# Titan_Teknic_v1p00.net
KiCad netlist of a schematic drawn in EAGLE
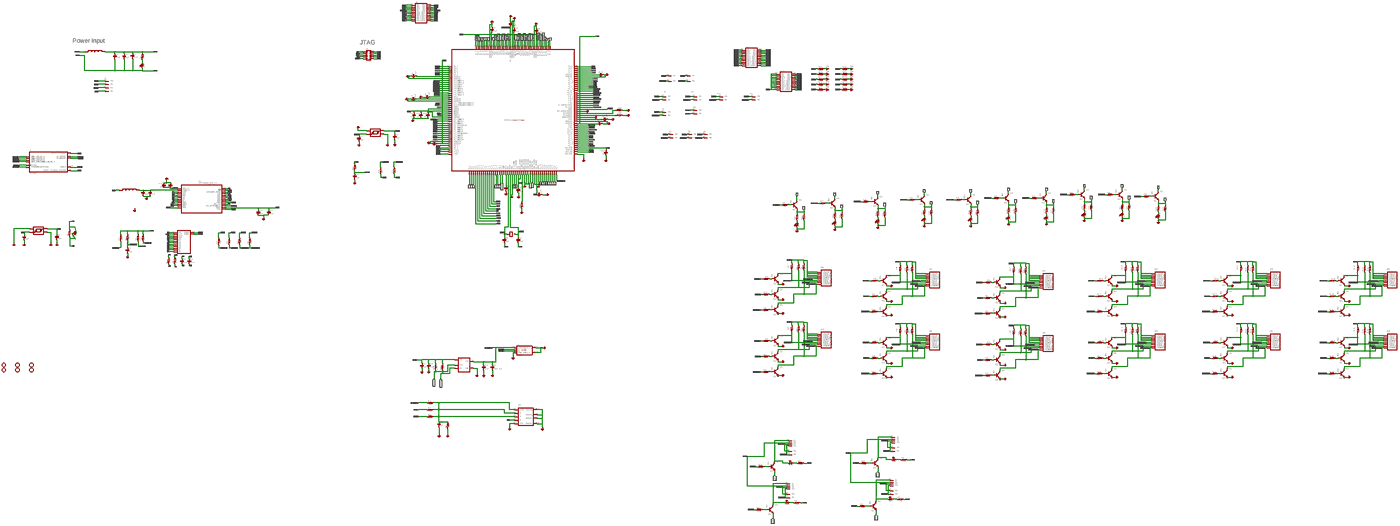
[diagram p0: schematic, sheet 1, overview]
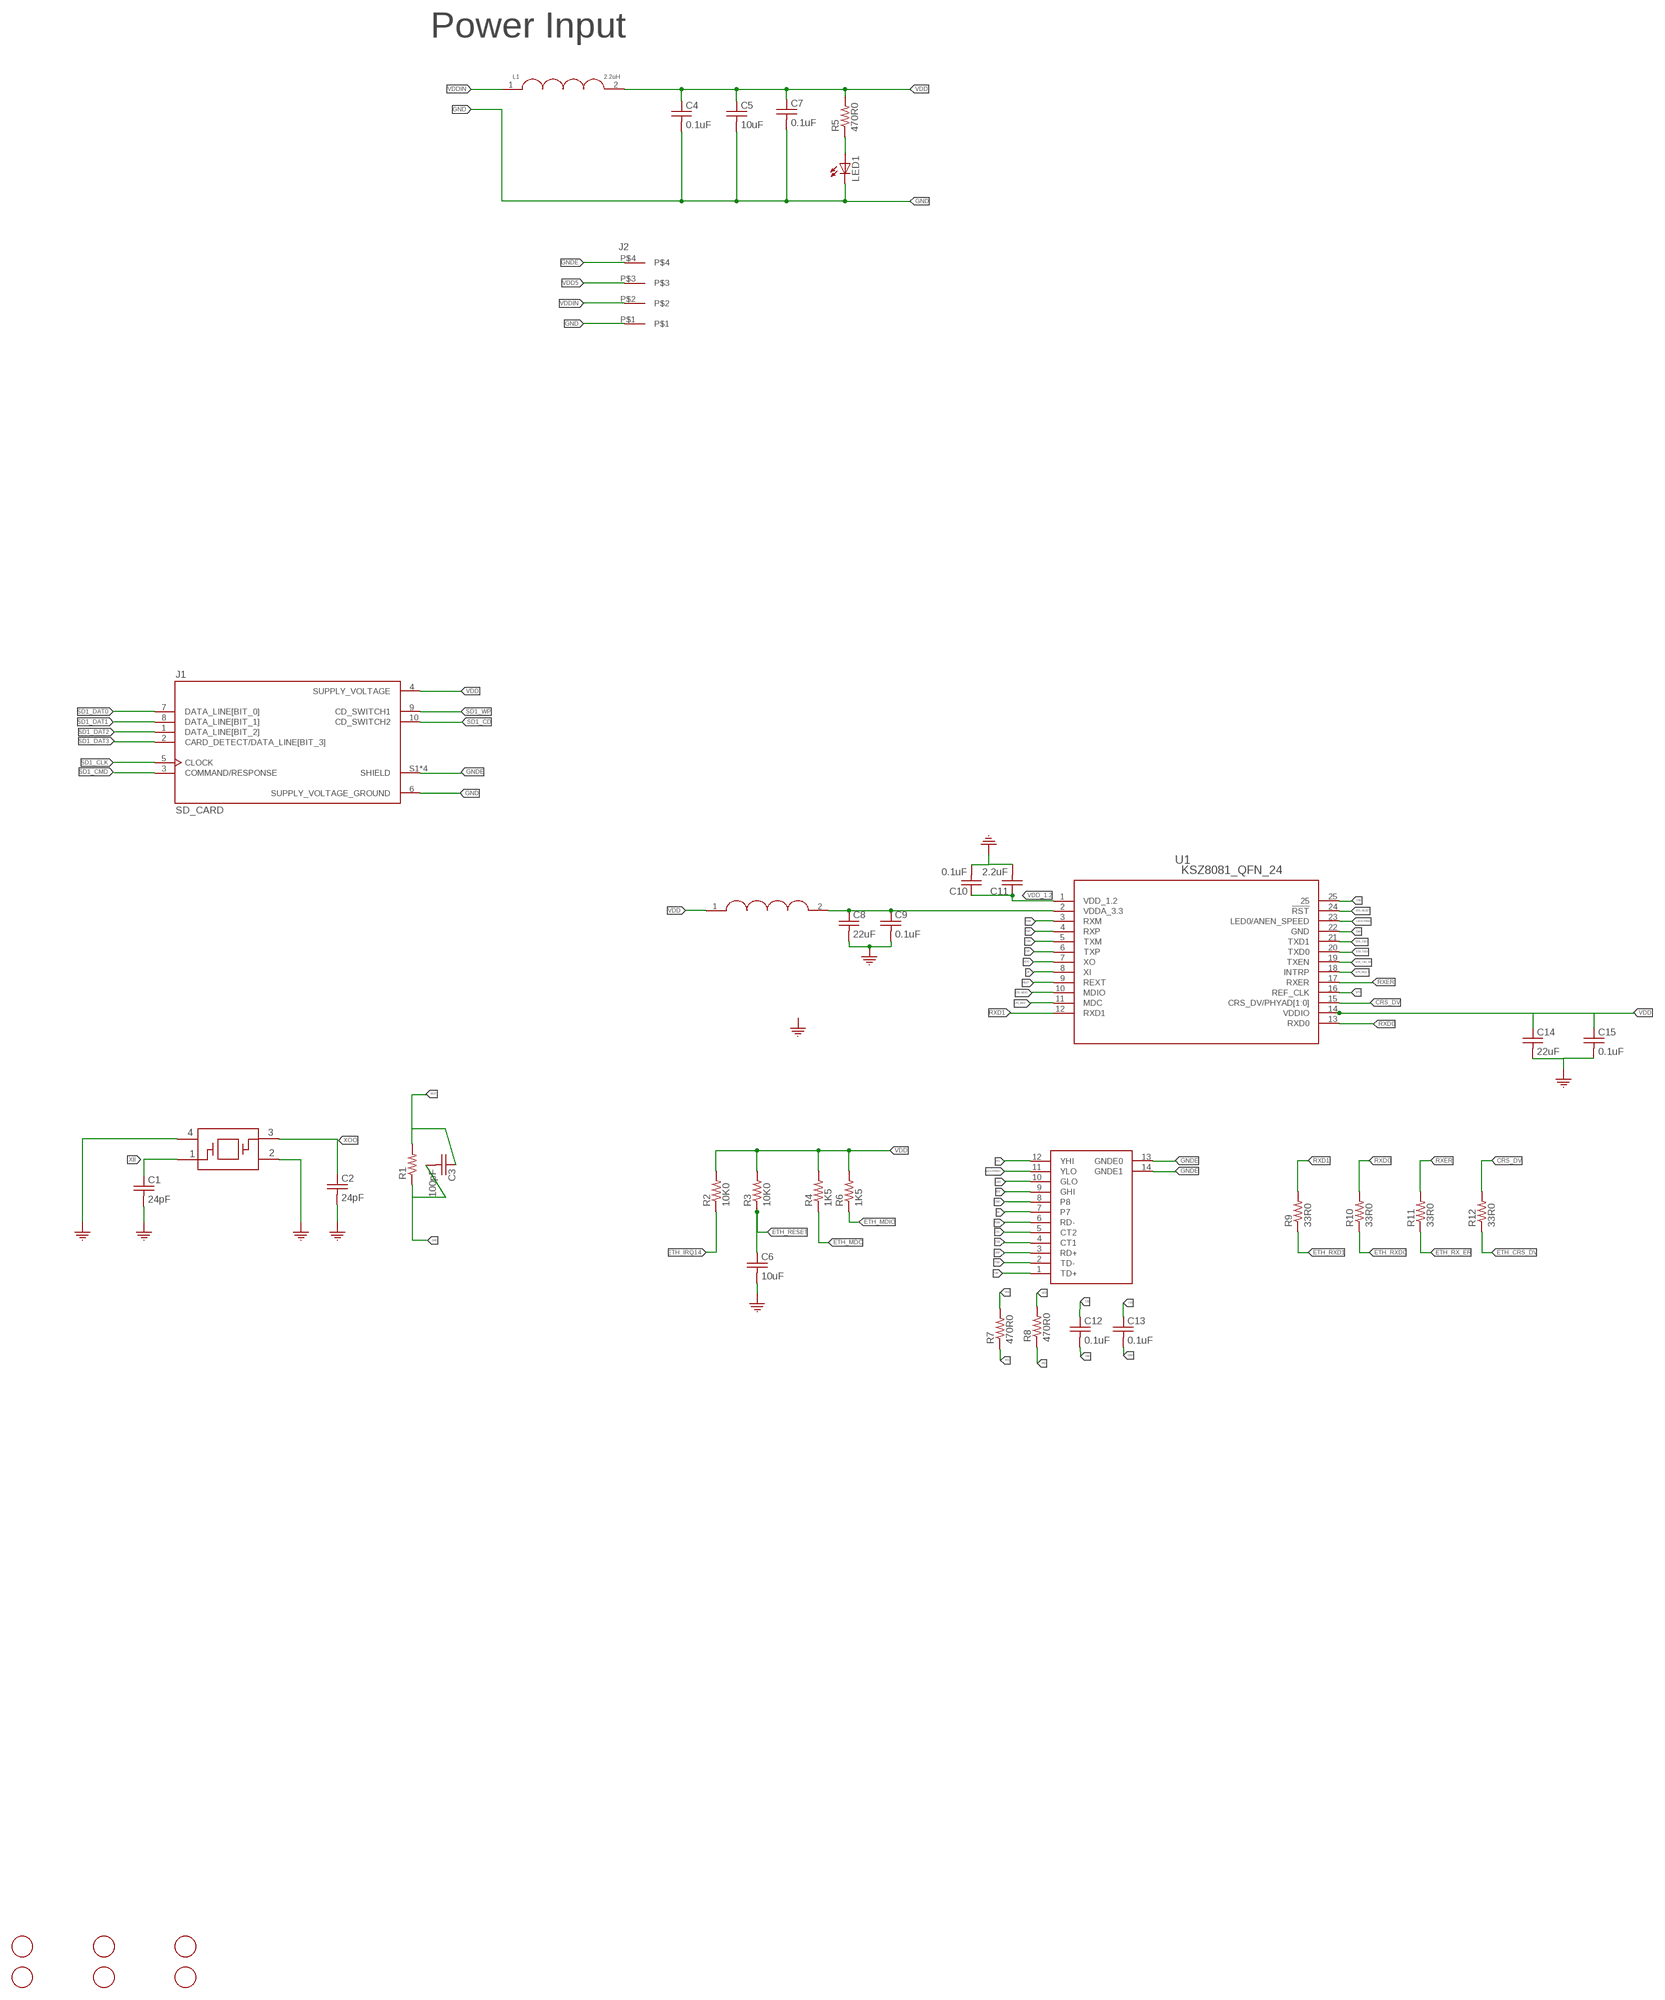
[diagram p1: schematic, sheet 1, part 1 of 6]
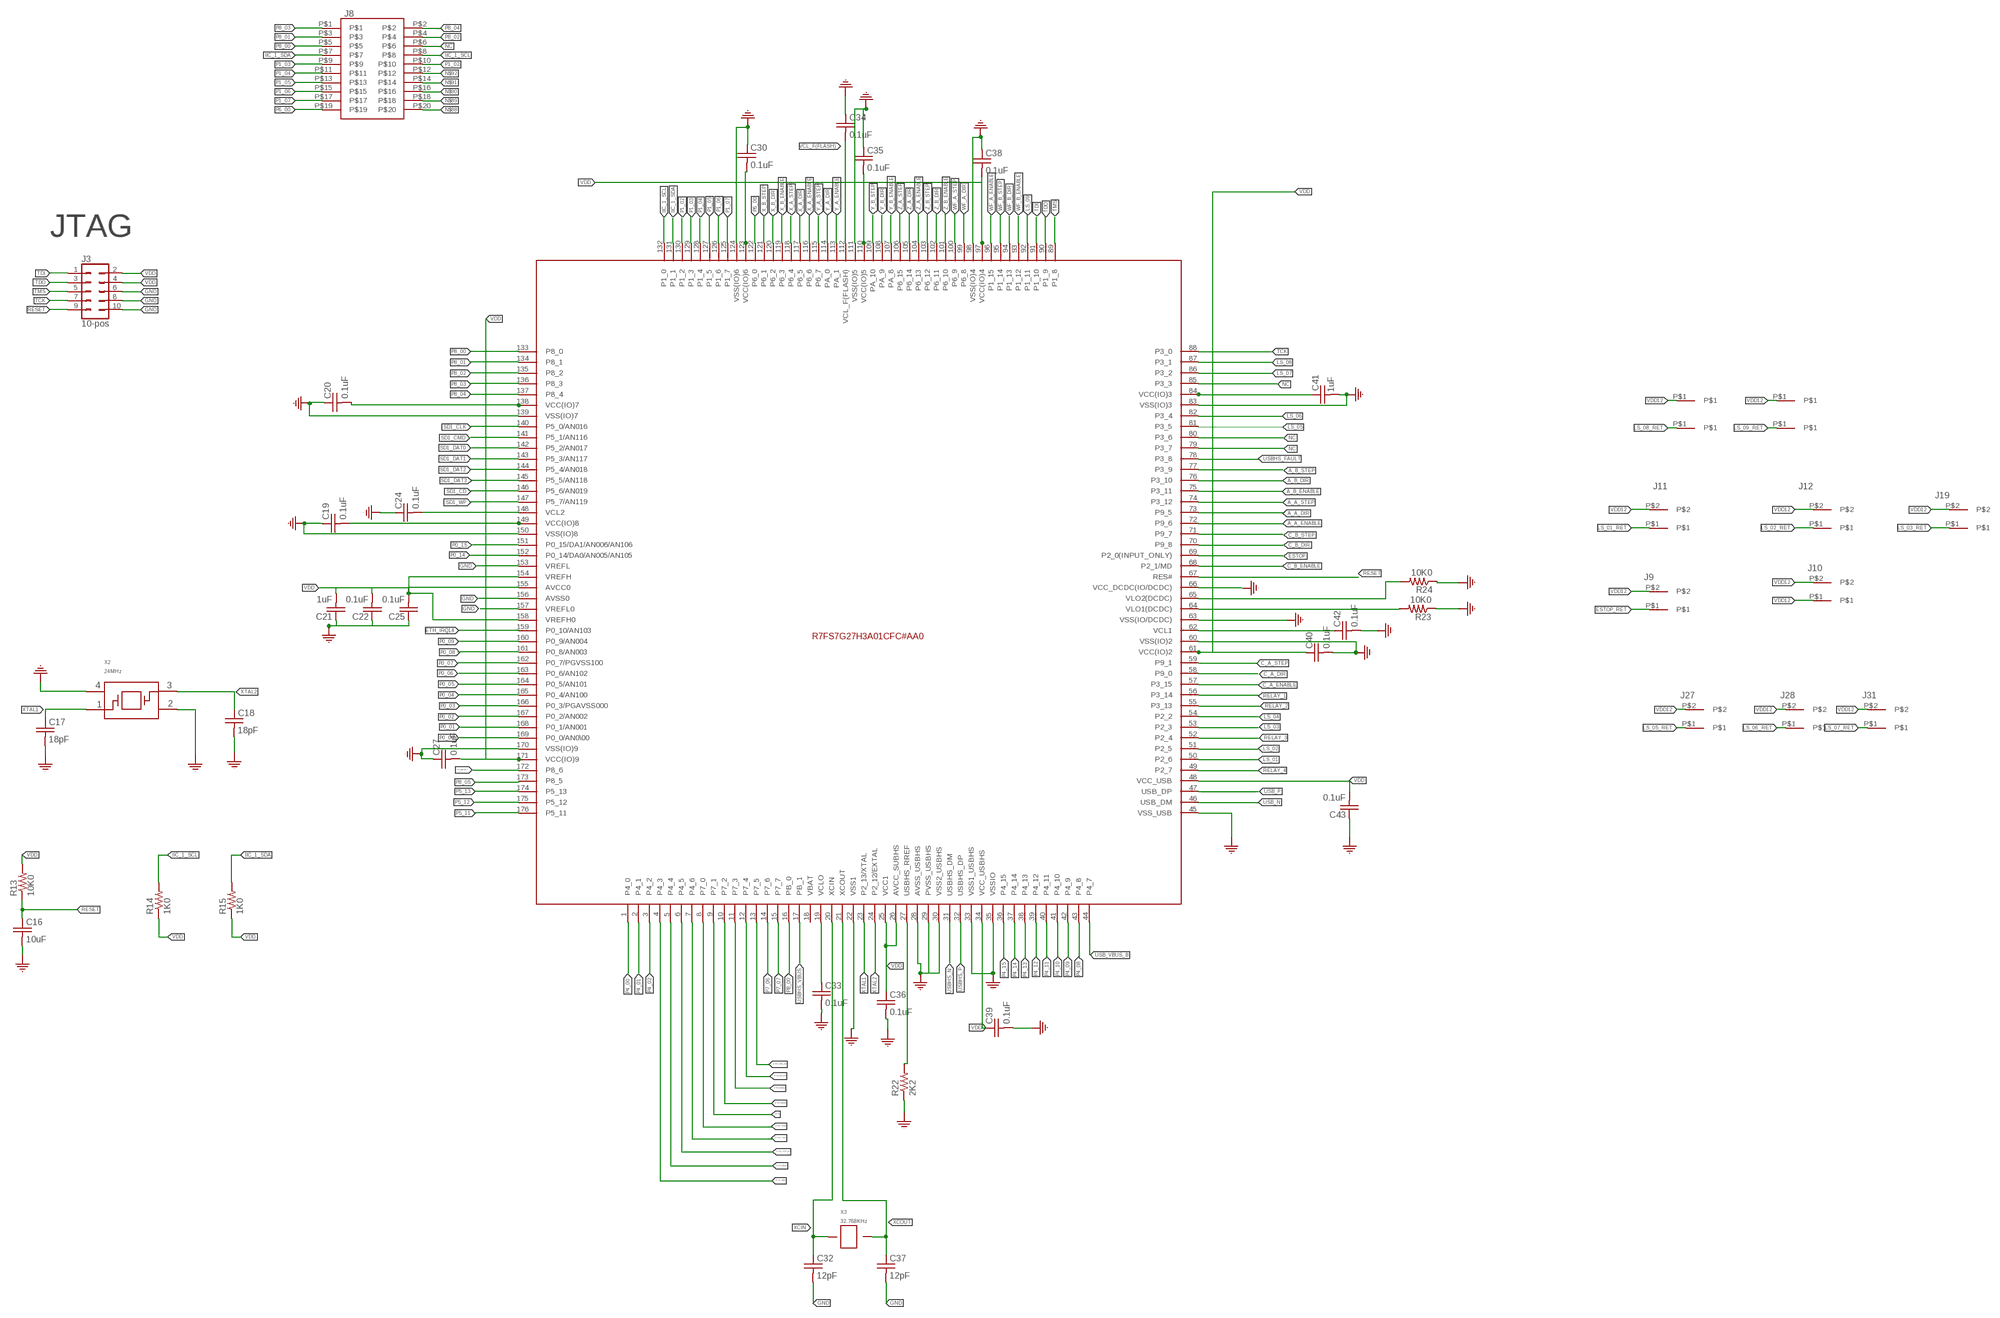
[diagram p2: schematic, sheet 1, part 2 of 6]
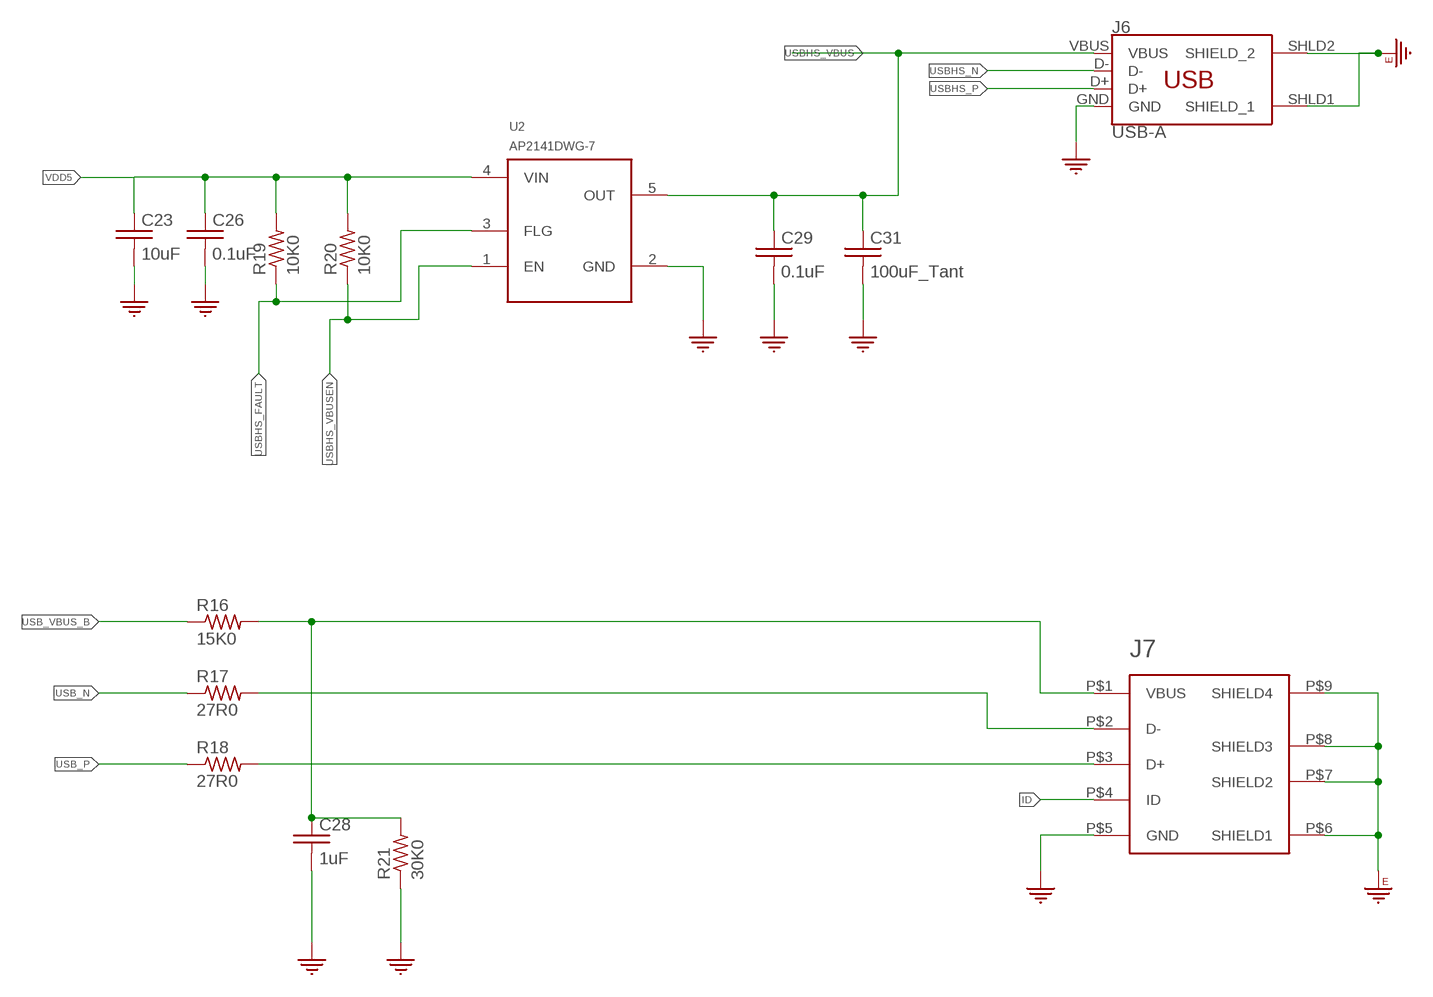
[diagram p3: schematic, sheet 1, part 3 of 6]
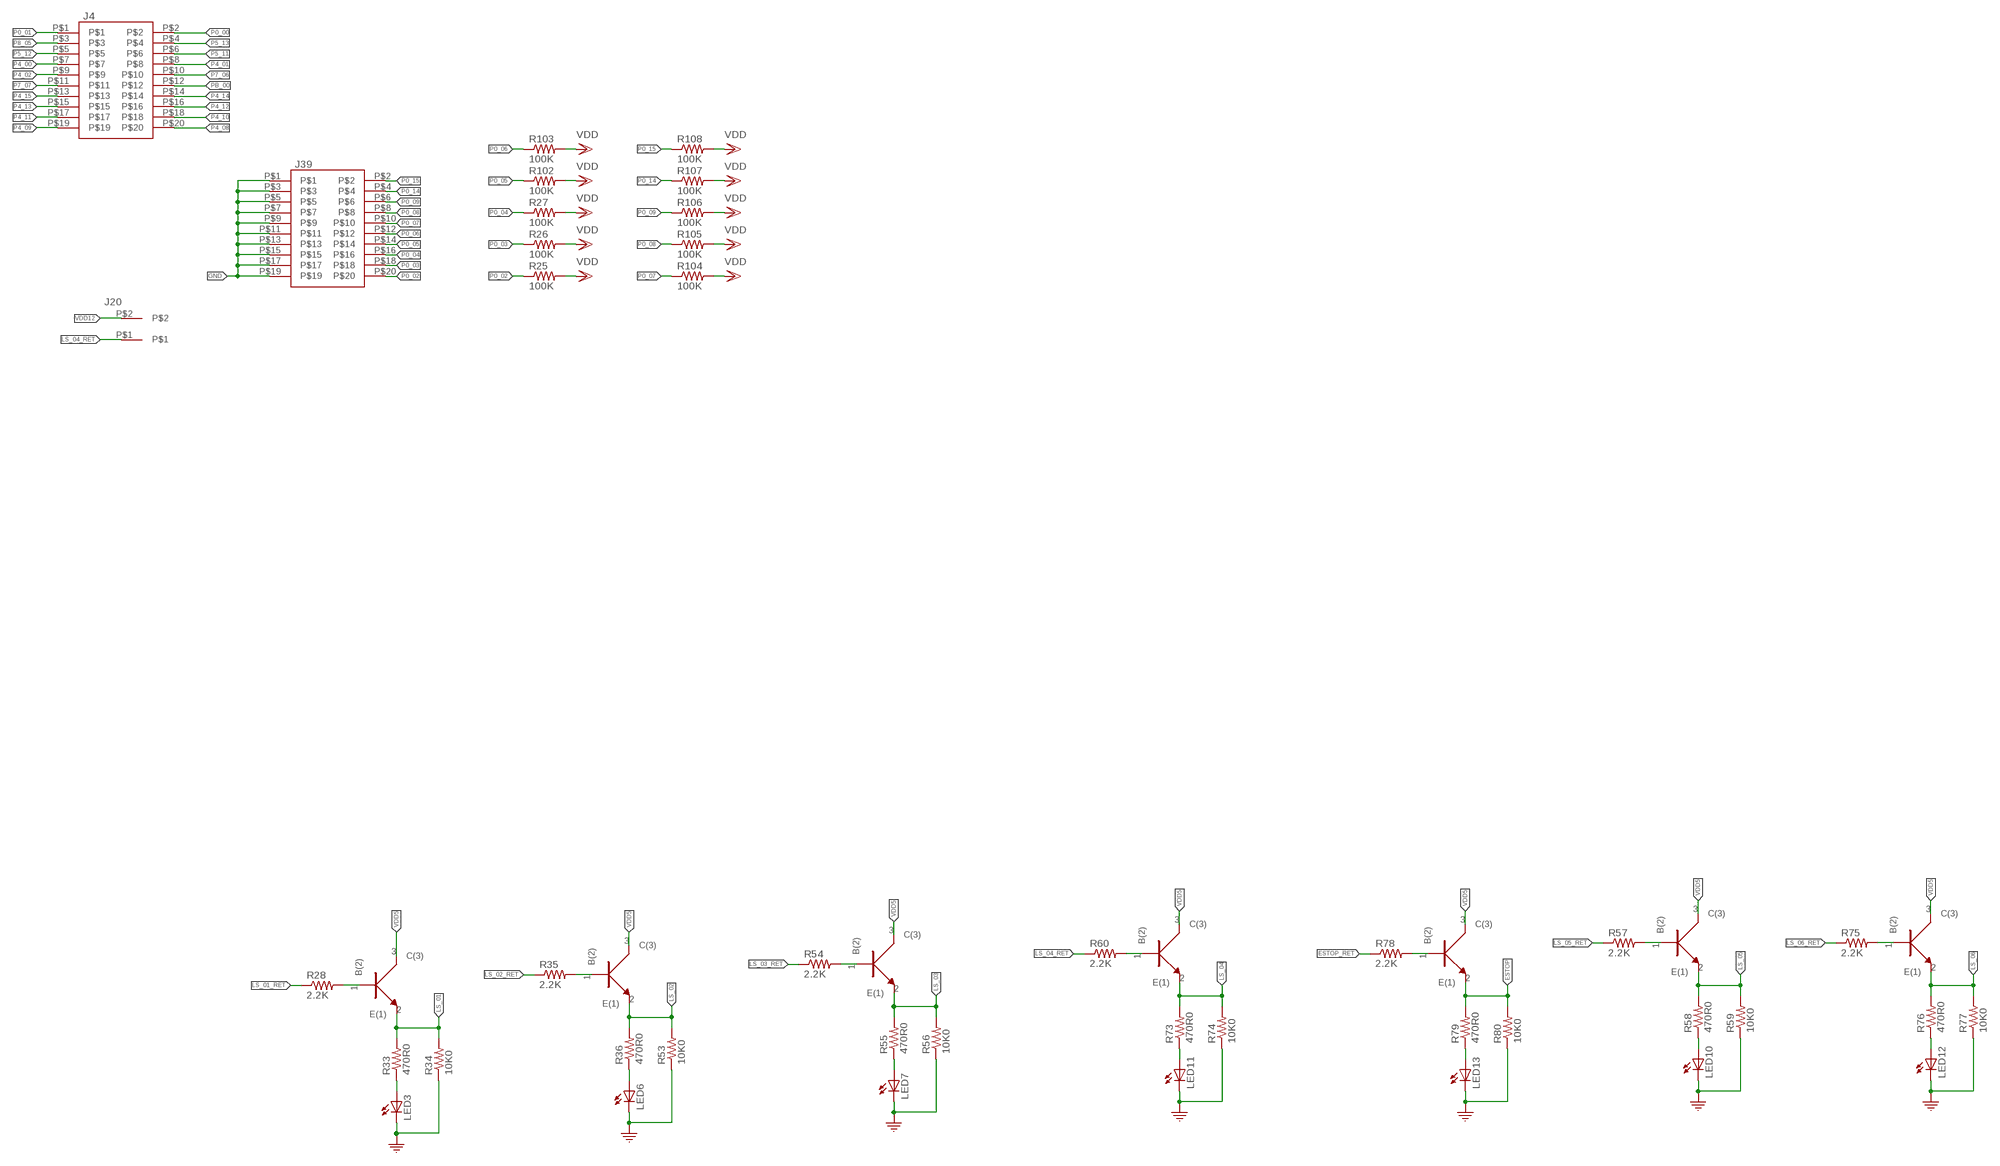
[diagram p4: schematic, sheet 1, part 4 of 6]
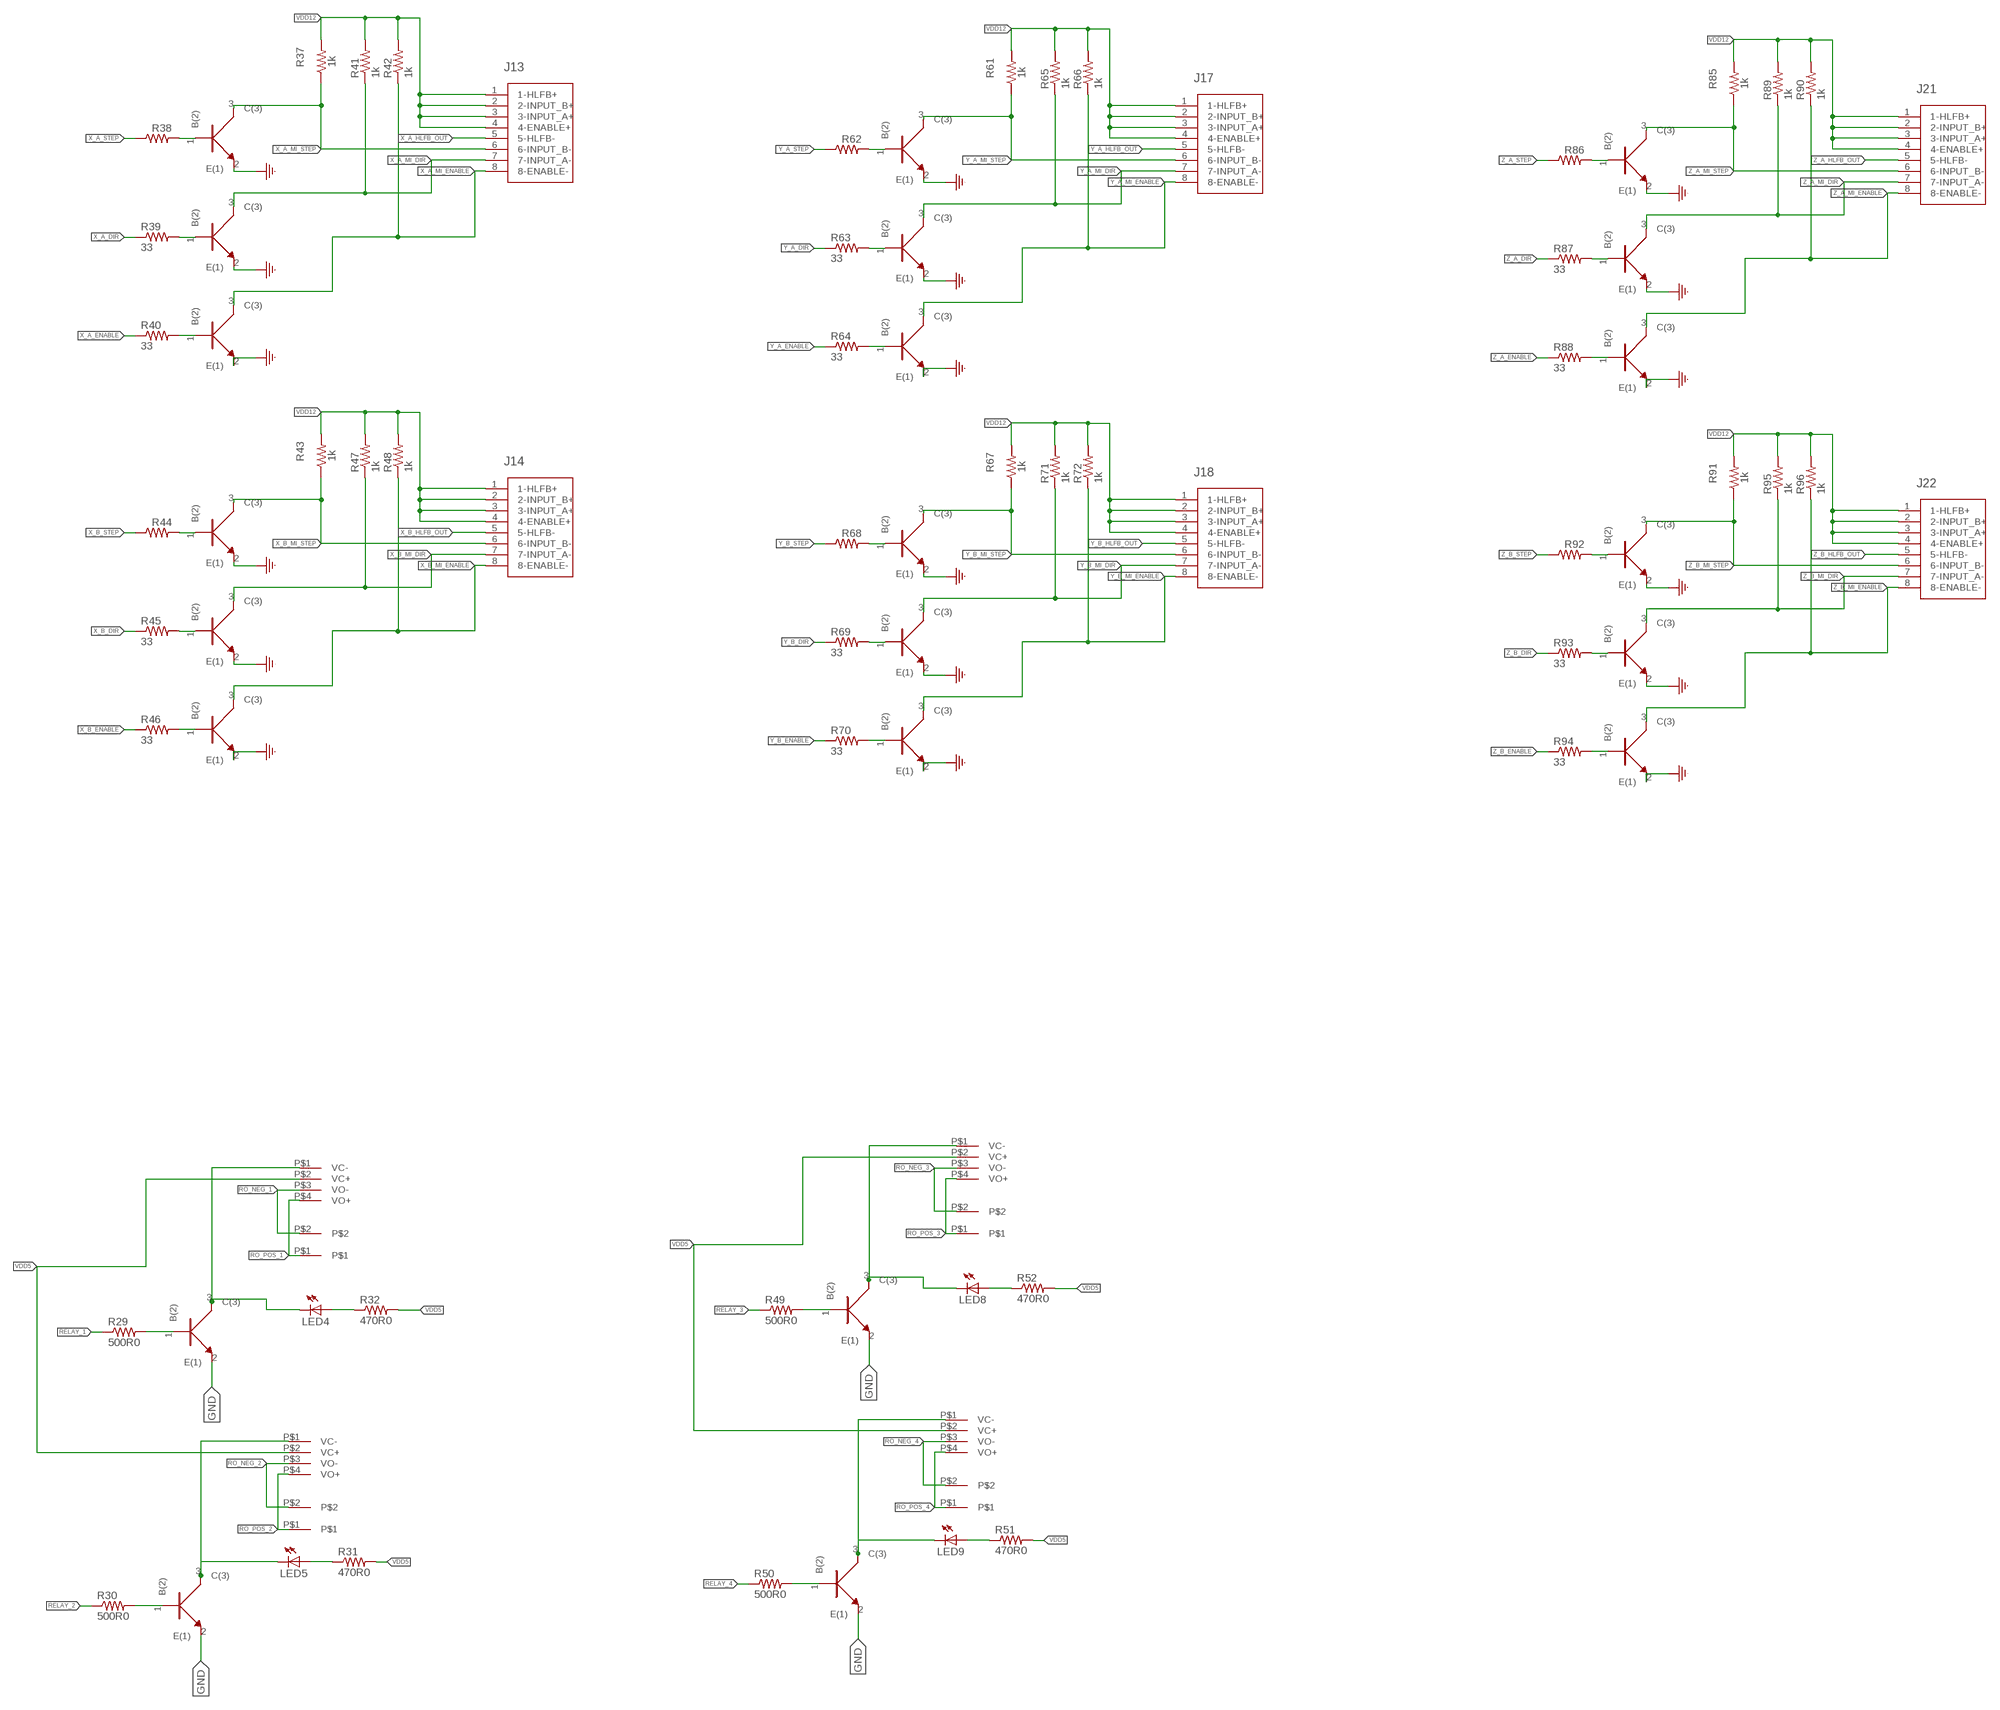
[diagram p5: schematic, sheet 1, part 5 of 6]
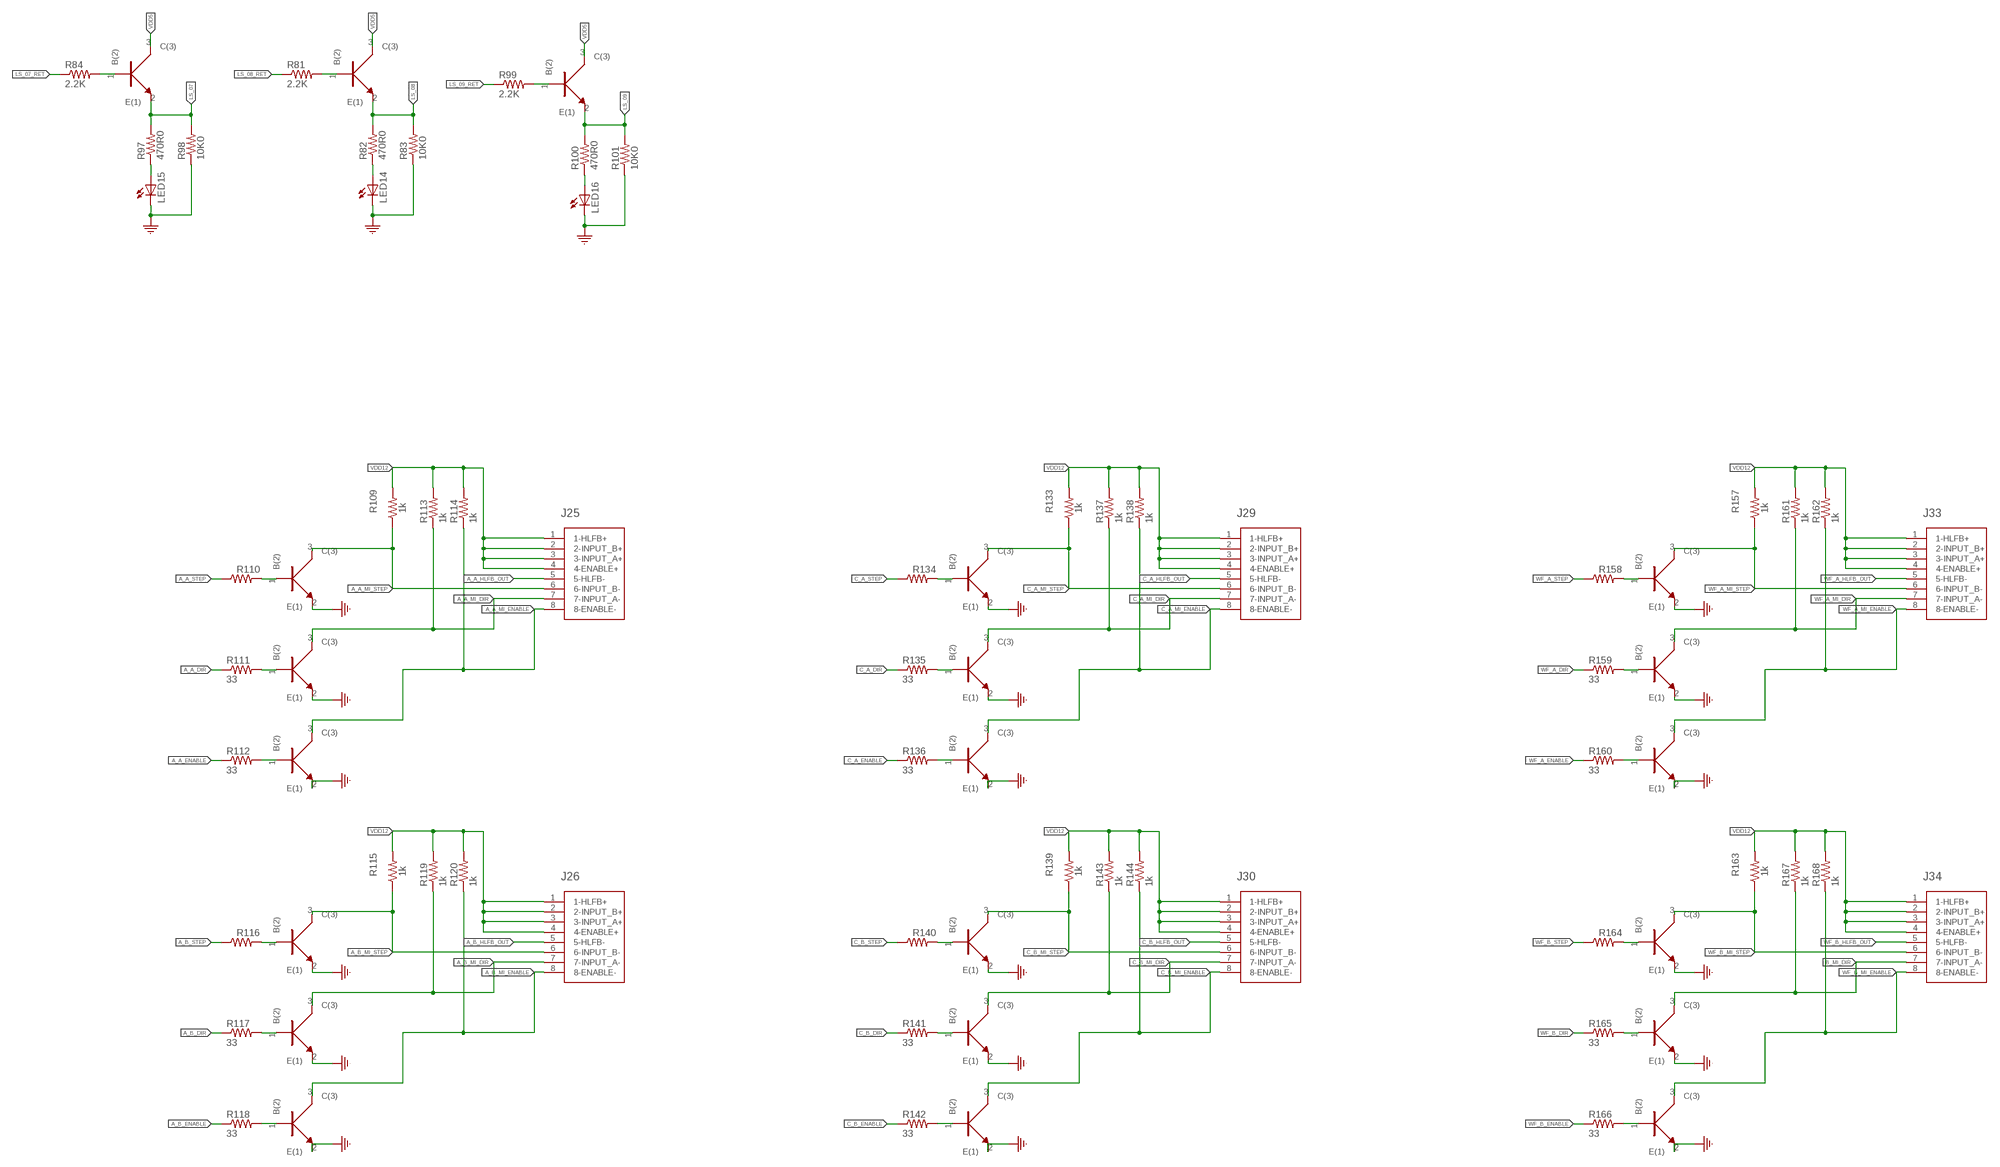
[diagram p6: schematic, sheet 1, part 6 of 6]

(export (version "E")
  (design (tool "Eeschema 10.0.6"))
  (components
    (comp (ref "AFID1")
      (value "FIDUCIAL_1MM")
      (footprint "eagle-import:FIDUCIAL_1MM")
      (libsource (lib "eagle-import") (part "FIDUCIAL_1MM"))
    )
    (comp (ref "AFID2")
      (value "FIDUCIAL_1MM")
      (footprint "eagle-import:FIDUCIAL_1MM")
      (libsource (lib "eagle-import") (part "FIDUCIAL_1MM"))
    )
    (comp (ref "AFID3")
      (value "FIDUCIAL_1MM")
      (footprint "eagle-import:FIDUCIAL_1MM")
      (libsource (lib "eagle-import") (part "FIDUCIAL_1MM"))
    )
    (comp (ref "AFID4")
      (value "FIDUCIAL_1MM")
      (footprint "eagle-import:FIDUCIAL_1MM")
      (libsource (lib "eagle-import") (part "FIDUCIAL_1MM"))
    )
    (comp (ref "AFID5")
      (value "FIDUCIAL_1MM")
      (footprint "eagle-import:FIDUCIAL_1MM")
      (libsource (lib "eagle-import") (part "FIDUCIAL_1MM"))
    )
    (comp (ref "AFID6")
      (value "FIDUCIAL_1MM")
      (footprint "eagle-import:FIDUCIAL_1MM")
      (libsource (lib "eagle-import") (part "FIDUCIAL_1MM"))
    )
    (comp (ref "C1")
      (value "24pF")
      (footprint "eagle-import:0402")
      (fields (field (name "PARTNO") "CC0402GRNPO9BN240"))
      (libsource (lib "eagle-import") (part "C_0402_24PF"))
    )
    (comp (ref "C2")
      (value "24pF")
      (footprint "eagle-import:0402")
      (fields (field (name "PARTNO") "CC0402GRNPO9BN240"))
      (libsource (lib "eagle-import") (part "C_0402_24PF"))
    )
    (comp (ref "C3")
      (value "100pF")
      (footprint "eagle-import:0402")
      (fields (field (name "PARTNO") "CL05C101JB5NNNC"))
      (libsource (lib "eagle-import") (part "C_0402_100PF"))
    )
    (comp (ref "C4")
      (value "0.1uF")
      (footprint "eagle-import:0402")
      (fields (field (name "PARTNO") "CL05F104ZO5NNNC"))
      (libsource (lib "eagle-import") (part "C_0402_0.1UF"))
    )
    (comp (ref "C5")
      (value "10uF")
      (footprint "eagle-import:0402")
      (fields (field (name "PARTNO") "CL05A106MP8NUB8"))
      (libsource (lib "eagle-import") (part "C_0402_10UF"))
    )
    (comp (ref "C6")
      (value "10uF")
      (footprint "eagle-import:0402")
      (fields (field (name "PARTNO") "CL05A106MP8NUB8"))
      (libsource (lib "eagle-import") (part "C_0402_10UF"))
    )
    (comp (ref "C7")
      (value "0.1uF")
      (footprint "eagle-import:0402")
      (fields (field (name "PARTNO") "CL05F104ZO5NNNC"))
      (libsource (lib "eagle-import") (part "C_0402_0.1UF"))
    )
    (comp (ref "C8")
      (value "22uF")
      (footprint "eagle-import:0402")
      (fields (field (name "PARTNO") "CL05A226MQ5N6J8"))
      (libsource (lib "eagle-import") (part "C_0402_22UF"))
    )
    (comp (ref "C9")
      (value "0.1uF")
      (footprint "eagle-import:0402")
      (fields (field (name "PARTNO") "CL05F104ZO5NNNC"))
      (libsource (lib "eagle-import") (part "C_0402_0.1UF"))
    )
    (comp (ref "C10")
      (value "0.1uF")
      (footprint "eagle-import:0402")
      (fields (field (name "PARTNO") "CL05F104ZO5NNNC"))
      (libsource (lib "eagle-import") (part "C_0402_0.1UF"))
    )
    (comp (ref "C11")
      (value "2.2uF")
      (footprint "eagle-import:0402")
      (fields (field (name "PARTNO") "GRM155C81C225ME15D"))
      (libsource (lib "eagle-import") (part "C_0402_2.2UF"))
    )
    (comp (ref "C12")
      (value "0.1uF")
      (footprint "eagle-import:0402")
      (fields (field (name "PARTNO") "CL05F104ZO5NNNC"))
      (libsource (lib "eagle-import") (part "C_0402_0.1UF"))
    )
    (comp (ref "C13")
      (value "0.1uF")
      (footprint "eagle-import:0402")
      (fields (field (name "PARTNO") "CL05F104ZO5NNNC"))
      (libsource (lib "eagle-import") (part "C_0402_0.1UF"))
    )
    (comp (ref "C14")
      (value "22uF")
      (footprint "eagle-import:0402")
      (fields (field (name "PARTNO") "CL05A226MQ5N6J8"))
      (libsource (lib "eagle-import") (part "C_0402_22UF"))
    )
    (comp (ref "C15")
      (value "0.1uF")
      (footprint "eagle-import:0402")
      (fields (field (name "PARTNO") "CL05F104ZO5NNNC"))
      (libsource (lib "eagle-import") (part "C_0402_0.1UF"))
    )
    (comp (ref "C16")
      (value "10uF")
      (footprint "eagle-import:0402")
      (fields (field (name "PARTNO") "CL05A106MP8NUB8"))
      (libsource (lib "eagle-import") (part "C_0402_10UF"))
    )
    (comp (ref "C17")
      (value "18pF")
      (footprint "eagle-import:0402")
      (fields (field (name "PARTNO") "UMK105CG180JV-F"))
      (libsource (lib "eagle-import") (part "C_0402_18PF"))
    )
    (comp (ref "C18")
      (value "18pF")
      (footprint "eagle-import:0402")
      (fields (field (name "PARTNO") "UMK105CG180JV-F"))
      (libsource (lib "eagle-import") (part "C_0402_18PF"))
    )
    (comp (ref "C19")
      (value "0.1uF")
      (footprint "eagle-import:0402")
      (fields (field (name "PARTNO") "CL05F104ZO5NNNC"))
      (libsource (lib "eagle-import") (part "C_0402_0.1UF"))
    )
    (comp (ref "C20")
      (value "0.1uF")
      (footprint "eagle-import:0402")
      (fields (field (name "PARTNO") "CL05F104ZO5NNNC"))
      (libsource (lib "eagle-import") (part "C_0402_0.1UF"))
    )
    (comp (ref "C21")
      (value "1uF")
      (footprint "eagle-import:0402")
      (fields (field (name "PARTNO") "CL05A105KO5NNNC"))
      (libsource (lib "eagle-import") (part "C_0402_1UF"))
    )
    (comp (ref "C22")
      (value "0.1uF")
      (footprint "eagle-import:0402")
      (fields (field (name "PARTNO") "CL05F104ZO5NNNC"))
      (libsource (lib "eagle-import") (part "C_0402_0.1UF"))
    )
    (comp (ref "C23")
      (value "10uF")
      (footprint "eagle-import:0402")
      (fields (field (name "PARTNO") "CL05A106MP8NUB8"))
      (libsource (lib "eagle-import") (part "C_0402_10UF"))
    )
    (comp (ref "C24")
      (value "0.1uF")
      (footprint "eagle-import:0402")
      (fields (field (name "PARTNO") "CL05F104ZO5NNNC"))
      (libsource (lib "eagle-import") (part "C_0402_0.1UF"))
    )
    (comp (ref "C25")
      (value "0.1uF")
      (footprint "eagle-import:0402")
      (fields (field (name "PARTNO") "CL05F104ZO5NNNC"))
      (libsource (lib "eagle-import") (part "C_0402_0.1UF"))
    )
    (comp (ref "C26")
      (value "0.1uF")
      (footprint "eagle-import:0402")
      (fields (field (name "PARTNO") "CL05F104ZO5NNNC"))
      (libsource (lib "eagle-import") (part "C_0402_0.1UF"))
    )
    (comp (ref "C27")
      (value "0.1uF")
      (footprint "eagle-import:0402")
      (fields (field (name "PARTNO") "CL05F104ZO5NNNC"))
      (libsource (lib "eagle-import") (part "C_0402_0.1UF"))
    )
    (comp (ref "C28")
      (value "1uF")
      (footprint "eagle-import:0402")
      (fields (field (name "PARTNO") "CL05A105KO5NNNC"))
      (libsource (lib "eagle-import") (part "C_0402_1UF"))
    )
    (comp (ref "C29")
      (value "0.1uF")
      (footprint "eagle-import:0402")
      (fields (field (name "PARTNO") "CL05F104ZO5NNNC"))
      (libsource (lib "eagle-import") (part "C_0402_0.1UF"))
    )
    (comp (ref "C30")
      (value "0.1uF")
      (footprint "eagle-import:0402")
      (fields (field (name "PARTNO") "CL05F104ZO5NNNC"))
      (libsource (lib "eagle-import") (part "C_0402_0.1UF"))
    )
    (comp (ref "C31")
      (value "100uF_Tant")
      (footprint "eagle-import:C1210")
      (fields (field (name "PARTNO") "TLJT107M010R0900"))
      (libsource (lib "eagle-import") (part "C_1210_100UF_TANT"))
    )
    (comp (ref "C32")
      (value "12pF")
      (footprint "eagle-import:0402")
      (fields (field (name "PARTNO") "CL05C120JB5NNNC"))
      (libsource (lib "eagle-import") (part "C_0402_12PF"))
    )
    (comp (ref "C33")
      (value "0.1uF")
      (footprint "eagle-import:0402")
      (fields (field (name "PARTNO") "CL05F104ZO5NNNC"))
      (libsource (lib "eagle-import") (part "C_0402_0.1UF"))
    )
    (comp (ref "C34")
      (value "0.1uF")
      (footprint "eagle-import:0402")
      (fields (field (name "PARTNO") "CL05F104ZO5NNNC"))
      (libsource (lib "eagle-import") (part "C_0402_0.1UF"))
    )
    (comp (ref "C35")
      (value "0.1uF")
      (footprint "eagle-import:0402")
      (fields (field (name "PARTNO") "CL05F104ZO5NNNC"))
      (libsource (lib "eagle-import") (part "C_0402_0.1UF"))
    )
    (comp (ref "C36")
      (value "0.1uF")
      (footprint "eagle-import:0402")
      (fields (field (name "PARTNO") "CL05F104ZO5NNNC"))
      (libsource (lib "eagle-import") (part "C_0402_0.1UF"))
    )
    (comp (ref "C37")
      (value "12pF")
      (footprint "eagle-import:0402")
      (fields (field (name "PARTNO") "CL05C120JB5NNNC"))
      (libsource (lib "eagle-import") (part "C_0402_12PF"))
    )
    (comp (ref "C38")
      (value "0.1uF")
      (footprint "eagle-import:0402")
      (fields (field (name "PARTNO") "CL05F104ZO5NNNC"))
      (libsource (lib "eagle-import") (part "C_0402_0.1UF"))
    )
    (comp (ref "C39")
      (value "0.1uF")
      (footprint "eagle-import:0402")
      (fields (field (name "PARTNO") "CL05F104ZO5NNNC"))
      (libsource (lib "eagle-import") (part "C_0402_0.1UF"))
    )
    (comp (ref "C40")
      (value "0.1uF")
      (footprint "eagle-import:0402")
      (fields (field (name "PARTNO") "CL05F104ZO5NNNC"))
      (libsource (lib "eagle-import") (part "C_0402_0.1UF"))
    )
    (comp (ref "C41")
      (value "1uF")
      (footprint "eagle-import:0402")
      (fields (field (name "PARTNO") "CL05A105KO5NNNC"))
      (libsource (lib "eagle-import") (part "C_0402_1UF"))
    )
    (comp (ref "C42")
      (value "0.1uF")
      (footprint "eagle-import:0402")
      (fields (field (name "PARTNO") "CL05F104ZO5NNNC"))
      (libsource (lib "eagle-import") (part "C_0402_0.1UF"))
    )
    (comp (ref "C43")
      (value "0.1uF")
      (footprint "eagle-import:0402")
      (fields (field (name "PARTNO") "CL05F104ZO5NNNC"))
      (libsource (lib "eagle-import") (part "C_0402_0.1UF"))
    )
    (comp (ref "FB1")
      (value "FB2_603")
      (footprint "eagle-import:0603")
      (fields (field (name "PARTNO") "BLM18PG121SN1D"))
      (libsource (lib "eagle-import") (part "FB_0603_120_OHM0603"))
    )
    (comp (ref "J1")
      (value "SD_CARD")
      (footprint "eagle-import:SD_CARD")
      (fields (field (name "MF") "Amphenol ICC") (field (name "PARTNO") "114-00841-68"))
      (libsource (lib "eagle-import") (part "SD_CARD_1140084168"))
    )
    (comp (ref "J2")
      (value "4-pos")
      (footprint "eagle-import:1X4_3.81MM_PITCH")
      (fields (field (name "PARTNO") "691322310004"))
      (libsource (lib "eagle-import") (part "3.81MM_1_X_4_RT_ANGLE_PLUG_HEADER"))
    )
    (comp (ref "J3")
      (value "10-pos")
      (footprint "eagle-import:2X5")
      (fields (field (name "PARTNO") "PH2RA-10-UA"))
      (libsource (lib "eagle-import") (part "CONN_05X2_RAPTH"))
    )
    (comp (ref "J4")
      (value "20-pos")
      (footprint "eagle-import:2_X_10_.1_INCH")
      (fields (field (name "PARTNO") "67996-420HLF"))
      (libsource (lib "eagle-import") (part "2_X_10_HEADER_GENERIC"))
    )
    (comp (ref "J6")
      (value "USB-A")
      (footprint "eagle-import:USB_A_SMT")
      (fields (field (name "PARTNO") "87583-3010RPALF"))
      (libsource (lib "eagle-import") (part "USB_A"))
    )
    (comp (ref "J7")
      (value "USB-B-Micro")
      (footprint "eagle-import:USB_MICRO-B")
      (fields (field (name "PARTNO") "10118192-0002LF"))
      (libsource (lib "eagle-import") (part "USB_MICRO-B"))
    )
    (comp (ref "J8")
      (value "2_X_10_HEADER_GENERIC")
      (footprint "eagle-import:2_X_10_.1_INCH")
      (fields (field (name "PARTNO") "67996-420HLF"))
      (libsource (lib "eagle-import") (part "2_X_10_HEADER_GENERIC"))
    )
    (comp (ref "J9")
      (value "2-pos")
      (footprint "eagle-import:2_3.81MM_PITCH")
      (fields (field (name "PARTNO") "691322310002"))
      (libsource (lib "eagle-import") (part "3.81MM_1_X_2_RT_ANGLE_PLUG_HEADER"))
    )
    (comp (ref "J10")
      (value "2-pos")
      (footprint "eagle-import:2_3.81MM_PITCH")
      (fields (field (name "PARTNO") "691322310002"))
      (libsource (lib "eagle-import") (part "3.81MM_1_X_2_RT_ANGLE_PLUG_HEADER"))
    )
    (comp (ref "J11")
      (value "2-pos")
      (footprint "eagle-import:2_3.81MM_PITCH")
      (fields (field (name "PARTNO") "691322310002"))
      (libsource (lib "eagle-import") (part "3.81MM_1_X_2_RT_ANGLE_PLUG_HEADER"))
    )
    (comp (ref "J12")
      (value "2-pos")
      (footprint "eagle-import:2_3.81MM_PITCH")
      (fields (field (name "PARTNO") "691322310002"))
      (libsource (lib "eagle-import") (part "3.81MM_1_X_2_RT_ANGLE_PLUG_HEADER"))
    )
    (comp (ref "J13")
      (value "TEKNIC_8PIN_MOTOR")
      (footprint "eagle-import:CON_39281083")
      (fields
        (field (name "MANUFACTURER_PART_NUMBER") "39281083")
        (field (name "COPYRIGHT") "Copyright (C) 2022 Ultra Librarian. All rights reserved.")
      )
      (libsource (lib "eagle-import") (part "TEKNIC_8PIN_MOTOR"))
    )
    (comp (ref "J14")
      (value "TEKNIC_8PIN_MOTOR")
      (footprint "eagle-import:CON_39281083")
      (fields
        (field (name "MANUFACTURER_PART_NUMBER") "39281083")
        (field (name "COPYRIGHT") "Copyright (C) 2022 Ultra Librarian. All rights reserved.")
      )
      (libsource (lib "eagle-import") (part "TEKNIC_8PIN_MOTOR"))
    )
    (comp (ref "J15")
      (value "2-pos")
      (footprint "eagle-import:2_3.81MM_PITCH")
      (fields (field (name "PARTNO") "691322310002"))
      (libsource (lib "eagle-import") (part "3.81MM_1_X_2_RT_ANGLE_PLUG_HEADER"))
    )
    (comp (ref "J16")
      (value "2-pos")
      (footprint "eagle-import:2_3.81MM_PITCH")
      (fields (field (name "PARTNO") "691322310002"))
      (libsource (lib "eagle-import") (part "3.81MM_1_X_2_RT_ANGLE_PLUG_HEADER"))
    )
    (comp (ref "J17")
      (value "TEKNIC_8PIN_MOTOR")
      (footprint "eagle-import:CON_39281083")
      (fields
        (field (name "MANUFACTURER_PART_NUMBER") "39281083")
        (field (name "COPYRIGHT") "Copyright (C) 2022 Ultra Librarian. All rights reserved.")
      )
      (libsource (lib "eagle-import") (part "TEKNIC_8PIN_MOTOR"))
    )
    (comp (ref "J18")
      (value "TEKNIC_8PIN_MOTOR")
      (footprint "eagle-import:CON_39281083")
      (fields
        (field (name "MANUFACTURER_PART_NUMBER") "39281083")
        (field (name "COPYRIGHT") "Copyright (C) 2022 Ultra Librarian. All rights reserved.")
      )
      (libsource (lib "eagle-import") (part "TEKNIC_8PIN_MOTOR"))
    )
    (comp (ref "J19")
      (value "2-pos")
      (footprint "eagle-import:2_3.81MM_PITCH")
      (fields (field (name "PARTNO") "691322310002"))
      (libsource (lib "eagle-import") (part "3.81MM_1_X_2_RT_ANGLE_PLUG_HEADER"))
    )
    (comp (ref "J20")
      (value "2-pos")
      (footprint "eagle-import:2_3.81MM_PITCH")
      (fields (field (name "PARTNO") "691322310002"))
      (libsource (lib "eagle-import") (part "3.81MM_1_X_2_RT_ANGLE_PLUG_HEADER"))
    )
    (comp (ref "J21")
      (value "TEKNIC_8PIN_MOTOR")
      (footprint "eagle-import:CON_39281083")
      (fields
        (field (name "MANUFACTURER_PART_NUMBER") "39281083")
        (field (name "COPYRIGHT") "Copyright (C) 2022 Ultra Librarian. All rights reserved.")
      )
      (libsource (lib "eagle-import") (part "TEKNIC_8PIN_MOTOR"))
    )
    (comp (ref "J22")
      (value "TEKNIC_8PIN_MOTOR")
      (footprint "eagle-import:CON_39281083")
      (fields
        (field (name "MANUFACTURER_PART_NUMBER") "39281083")
        (field (name "COPYRIGHT") "Copyright (C) 2022 Ultra Librarian. All rights reserved.")
      )
      (libsource (lib "eagle-import") (part "TEKNIC_8PIN_MOTOR"))
    )
    (comp (ref "J23")
      (value "2-pos")
      (footprint "eagle-import:2_3.81MM_PITCH")
      (fields (field (name "PARTNO") "691322310002"))
      (libsource (lib "eagle-import") (part "3.81MM_1_X_2_RT_ANGLE_PLUG_HEADER"))
    )
    (comp (ref "J24")
      (value "2-pos")
      (footprint "eagle-import:2_3.81MM_PITCH")
      (fields (field (name "PARTNO") "691322310002"))
      (libsource (lib "eagle-import") (part "3.81MM_1_X_2_RT_ANGLE_PLUG_HEADER"))
    )
    (comp (ref "J25")
      (value "TEKNIC_8PIN_MOTOR")
      (footprint "eagle-import:CON_39281083")
      (fields
        (field (name "MANUFACTURER_PART_NUMBER") "39281083")
        (field (name "COPYRIGHT") "Copyright (C) 2022 Ultra Librarian. All rights reserved.")
      )
      (libsource (lib "eagle-import") (part "TEKNIC_8PIN_MOTOR"))
    )
    (comp (ref "J26")
      (value "TEKNIC_8PIN_MOTOR")
      (footprint "eagle-import:CON_39281083")
      (fields
        (field (name "MANUFACTURER_PART_NUMBER") "39281083")
        (field (name "COPYRIGHT") "Copyright (C) 2022 Ultra Librarian. All rights reserved.")
      )
      (libsource (lib "eagle-import") (part "TEKNIC_8PIN_MOTOR"))
    )
    (comp (ref "J27")
      (value "2-pos")
      (footprint "eagle-import:2_3.81MM_PITCH")
      (fields (field (name "PARTNO") "691322310002"))
      (libsource (lib "eagle-import") (part "3.81MM_1_X_2_RT_ANGLE_PLUG_HEADER"))
    )
    (comp (ref "J28")
      (value "2-pos")
      (footprint "eagle-import:2_3.81MM_PITCH")
      (fields (field (name "PARTNO") "691322310002"))
      (libsource (lib "eagle-import") (part "3.81MM_1_X_2_RT_ANGLE_PLUG_HEADER"))
    )
    (comp (ref "J29")
      (value "TEKNIC_8PIN_MOTOR")
      (footprint "eagle-import:CON_39281083")
      (fields
        (field (name "MANUFACTURER_PART_NUMBER") "39281083")
        (field (name "COPYRIGHT") "Copyright (C) 2022 Ultra Librarian. All rights reserved.")
      )
      (libsource (lib "eagle-import") (part "TEKNIC_8PIN_MOTOR"))
    )
    (comp (ref "J30")
      (value "TEKNIC_8PIN_MOTOR")
      (footprint "eagle-import:CON_39281083")
      (fields
        (field (name "MANUFACTURER_PART_NUMBER") "39281083")
        (field (name "COPYRIGHT") "Copyright (C) 2022 Ultra Librarian. All rights reserved.")
      )
      (libsource (lib "eagle-import") (part "TEKNIC_8PIN_MOTOR"))
    )
    (comp (ref "J31")
      (value "2-pos")
      (footprint "eagle-import:2_3.81MM_PITCH")
      (fields (field (name "PARTNO") "691322310002"))
      (libsource (lib "eagle-import") (part "3.81MM_1_X_2_RT_ANGLE_PLUG_HEADER"))
    )
    (comp (ref "J33")
      (value "TEKNIC_8PIN_MOTOR")
      (footprint "eagle-import:CON_39281083")
      (fields
        (field (name "MANUFACTURER_PART_NUMBER") "39281083")
        (field (name "COPYRIGHT") "Copyright (C) 2022 Ultra Librarian. All rights reserved.")
      )
      (libsource (lib "eagle-import") (part "TEKNIC_8PIN_MOTOR"))
    )
    (comp (ref "J34")
      (value "TEKNIC_8PIN_MOTOR")
      (footprint "eagle-import:CON_39281083")
      (fields
        (field (name "MANUFACTURER_PART_NUMBER") "39281083")
        (field (name "COPYRIGHT") "Copyright (C) 2022 Ultra Librarian. All rights reserved.")
      )
      (libsource (lib "eagle-import") (part "TEKNIC_8PIN_MOTOR"))
    )
    (comp (ref "J39")
      (value "2_X_10_HEADER_GENERIC")
      (footprint "eagle-import:2_X_10_.1_INCH")
      (fields (field (name "PARTNO") "67996-420HLF"))
      (libsource (lib "eagle-import") (part "2_X_10_HEADER_GENERIC"))
    )
    (comp (ref "L1")
      (value "2.2uH")
      (footprint "eagle-import:1008")
      (fields (field (name "PARTNO") "LQM2HPN2R2MG0L"))
      (libsource (lib "eagle-import") (part "INDUCTOR_1008_2.2_MH_1.3A"))
    )
    (comp (ref "LED1")
      (value "Green")
      (footprint "eagle-import:0805")
      (fields (field (name "PARTNO") "LG R971-KN-1"))
      (libsource (lib "eagle-import") (part "LED_0805_GREEN"))
    )
    (comp (ref "LED3")
      (value "Green")
      (footprint "eagle-import:0805")
      (fields (field (name "PARTNO") "LG R971-KN-1"))
      (libsource (lib "eagle-import") (part "LED_0805_GREEN"))
    )
    (comp (ref "LED4")
      (value "Green")
      (footprint "eagle-import:0805")
      (fields (field (name "PARTNO") "LG R971-KN-1"))
      (libsource (lib "eagle-import") (part "LED_0805_GREEN"))
    )
    (comp (ref "LED5")
      (value "Green")
      (footprint "eagle-import:0805")
      (fields (field (name "PARTNO") "LG R971-KN-1"))
      (libsource (lib "eagle-import") (part "LED_0805_GREEN"))
    )
    (comp (ref "LED6")
      (value "Green")
      (footprint "eagle-import:0805")
      (fields (field (name "PARTNO") "LG R971-KN-1"))
      (libsource (lib "eagle-import") (part "LED_0805_GREEN"))
    )
    (comp (ref "LED7")
      (value "Green")
      (footprint "eagle-import:0805")
      (fields (field (name "PARTNO") "LG R971-KN-1"))
      (libsource (lib "eagle-import") (part "LED_0805_GREEN"))
    )
    (comp (ref "LED8")
      (value "Green")
      (footprint "eagle-import:0805")
      (fields (field (name "PARTNO") "LG R971-KN-1"))
      (libsource (lib "eagle-import") (part "LED_0805_GREEN"))
    )
    (comp (ref "LED9")
      (value "Green")
      (footprint "eagle-import:0805")
      (fields (field (name "PARTNO") "LG R971-KN-1"))
      (libsource (lib "eagle-import") (part "LED_0805_GREEN"))
    )
    (comp (ref "LED10")
      (value "Green")
      (footprint "eagle-import:0805")
      (fields (field (name "PARTNO") "LG R971-KN-1"))
      (libsource (lib "eagle-import") (part "LED_0805_GREEN"))
    )
    (comp (ref "LED11")
      (value "Green")
      (footprint "eagle-import:0805")
      (fields (field (name "PARTNO") "LG R971-KN-1"))
      (libsource (lib "eagle-import") (part "LED_0805_GREEN"))
    )
    (comp (ref "LED12")
      (value "Green")
      (footprint "eagle-import:0805")
      (fields (field (name "PARTNO") "LG R971-KN-1"))
      (libsource (lib "eagle-import") (part "LED_0805_GREEN"))
    )
    (comp (ref "LED13")
      (value "Green")
      (footprint "eagle-import:0805")
      (fields (field (name "PARTNO") "LG R971-KN-1"))
      (libsource (lib "eagle-import") (part "LED_0805_GREEN"))
    )
    (comp (ref "LED14")
      (value "Green")
      (footprint "eagle-import:0805")
      (fields (field (name "PARTNO") "LG R971-KN-1"))
      (libsource (lib "eagle-import") (part "LED_0805_GREEN"))
    )
    (comp (ref "LED15")
      (value "Green")
      (footprint "eagle-import:0805")
      (fields (field (name "PARTNO") "LG R971-KN-1"))
      (libsource (lib "eagle-import") (part "LED_0805_GREEN"))
    )
    (comp (ref "LED16")
      (value "Green")
      (footprint "eagle-import:0805")
      (fields (field (name "PARTNO") "LG R971-KN-1"))
      (libsource (lib "eagle-import") (part "LED_0805_GREEN"))
    )
    (comp (ref "P1")
      (value "1_X_1_1MM_PIN")
      (footprint "eagle-import:1_X_1_1MM_PIN")
      (libsource (lib "eagle-import") (part "1_X_1_1MM_PIN"))
    )
    (comp (ref "P2")
      (value "1_X_1_1MM_PIN")
      (footprint "eagle-import:1_X_1_1MM_PIN")
      (libsource (lib "eagle-import") (part "1_X_1_1MM_PIN"))
    )
    (comp (ref "P3")
      (value "1_X_1_1MM_PIN")
      (footprint "eagle-import:1_X_1_1MM_PIN")
      (libsource (lib "eagle-import") (part "1_X_1_1MM_PIN"))
    )
    (comp (ref "P4")
      (value "1_X_1_1MM_PIN")
      (footprint "eagle-import:1_X_1_1MM_PIN")
      (libsource (lib "eagle-import") (part "1_X_1_1MM_PIN"))
    )
    (comp (ref "R1")
      (value "6K49")
      (footprint "eagle-import:0402")
      (fields (field (name "PARTNO") "RMCF0402FT6K49"))
      (libsource (lib "eagle-import") (part "R_0402_6K49"))
    )
    (comp (ref "R2")
      (value "10K0")
      (footprint "eagle-import:0402")
      (fields (field (name "PARTNO") "RMCF0402JT10K0"))
      (libsource (lib "eagle-import") (part "R_0402_10K0"))
    )
    (comp (ref "R3")
      (value "10K0")
      (footprint "eagle-import:0402")
      (fields (field (name "PARTNO") "RMCF0402JT10K0"))
      (libsource (lib "eagle-import") (part "R_0402_10K0"))
    )
    (comp (ref "R4")
      (value "1K5")
      (footprint "eagle-import:0402")
      (fields (field (name "PARTNO") "RMCF0402JT1K50"))
      (libsource (lib "eagle-import") (part "R_0402_1K5"))
    )
    (comp (ref "R5")
      (value "470R0")
      (footprint "eagle-import:0402")
      (fields (field (name "PARTNO") "RMCF0402JT470R"))
      (libsource (lib "eagle-import") (part "R_0402_470R0"))
    )
    (comp (ref "R6")
      (value "1K5")
      (footprint "eagle-import:0402")
      (fields (field (name "PARTNO") "RMCF0402JT1K50"))
      (libsource (lib "eagle-import") (part "R_0402_1K5"))
    )
    (comp (ref "R7")
      (value "470R0")
      (footprint "eagle-import:0402")
      (fields (field (name "PARTNO") "RMCF0402JT470R"))
      (libsource (lib "eagle-import") (part "R_0402_470R0"))
    )
    (comp (ref "R8")
      (value "470R0")
      (footprint "eagle-import:0402")
      (fields (field (name "PARTNO") "RMCF0402JT470R"))
      (libsource (lib "eagle-import") (part "R_0402_470R0"))
    )
    (comp (ref "R9")
      (value "33R0")
      (footprint "eagle-import:0402")
      (fields (field (name "PARTNO") "RMCF0402JT33R0"))
      (libsource (lib "eagle-import") (part "R_0402_33R0"))
    )
    (comp (ref "R10")
      (value "33R0")
      (footprint "eagle-import:0402")
      (fields (field (name "PARTNO") "RMCF0402JT33R0"))
      (libsource (lib "eagle-import") (part "R_0402_33R0"))
    )
    (comp (ref "R11")
      (value "33R0")
      (footprint "eagle-import:0402")
      (fields (field (name "PARTNO") "RMCF0402JT33R0"))
      (libsource (lib "eagle-import") (part "R_0402_33R0"))
    )
    (comp (ref "R12")
      (value "33R0")
      (footprint "eagle-import:0402")
      (fields (field (name "PARTNO") "RMCF0402JT33R0"))
      (libsource (lib "eagle-import") (part "R_0402_33R0"))
    )
    (comp (ref "R13")
      (value "10K0")
      (footprint "eagle-import:0402")
      (fields (field (name "PARTNO") "RMCF0402JT10K0"))
      (libsource (lib "eagle-import") (part "R_0402_10K0"))
    )
    (comp (ref "R14")
      (value "1K0")
      (footprint "eagle-import:0402")
      (fields (field (name "PARTNO") "CRG0402J1K0"))
      (libsource (lib "eagle-import") (part "R_0402_1K0"))
    )
    (comp (ref "R15")
      (value "1K0")
      (footprint "eagle-import:0402")
      (fields (field (name "PARTNO") "CRG0402J1K0"))
      (libsource (lib "eagle-import") (part "R_0402_1K0"))
    )
    (comp (ref "R16")
      (value "15K0")
      (footprint "eagle-import:0402")
      (fields (field (name "PARTNO") "RMCF0402JT15K0"))
      (libsource (lib "eagle-import") (part "R_0402_15K0"))
    )
    (comp (ref "R17")
      (value "27R0")
      (footprint "eagle-import:0402")
      (fields (field (name "PARTNO") "RMCF0402JT27R0"))
      (libsource (lib "eagle-import") (part "R_0402_27R0"))
    )
    (comp (ref "R18")
      (value "27R0")
      (footprint "eagle-import:0402")
      (fields (field (name "PARTNO") "RMCF0402JT27R0"))
      (libsource (lib "eagle-import") (part "R_0402_27R0"))
    )
    (comp (ref "R19")
      (value "10K0")
      (footprint "eagle-import:0402")
      (fields (field (name "PARTNO") "RMCF0402JT10K0"))
      (libsource (lib "eagle-import") (part "R_0402_10K0"))
    )
    (comp (ref "R20")
      (value "10K0")
      (footprint "eagle-import:0402")
      (fields (field (name "PARTNO") "RMCF0402JT10K0"))
      (libsource (lib "eagle-import") (part "R_0402_10K0"))
    )
    (comp (ref "R21")
      (value "30K0")
      (footprint "eagle-import:0402")
      (fields (field (name "PARTNO") "RC0402JR-0730KL"))
      (libsource (lib "eagle-import") (part "R_0402_30K0"))
    )
    (comp (ref "R22")
      (value "2K2")
      (footprint "eagle-import:0402")
      (fields (field (name "PARTNO") "RMCF0402JT2K20"))
      (libsource (lib "eagle-import") (part "R_0402_2K2"))
    )
    (comp (ref "R23")
      (value "10K0")
      (footprint "eagle-import:0402")
      (fields (field (name "PARTNO") "RMCF0402JT10K0"))
      (libsource (lib "eagle-import") (part "R_0402_10K0"))
    )
    (comp (ref "R24")
      (value "10K0")
      (footprint "eagle-import:0402")
      (fields (field (name "PARTNO") "RMCF0402JT10K0"))
      (libsource (lib "eagle-import") (part "R_0402_10K0"))
    )
    (comp (ref "R25")
      (value "100K")
      (footprint "eagle-import:0402")
      (libsource (lib "eagle-import") (part "R_0402"))
    )
    (comp (ref "R26")
      (value "100K")
      (footprint "eagle-import:0402")
      (libsource (lib "eagle-import") (part "R_0402"))
    )
    (comp (ref "R27")
      (value "100K")
      (footprint "eagle-import:0402")
      (libsource (lib "eagle-import") (part "R_0402"))
    )
    (comp (ref "R28")
      (value "2.2K")
      (footprint "eagle-import:0402")
      (libsource (lib "eagle-import") (part "R_0402"))
    )
    (comp (ref "R29")
      (value "500R0")
      (footprint "eagle-import:0402")
      (libsource (lib "eagle-import") (part "R_0402"))
    )
    (comp (ref "R30")
      (value "500R0")
      (footprint "eagle-import:0402")
      (libsource (lib "eagle-import") (part "R_0402"))
    )
    (comp (ref "R31")
      (value "470R0")
      (footprint "eagle-import:0402")
      (fields (field (name "PARTNO") "RMCF0402JT470R"))
      (libsource (lib "eagle-import") (part "R_0402_470R0"))
    )
    (comp (ref "R32")
      (value "470R0")
      (footprint "eagle-import:0402")
      (fields (field (name "PARTNO") "RMCF0402JT470R"))
      (libsource (lib "eagle-import") (part "R_0402_470R0"))
    )
    (comp (ref "R33")
      (value "470R0")
      (footprint "eagle-import:0402")
      (fields (field (name "PARTNO") "RMCF0402JT470R"))
      (libsource (lib "eagle-import") (part "R_0402_470R0"))
    )
    (comp (ref "R34")
      (value "10K0")
      (footprint "eagle-import:0402")
      (fields (field (name "PARTNO") "RMCF0402JT10K0"))
      (libsource (lib "eagle-import") (part "R_0402_10K0"))
    )
    (comp (ref "R35")
      (value "2.2K")
      (footprint "eagle-import:0402")
      (libsource (lib "eagle-import") (part "R_0402"))
    )
    (comp (ref "R36")
      (value "470R0")
      (footprint "eagle-import:0402")
      (fields (field (name "PARTNO") "RMCF0402JT470R"))
      (libsource (lib "eagle-import") (part "R_0402_470R0"))
    )
    (comp (ref "R37")
      (value "1k")
      (footprint "eagle-import:0805")
      (libsource (lib "eagle-import") (part "R_0805"))
    )
    (comp (ref "R38")
      (value "33")
      (footprint "eagle-import:0805")
      (libsource (lib "eagle-import") (part "R_0805"))
    )
    (comp (ref "R39")
      (value "33")
      (footprint "eagle-import:0805")
      (libsource (lib "eagle-import") (part "R_0805"))
    )
    (comp (ref "R40")
      (value "33")
      (footprint "eagle-import:0805")
      (libsource (lib "eagle-import") (part "R_0805"))
    )
    (comp (ref "R41")
      (value "1k")
      (footprint "eagle-import:0805")
      (libsource (lib "eagle-import") (part "R_0805"))
    )
    (comp (ref "R42")
      (value "1k")
      (footprint "eagle-import:0805")
      (libsource (lib "eagle-import") (part "R_0805"))
    )
    (comp (ref "R43")
      (value "1k")
      (footprint "eagle-import:0805")
      (libsource (lib "eagle-import") (part "R_0805"))
    )
    (comp (ref "R44")
      (value "33")
      (footprint "eagle-import:0805")
      (libsource (lib "eagle-import") (part "R_0805"))
    )
    (comp (ref "R45")
      (value "33")
      (footprint "eagle-import:0805")
      (libsource (lib "eagle-import") (part "R_0805"))
    )
    (comp (ref "R46")
      (value "33")
      (footprint "eagle-import:0805")
      (libsource (lib "eagle-import") (part "R_0805"))
    )
    (comp (ref "R47")
      (value "1k")
      (footprint "eagle-import:0805")
      (libsource (lib "eagle-import") (part "R_0805"))
    )
    (comp (ref "R48")
      (value "1k")
      (footprint "eagle-import:0805")
      (libsource (lib "eagle-import") (part "R_0805"))
    )
    (comp (ref "R49")
      (value "500R0")
      (footprint "eagle-import:0402")
      (libsource (lib "eagle-import") (part "R_0402"))
    )
    (comp (ref "R50")
      (value "500R0")
      (footprint "eagle-import:0402")
      (libsource (lib "eagle-import") (part "R_0402"))
    )
    (comp (ref "R51")
      (value "470R0")
      (footprint "eagle-import:0402")
      (fields (field (name "PARTNO") "RMCF0402JT470R"))
      (libsource (lib "eagle-import") (part "R_0402_470R0"))
    )
    (comp (ref "R52")
      (value "470R0")
      (footprint "eagle-import:0402")
      (fields (field (name "PARTNO") "RMCF0402JT470R"))
      (libsource (lib "eagle-import") (part "R_0402_470R0"))
    )
    (comp (ref "R53")
      (value "10K0")
      (footprint "eagle-import:0402")
      (fields (field (name "PARTNO") "RMCF0402JT10K0"))
      (libsource (lib "eagle-import") (part "R_0402_10K0"))
    )
    (comp (ref "R54")
      (value "2.2K")
      (footprint "eagle-import:0402")
      (libsource (lib "eagle-import") (part "R_0402"))
    )
    (comp (ref "R55")
      (value "470R0")
      (footprint "eagle-import:0402")
      (fields (field (name "PARTNO") "RMCF0402JT470R"))
      (libsource (lib "eagle-import") (part "R_0402_470R0"))
    )
    (comp (ref "R56")
      (value "10K0")
      (footprint "eagle-import:0402")
      (fields (field (name "PARTNO") "RMCF0402JT10K0"))
      (libsource (lib "eagle-import") (part "R_0402_10K0"))
    )
    (comp (ref "R57")
      (value "2.2K")
      (footprint "eagle-import:0402")
      (libsource (lib "eagle-import") (part "R_0402"))
    )
    (comp (ref "R58")
      (value "470R0")
      (footprint "eagle-import:0402")
      (fields (field (name "PARTNO") "RMCF0402JT470R"))
      (libsource (lib "eagle-import") (part "R_0402_470R0"))
    )
    (comp (ref "R59")
      (value "10K0")
      (footprint "eagle-import:0402")
      (fields (field (name "PARTNO") "RMCF0402JT10K0"))
      (libsource (lib "eagle-import") (part "R_0402_10K0"))
    )
    (comp (ref "R60")
      (value "2.2K")
      (footprint "eagle-import:0402")
      (libsource (lib "eagle-import") (part "R_0402"))
    )
    (comp (ref "R61")
      (value "1k")
      (footprint "eagle-import:0805")
      (libsource (lib "eagle-import") (part "R_0805"))
    )
    (comp (ref "R62")
      (value "33")
      (footprint "eagle-import:0805")
      (libsource (lib "eagle-import") (part "R_0805"))
    )
    (comp (ref "R63")
      (value "33")
      (footprint "eagle-import:0805")
      (libsource (lib "eagle-import") (part "R_0805"))
    )
    (comp (ref "R64")
      (value "33")
      (footprint "eagle-import:0805")
      (libsource (lib "eagle-import") (part "R_0805"))
    )
    (comp (ref "R65")
      (value "1k")
      (footprint "eagle-import:0805")
      (libsource (lib "eagle-import") (part "R_0805"))
    )
    (comp (ref "R66")
      (value "1k")
      (footprint "eagle-import:0805")
      (libsource (lib "eagle-import") (part "R_0805"))
    )
    (comp (ref "R67")
      (value "1k")
      (footprint "eagle-import:0805")
      (libsource (lib "eagle-import") (part "R_0805"))
    )
    (comp (ref "R68")
      (value "33")
      (footprint "eagle-import:0805")
      (libsource (lib "eagle-import") (part "R_0805"))
    )
    (comp (ref "R69")
      (value "33")
      (footprint "eagle-import:0805")
      (libsource (lib "eagle-import") (part "R_0805"))
    )
    (comp (ref "R70")
      (value "33")
      (footprint "eagle-import:0805")
      (libsource (lib "eagle-import") (part "R_0805"))
    )
    (comp (ref "R71")
      (value "1k")
      (footprint "eagle-import:0805")
      (libsource (lib "eagle-import") (part "R_0805"))
    )
    (comp (ref "R72")
      (value "1k")
      (footprint "eagle-import:0805")
      (libsource (lib "eagle-import") (part "R_0805"))
    )
    (comp (ref "R73")
      (value "470R0")
      (footprint "eagle-import:0402")
      (fields (field (name "PARTNO") "RMCF0402JT470R"))
      (libsource (lib "eagle-import") (part "R_0402_470R0"))
    )
    (comp (ref "R74")
      (value "10K0")
      (footprint "eagle-import:0402")
      (fields (field (name "PARTNO") "RMCF0402JT10K0"))
      (libsource (lib "eagle-import") (part "R_0402_10K0"))
    )
    (comp (ref "R75")
      (value "2.2K")
      (footprint "eagle-import:0402")
      (libsource (lib "eagle-import") (part "R_0402"))
    )
    (comp (ref "R76")
      (value "470R0")
      (footprint "eagle-import:0402")
      (fields (field (name "PARTNO") "RMCF0402JT470R"))
      (libsource (lib "eagle-import") (part "R_0402_470R0"))
    )
    (comp (ref "R77")
      (value "10K0")
      (footprint "eagle-import:0402")
      (fields (field (name "PARTNO") "RMCF0402JT10K0"))
      (libsource (lib "eagle-import") (part "R_0402_10K0"))
    )
    (comp (ref "R78")
      (value "2.2K")
      (footprint "eagle-import:0402")
      (libsource (lib "eagle-import") (part "R_0402"))
    )
    (comp (ref "R79")
      (value "470R0")
      (footprint "eagle-import:0402")
      (fields (field (name "PARTNO") "RMCF0402JT470R"))
      (libsource (lib "eagle-import") (part "R_0402_470R0"))
    )
    (comp (ref "R80")
      (value "10K0")
      (footprint "eagle-import:0402")
      (fields (field (name "PARTNO") "RMCF0402JT10K0"))
      (libsource (lib "eagle-import") (part "R_0402_10K0"))
    )
    (comp (ref "R81")
      (value "2.2K")
      (footprint "eagle-import:0402")
      (libsource (lib "eagle-import") (part "R_0402"))
    )
    (comp (ref "R82")
      (value "470R0")
      (footprint "eagle-import:0402")
      (fields (field (name "PARTNO") "RMCF0402JT470R"))
      (libsource (lib "eagle-import") (part "R_0402_470R0"))
    )
    (comp (ref "R83")
      (value "10K0")
      (footprint "eagle-import:0402")
      (fields (field (name "PARTNO") "RMCF0402JT10K0"))
      (libsource (lib "eagle-import") (part "R_0402_10K0"))
    )
    (comp (ref "R84")
      (value "2.2K")
      (footprint "eagle-import:0402")
      (libsource (lib "eagle-import") (part "R_0402"))
    )
    (comp (ref "R85")
      (value "1k")
      (footprint "eagle-import:0805")
      (libsource (lib "eagle-import") (part "R_0805"))
    )
    (comp (ref "R86")
      (value "33")
      (footprint "eagle-import:0805")
      (libsource (lib "eagle-import") (part "R_0805"))
    )
    (comp (ref "R87")
      (value "33")
      (footprint "eagle-import:0805")
      (libsource (lib "eagle-import") (part "R_0805"))
    )
    (comp (ref "R88")
      (value "33")
      (footprint "eagle-import:0805")
      (libsource (lib "eagle-import") (part "R_0805"))
    )
    (comp (ref "R89")
      (value "1k")
      (footprint "eagle-import:0805")
      (libsource (lib "eagle-import") (part "R_0805"))
    )
    (comp (ref "R90")
      (value "1k")
      (footprint "eagle-import:0805")
      (libsource (lib "eagle-import") (part "R_0805"))
    )
    (comp (ref "R91")
      (value "1k")
      (footprint "eagle-import:0805")
      (libsource (lib "eagle-import") (part "R_0805"))
    )
    (comp (ref "R92")
      (value "33")
      (footprint "eagle-import:0805")
      (libsource (lib "eagle-import") (part "R_0805"))
    )
    (comp (ref "R93")
      (value "33")
      (footprint "eagle-import:0805")
      (libsource (lib "eagle-import") (part "R_0805"))
    )
    (comp (ref "R94")
      (value "33")
      (footprint "eagle-import:0805")
      (libsource (lib "eagle-import") (part "R_0805"))
    )
    (comp (ref "R95")
      (value "1k")
      (footprint "eagle-import:0805")
      (libsource (lib "eagle-import") (part "R_0805"))
    )
    (comp (ref "R96")
      (value "1k")
      (footprint "eagle-import:0805")
      (libsource (lib "eagle-import") (part "R_0805"))
    )
    (comp (ref "R97")
      (value "470R0")
      (footprint "eagle-import:0402")
      (fields (field (name "PARTNO") "RMCF0402JT470R"))
      (libsource (lib "eagle-import") (part "R_0402_470R0"))
    )
    (comp (ref "R98")
      (value "10K0")
      (footprint "eagle-import:0402")
      (fields (field (name "PARTNO") "RMCF0402JT10K0"))
      (libsource (lib "eagle-import") (part "R_0402_10K0"))
    )
    (comp (ref "R99")
      (value "2.2K")
      (footprint "eagle-import:0402")
      (libsource (lib "eagle-import") (part "R_0402"))
    )
    (comp (ref "R100")
      (value "470R0")
      (footprint "eagle-import:0402")
      (fields (field (name "PARTNO") "RMCF0402JT470R"))
      (libsource (lib "eagle-import") (part "R_0402_470R0"))
    )
    (comp (ref "R101")
      (value "10K0")
      (footprint "eagle-import:0402")
      (fields (field (name "PARTNO") "RMCF0402JT10K0"))
      (libsource (lib "eagle-import") (part "R_0402_10K0"))
    )
    (comp (ref "R102")
      (value "100K")
      (footprint "eagle-import:0402")
      (libsource (lib "eagle-import") (part "R_0402"))
    )
    (comp (ref "R103")
      (value "100K")
      (footprint "eagle-import:0402")
      (libsource (lib "eagle-import") (part "R_0402"))
    )
    (comp (ref "R104")
      (value "100K")
      (footprint "eagle-import:0402")
      (libsource (lib "eagle-import") (part "R_0402"))
    )
    (comp (ref "R105")
      (value "100K")
      (footprint "eagle-import:0402")
      (libsource (lib "eagle-import") (part "R_0402"))
    )
    (comp (ref "R106")
      (value "100K")
      (footprint "eagle-import:0402")
      (libsource (lib "eagle-import") (part "R_0402"))
    )
    (comp (ref "R107")
      (value "100K")
      (footprint "eagle-import:0402")
      (libsource (lib "eagle-import") (part "R_0402"))
    )
    (comp (ref "R108")
      (value "100K")
      (footprint "eagle-import:0402")
      (libsource (lib "eagle-import") (part "R_0402"))
    )
    (comp (ref "R109")
      (value "1k")
      (footprint "eagle-import:0805")
      (libsource (lib "eagle-import") (part "R_0805"))
    )
    (comp (ref "R110")
      (value "33")
      (footprint "eagle-import:0805")
      (libsource (lib "eagle-import") (part "R_0805"))
    )
    (comp (ref "R111")
      (value "33")
      (footprint "eagle-import:0805")
      (libsource (lib "eagle-import") (part "R_0805"))
    )
    (comp (ref "R112")
      (value "33")
      (footprint "eagle-import:0805")
      (libsource (lib "eagle-import") (part "R_0805"))
    )
    (comp (ref "R113")
      (value "1k")
      (footprint "eagle-import:0805")
      (libsource (lib "eagle-import") (part "R_0805"))
    )
    (comp (ref "R114")
      (value "1k")
      (footprint "eagle-import:0805")
      (libsource (lib "eagle-import") (part "R_0805"))
    )
    (comp (ref "R115")
      (value "1k")
      (footprint "eagle-import:0805")
      (libsource (lib "eagle-import") (part "R_0805"))
    )
    (comp (ref "R116")
      (value "33")
      (footprint "eagle-import:0805")
      (libsource (lib "eagle-import") (part "R_0805"))
    )
    (comp (ref "R117")
      (value "33")
      (footprint "eagle-import:0805")
      (libsource (lib "eagle-import") (part "R_0805"))
    )
    (comp (ref "R118")
      (value "33")
      (footprint "eagle-import:0805")
      (libsource (lib "eagle-import") (part "R_0805"))
    )
    (comp (ref "R119")
      (value "1k")
      (footprint "eagle-import:0805")
      (libsource (lib "eagle-import") (part "R_0805"))
    )
    (comp (ref "R120")
      (value "1k")
      (footprint "eagle-import:0805")
      (libsource (lib "eagle-import") (part "R_0805"))
    )
    (comp (ref "R133")
      (value "1k")
      (footprint "eagle-import:0805")
      (libsource (lib "eagle-import") (part "R_0805"))
    )
    (comp (ref "R134")
      (value "33")
      (footprint "eagle-import:0805")
      (libsource (lib "eagle-import") (part "R_0805"))
    )
    (comp (ref "R135")
      (value "33")
      (footprint "eagle-import:0805")
      (libsource (lib "eagle-import") (part "R_0805"))
    )
    (comp (ref "R136")
      (value "33")
      (footprint "eagle-import:0805")
      (libsource (lib "eagle-import") (part "R_0805"))
    )
    (comp (ref "R137")
      (value "1k")
      (footprint "eagle-import:0805")
      (libsource (lib "eagle-import") (part "R_0805"))
    )
    (comp (ref "R138")
      (value "1k")
      (footprint "eagle-import:0805")
      (libsource (lib "eagle-import") (part "R_0805"))
    )
    (comp (ref "R139")
      (value "1k")
      (footprint "eagle-import:0805")
      (libsource (lib "eagle-import") (part "R_0805"))
    )
    (comp (ref "R140")
      (value "33")
      (footprint "eagle-import:0805")
      (libsource (lib "eagle-import") (part "R_0805"))
    )
    (comp (ref "R141")
      (value "33")
      (footprint "eagle-import:0805")
      (libsource (lib "eagle-import") (part "R_0805"))
    )
    (comp (ref "R142")
      (value "33")
      (footprint "eagle-import:0805")
      (libsource (lib "eagle-import") (part "R_0805"))
    )
    (comp (ref "R143")
      (value "1k")
      (footprint "eagle-import:0805")
      (libsource (lib "eagle-import") (part "R_0805"))
    )
    (comp (ref "R144")
      (value "1k")
      (footprint "eagle-import:0805")
      (libsource (lib "eagle-import") (part "R_0805"))
    )
    (comp (ref "R157")
      (value "1k")
      (footprint "eagle-import:0805")
      (libsource (lib "eagle-import") (part "R_0805"))
    )
    (comp (ref "R158")
      (value "33")
      (footprint "eagle-import:0805")
      (libsource (lib "eagle-import") (part "R_0805"))
    )
    (comp (ref "R159")
      (value "33")
      (footprint "eagle-import:0805")
      (libsource (lib "eagle-import") (part "R_0805"))
    )
    (comp (ref "R160")
      (value "33")
      (footprint "eagle-import:0805")
      (libsource (lib "eagle-import") (part "R_0805"))
    )
    (comp (ref "R161")
      (value "1k")
      (footprint "eagle-import:0805")
      (libsource (lib "eagle-import") (part "R_0805"))
    )
    (comp (ref "R162")
      (value "1k")
      (footprint "eagle-import:0805")
      (libsource (lib "eagle-import") (part "R_0805"))
    )
    (comp (ref "R163")
      (value "1k")
      (footprint "eagle-import:0805")
      (libsource (lib "eagle-import") (part "R_0805"))
    )
    (comp (ref "R164")
      (value "33")
      (footprint "eagle-import:0805")
      (libsource (lib "eagle-import") (part "R_0805"))
    )
    (comp (ref "R165")
      (value "33")
      (footprint "eagle-import:0805")
      (libsource (lib "eagle-import") (part "R_0805"))
    )
    (comp (ref "R166")
      (value "33")
      (footprint "eagle-import:0805")
      (libsource (lib "eagle-import") (part "R_0805"))
    )
    (comp (ref "R167")
      (value "1k")
      (footprint "eagle-import:0805")
      (libsource (lib "eagle-import") (part "R_0805"))
    )
    (comp (ref "R168")
      (value "1k")
      (footprint "eagle-import:0805")
      (libsource (lib "eagle-import") (part "R_0805"))
    )
    (comp (ref "RJ1")
      (value "RJ45")
      (footprint "eagle-import:RJ45_TH_ELEC")
      (fields (field (name "PARTNO") "13F-64GYD2PL2NL"))
      (libsource (lib "eagle-import") (part "RJ45_WITH_ELEC"))
    )
    (comp (ref "U$1")
      (value "RELAY_KYOTO_KF0604D")
      (footprint "eagle-import:RELAY_KYOTO_KF0604D")
      (libsource (lib "eagle-import") (part "RELAY_KYOTO_KF0604D"))
    )
    (comp (ref "U$2")
      (value "RELAY_KYOTO_KF0604D")
      (footprint "eagle-import:RELAY_KYOTO_KF0604D")
      (libsource (lib "eagle-import") (part "RELAY_KYOTO_KF0604D"))
    )
    (comp (ref "U$7")
      (value "RELAY_KYOTO_KF0604D")
      (footprint "eagle-import:RELAY_KYOTO_KF0604D")
      (libsource (lib "eagle-import") (part "RELAY_KYOTO_KF0604D"))
    )
    (comp (ref "U$8")
      (value "RELAY_KYOTO_KF0604D")
      (footprint "eagle-import:RELAY_KYOTO_KF0604D")
      (libsource (lib "eagle-import") (part "RELAY_KYOTO_KF0604D"))
    )
    (comp (ref "U1")
      (value "KSZ8081_QFN_24")
      (footprint "eagle-import:QFN-24-M")
      (fields (field (name "PARTNO") "KSZ8081RNACA"))
      (libsource (lib "eagle-import") (part "KSZ8081RNACAQFN-24-M"))
    )
    (comp (ref "U2")
      (value "AP2151DWG-7")
      (footprint "eagle-import:SOT-23-5")
      (fields (field (name "PARTNO") "AP2151WG-7"))
      (libsource (lib "eagle-import") (part "AP2151DWG-7"))
    )
    (comp (ref "U3")
      (value "S7G2LQFP176")
      (footprint "eagle-import:LQFP176_24X24")
      (fields (field (name "PARTNO") "R7FS7G27H3A01CFC#AA0"))
      (libsource (lib "eagle-import") (part "RENESAS_S7G2_X_176"))
    )
    (comp (ref "U5")
      (value "NPN")
      (footprint "eagle-import:SOT323")
      (fields (field (name "PARTNO") "BC846BW_NPN"))
      (libsource (lib "eagle-import") (part "BC846BW"))
    )
    (comp (ref "U6")
      (value "NPN")
      (footprint "eagle-import:SOT323")
      (fields (field (name "PARTNO") "BC846BW_NPN"))
      (libsource (lib "eagle-import") (part "BC846BW"))
    )
    (comp (ref "U7")
      (value "NPN")
      (footprint "eagle-import:SOT323")
      (fields (field (name "PARTNO") "BC846BW_NPN"))
      (libsource (lib "eagle-import") (part "BC846BW"))
    )
    (comp (ref "U8")
      (value "NPN")
      (footprint "eagle-import:SOT323")
      (fields (field (name "PARTNO") "BC846BW_NPN"))
      (libsource (lib "eagle-import") (part "BC846BW"))
    )
    (comp (ref "U9")
      (value "NPN")
      (footprint "eagle-import:SOT323")
      (fields (field (name "PARTNO") "BC846BW_NPN"))
      (libsource (lib "eagle-import") (part "BC846BW"))
    )
    (comp (ref "U10")
      (value "NPN")
      (footprint "eagle-import:SOT323")
      (fields (field (name "PARTNO") "BC846BW_NPN"))
      (libsource (lib "eagle-import") (part "BC846BW"))
    )
    (comp (ref "U11")
      (value "NPN")
      (footprint "eagle-import:SOT323")
      (fields (field (name "PARTNO") "BC846BW_NPN"))
      (libsource (lib "eagle-import") (part "BC846BW"))
    )
    (comp (ref "U12")
      (value "NPN")
      (footprint "eagle-import:SOT323")
      (fields (field (name "PARTNO") "BC846BW_NPN"))
      (libsource (lib "eagle-import") (part "BC846BW"))
    )
    (comp (ref "U13")
      (value "NPN")
      (footprint "eagle-import:SOT323")
      (fields (field (name "PARTNO") "BC846BW_NPN"))
      (libsource (lib "eagle-import") (part "BC846BW"))
    )
    (comp (ref "U14")
      (value "NPN")
      (footprint "eagle-import:SOT323")
      (fields (field (name "PARTNO") "BC846BW_NPN"))
      (libsource (lib "eagle-import") (part "BC846BW"))
    )
    (comp (ref "U15")
      (value "NPN")
      (footprint "eagle-import:SOT323")
      (fields (field (name "PARTNO") "BC846BW_NPN"))
      (libsource (lib "eagle-import") (part "BC846BW"))
    )
    (comp (ref "U16")
      (value "NPN")
      (footprint "eagle-import:SOT323")
      (fields (field (name "PARTNO") "BC846BW_NPN"))
      (libsource (lib "eagle-import") (part "BC846BW"))
    )
    (comp (ref "U17")
      (value "NPN")
      (footprint "eagle-import:SOT323")
      (fields (field (name "PARTNO") "BC846BW_NPN"))
      (libsource (lib "eagle-import") (part "BC846BW"))
    )
    (comp (ref "U18")
      (value "NPN")
      (footprint "eagle-import:SOT323")
      (fields (field (name "PARTNO") "BC846BW_NPN"))
      (libsource (lib "eagle-import") (part "BC846BW"))
    )
    (comp (ref "U19")
      (value "NPN")
      (footprint "eagle-import:SOT323")
      (fields (field (name "PARTNO") "BC846BW_NPN"))
      (libsource (lib "eagle-import") (part "BC846BW"))
    )
    (comp (ref "U20")
      (value "NPN")
      (footprint "eagle-import:SOT323")
      (fields (field (name "PARTNO") "BC846BW_NPN"))
      (libsource (lib "eagle-import") (part "BC846BW"))
    )
    (comp (ref "U21")
      (value "NPN")
      (footprint "eagle-import:SOT323")
      (fields (field (name "PARTNO") "BC846BW_NPN"))
      (libsource (lib "eagle-import") (part "BC846BW"))
    )
    (comp (ref "U22")
      (value "NPN")
      (footprint "eagle-import:SOT323")
      (fields (field (name "PARTNO") "BC846BW_NPN"))
      (libsource (lib "eagle-import") (part "BC846BW"))
    )
    (comp (ref "U23")
      (value "NPN")
      (footprint "eagle-import:SOT323")
      (fields (field (name "PARTNO") "BC846BW_NPN"))
      (libsource (lib "eagle-import") (part "BC846BW"))
    )
    (comp (ref "U24")
      (value "NPN")
      (footprint "eagle-import:SOT323")
      (fields (field (name "PARTNO") "BC846BW_NPN"))
      (libsource (lib "eagle-import") (part "BC846BW"))
    )
    (comp (ref "U25")
      (value "NPN")
      (footprint "eagle-import:SOT323")
      (fields (field (name "PARTNO") "BC846BW_NPN"))
      (libsource (lib "eagle-import") (part "BC846BW"))
    )
    (comp (ref "U26")
      (value "NPN")
      (footprint "eagle-import:SOT323")
      (fields (field (name "PARTNO") "BC846BW_NPN"))
      (libsource (lib "eagle-import") (part "BC846BW"))
    )
    (comp (ref "U27")
      (value "NPN")
      (footprint "eagle-import:SOT323")
      (fields (field (name "PARTNO") "BC846BW_NPN"))
      (libsource (lib "eagle-import") (part "BC846BW"))
    )
    (comp (ref "U28")
      (value "NPN")
      (footprint "eagle-import:SOT323")
      (fields (field (name "PARTNO") "BC846BW_NPN"))
      (libsource (lib "eagle-import") (part "BC846BW"))
    )
    (comp (ref "U29")
      (value "NPN")
      (footprint "eagle-import:SOT323")
      (fields (field (name "PARTNO") "BC846BW_NPN"))
      (libsource (lib "eagle-import") (part "BC846BW"))
    )
    (comp (ref "U30")
      (value "NPN")
      (footprint "eagle-import:SOT323")
      (fields (field (name "PARTNO") "BC846BW_NPN"))
      (libsource (lib "eagle-import") (part "BC846BW"))
    )
    (comp (ref "U34")
      (value "NPN")
      (footprint "eagle-import:SOT323")
      (fields (field (name "PARTNO") "BC846BW_NPN"))
      (libsource (lib "eagle-import") (part "BC846BW"))
    )
    (comp (ref "U35")
      (value "NPN")
      (footprint "eagle-import:SOT323")
      (fields (field (name "PARTNO") "BC846BW_NPN"))
      (libsource (lib "eagle-import") (part "BC846BW"))
    )
    (comp (ref "U36")
      (value "NPN")
      (footprint "eagle-import:SOT323")
      (fields (field (name "PARTNO") "BC846BW_NPN"))
      (libsource (lib "eagle-import") (part "BC846BW"))
    )
    (comp (ref "U37")
      (value "NPN")
      (footprint "eagle-import:SOT323")
      (fields (field (name "PARTNO") "BC846BW_NPN"))
      (libsource (lib "eagle-import") (part "BC846BW"))
    )
    (comp (ref "U38")
      (value "NPN")
      (footprint "eagle-import:SOT323")
      (fields (field (name "PARTNO") "BC846BW_NPN"))
      (libsource (lib "eagle-import") (part "BC846BW"))
    )
    (comp (ref "U39")
      (value "NPN")
      (footprint "eagle-import:SOT323")
      (fields (field (name "PARTNO") "BC846BW_NPN"))
      (libsource (lib "eagle-import") (part "BC846BW"))
    )
    (comp (ref "U46")
      (value "NPN")
      (footprint "eagle-import:SOT323")
      (fields (field (name "PARTNO") "BC846BW_NPN"))
      (libsource (lib "eagle-import") (part "BC846BW"))
    )
    (comp (ref "U47")
      (value "NPN")
      (footprint "eagle-import:SOT323")
      (fields (field (name "PARTNO") "BC846BW_NPN"))
      (libsource (lib "eagle-import") (part "BC846BW"))
    )
    (comp (ref "U48")
      (value "NPN")
      (footprint "eagle-import:SOT323")
      (fields (field (name "PARTNO") "BC846BW_NPN"))
      (libsource (lib "eagle-import") (part "BC846BW"))
    )
    (comp (ref "U49")
      (value "NPN")
      (footprint "eagle-import:SOT323")
      (fields (field (name "PARTNO") "BC846BW_NPN"))
      (libsource (lib "eagle-import") (part "BC846BW"))
    )
    (comp (ref "U50")
      (value "NPN")
      (footprint "eagle-import:SOT323")
      (fields (field (name "PARTNO") "BC846BW_NPN"))
      (libsource (lib "eagle-import") (part "BC846BW"))
    )
    (comp (ref "U51")
      (value "NPN")
      (footprint "eagle-import:SOT323")
      (fields (field (name "PARTNO") "BC846BW_NPN"))
      (libsource (lib "eagle-import") (part "BC846BW"))
    )
    (comp (ref "U58")
      (value "NPN")
      (footprint "eagle-import:SOT323")
      (fields (field (name "PARTNO") "BC846BW_NPN"))
      (libsource (lib "eagle-import") (part "BC846BW"))
    )
    (comp (ref "U59")
      (value "NPN")
      (footprint "eagle-import:SOT323")
      (fields (field (name "PARTNO") "BC846BW_NPN"))
      (libsource (lib "eagle-import") (part "BC846BW"))
    )
    (comp (ref "U60")
      (value "NPN")
      (footprint "eagle-import:SOT323")
      (fields (field (name "PARTNO") "BC846BW_NPN"))
      (libsource (lib "eagle-import") (part "BC846BW"))
    )
    (comp (ref "U61")
      (value "NPN")
      (footprint "eagle-import:SOT323")
      (fields (field (name "PARTNO") "BC846BW_NPN"))
      (libsource (lib "eagle-import") (part "BC846BW"))
    )
    (comp (ref "U62")
      (value "NPN")
      (footprint "eagle-import:SOT323")
      (fields (field (name "PARTNO") "BC846BW_NPN"))
      (libsource (lib "eagle-import") (part "BC846BW"))
    )
    (comp (ref "U63")
      (value "NPN")
      (footprint "eagle-import:SOT323")
      (fields (field (name "PARTNO") "BC846BW_NPN"))
      (libsource (lib "eagle-import") (part "BC846BW"))
    )
    (comp (ref "U70")
      (value "NPN")
      (footprint "eagle-import:SOT323")
      (fields (field (name "PARTNO") "BC846BW_NPN"))
      (libsource (lib "eagle-import") (part "BC846BW"))
    )
    (comp (ref "U71")
      (value "NPN")
      (footprint "eagle-import:SOT323")
      (fields (field (name "PARTNO") "BC846BW_NPN"))
      (libsource (lib "eagle-import") (part "BC846BW"))
    )
    (comp (ref "U72")
      (value "NPN")
      (footprint "eagle-import:SOT323")
      (fields (field (name "PARTNO") "BC846BW_NPN"))
      (libsource (lib "eagle-import") (part "BC846BW"))
    )
    (comp (ref "U73")
      (value "NPN")
      (footprint "eagle-import:SOT323")
      (fields (field (name "PARTNO") "BC846BW_NPN"))
      (libsource (lib "eagle-import") (part "BC846BW"))
    )
    (comp (ref "U74")
      (value "NPN")
      (footprint "eagle-import:SOT323")
      (fields (field (name "PARTNO") "BC846BW_NPN"))
      (libsource (lib "eagle-import") (part "BC846BW"))
    )
    (comp (ref "U75")
      (value "NPN")
      (footprint "eagle-import:SOT323")
      (fields (field (name "PARTNO") "BC846BW_NPN"))
      (libsource (lib "eagle-import") (part "BC846BW"))
    )
    (comp (ref "X1")
      (value "25MHz")
      (footprint "eagle-import:SMD_3225")
      (fields (field (name "PARTNO") "FA-238 25.0000MB-B3"))
      (libsource (lib "eagle-import") (part "XTAL_25_MHZ"))
    )
    (comp (ref "X2")
      (value "24MHz")
      (footprint "eagle-import:SMD_3225")
      (fields (field (name "PARTNO") "FA-238 24.0000MB-C3 "))
      (libsource (lib "eagle-import") (part "XTAL_24_MHZ"))
    )
    (comp (ref "X3")
      (value "32.768KHz")
      (footprint "eagle-import:SMD_X_2_PADS")
      (fields (field (name "PARTNO") "ABS07-32.768KHZ-T"))
      (libsource (lib "eagle-import") (part "XTAL_32.768KHZ"))
    )
  )
  (nets
    (net (code "1") (name "A_A_DIR") (class "Default")
      (node (ref "R111") (pin "1") (pinfunction "1_1") (pintype "passive"))
      (node (ref "U3") (pin "73") (pinfunction "P9_5_73") (pintype "bidirectional"))
    )
    (net (code "2") (name "A_A_ENABLE") (class "Default")
      (node (ref "R112") (pin "1") (pinfunction "1_1") (pintype "passive"))
      (node (ref "U3") (pin "72") (pinfunction "P9_6_72") (pintype "bidirectional"))
    )
    (net (code "3") (name "A_A_HLFB_OUT") (class "Default")
      (node (ref "J25") (pin "5") (pinfunction "5-HLFB-_5") (pintype "passive"))
    )
    (net (code "4") (name "A_A_MI_DIR") (class "Default")
      (node (ref "J25") (pin "7") (pinfunction "7-INPUT_A-_7") (pintype "passive"))
      (node (ref "R113") (pin "1") (pinfunction "1_1") (pintype "passive"))
      (node (ref "U47") (pin "3") (pinfunction "C(3)_3") (pintype "input"))
    )
    (net (code "5") (name "A_A_MI_ENABLE") (class "Default")
      (node (ref "J25") (pin "8") (pinfunction "8-ENABLE-_8") (pintype "passive"))
      (node (ref "R114") (pin "1") (pinfunction "1_1") (pintype "passive"))
      (node (ref "U48") (pin "3") (pinfunction "C(3)_3") (pintype "input"))
    )
    (net (code "6") (name "A_A_MI_STEP") (class "Default")
      (node (ref "J25") (pin "6") (pinfunction "6-INPUT_B-_6") (pintype "passive"))
      (node (ref "R109") (pin "1") (pinfunction "1_1") (pintype "passive"))
      (node (ref "U46") (pin "3") (pinfunction "C(3)_3") (pintype "input"))
    )
    (net (code "7") (name "A_A_STEP") (class "Default")
      (node (ref "R110") (pin "1") (pinfunction "1_1") (pintype "passive"))
      (node (ref "U3") (pin "74") (pinfunction "P3_12_74") (pintype "bidirectional"))
    )
    (net (code "8") (name "A_B_DIR") (class "Default")
      (node (ref "R117") (pin "1") (pinfunction "1_1") (pintype "passive"))
      (node (ref "U3") (pin "76") (pinfunction "P3_10_76") (pintype "bidirectional"))
    )
    (net (code "9") (name "A_B_ENABLE") (class "Default")
      (node (ref "R118") (pin "1") (pinfunction "1_1") (pintype "passive"))
      (node (ref "U3") (pin "75") (pinfunction "P3_11_75") (pintype "bidirectional"))
    )
    (net (code "10") (name "A_B_HLFB_OUT") (class "Default")
      (node (ref "J26") (pin "5") (pinfunction "5-HLFB-_5") (pintype "passive"))
    )
    (net (code "11") (name "A_B_MI_DIR") (class "Default")
      (node (ref "J26") (pin "7") (pinfunction "7-INPUT_A-_7") (pintype "passive"))
      (node (ref "R119") (pin "1") (pinfunction "1_1") (pintype "passive"))
      (node (ref "U50") (pin "3") (pinfunction "C(3)_3") (pintype "input"))
    )
    (net (code "12") (name "A_B_MI_ENABLE") (class "Default")
      (node (ref "J26") (pin "8") (pinfunction "8-ENABLE-_8") (pintype "passive"))
      (node (ref "R120") (pin "1") (pinfunction "1_1") (pintype "passive"))
      (node (ref "U51") (pin "3") (pinfunction "C(3)_3") (pintype "input"))
    )
    (net (code "13") (name "A_B_MI_STEP") (class "Default")
      (node (ref "J26") (pin "6") (pinfunction "6-INPUT_B-_6") (pintype "passive"))
      (node (ref "R115") (pin "1") (pinfunction "1_1") (pintype "passive"))
      (node (ref "U49") (pin "3") (pinfunction "C(3)_3") (pintype "input"))
    )
    (net (code "14") (name "A_B_STEP") (class "Default")
      (node (ref "R116") (pin "1") (pinfunction "1_1") (pintype "passive"))
      (node (ref "U3") (pin "77") (pinfunction "P3_9_77") (pintype "bidirectional"))
    )
    (net (code "15") (name "B_MI_DIR") (class "Default")
      (node (ref "J34") (pin "7") (pinfunction "7-INPUT_A-_7") (pintype "passive"))
      (node (ref "R167") (pin "1") (pinfunction "1_1") (pintype "passive"))
      (node (ref "U74") (pin "3") (pinfunction "C(3)_3") (pintype "input"))
    )
    (net (code "16") (name "C58") (class "Default")
      (node (ref "C12") (pin "P$1") (pinfunction "1_P$1") (pintype "passive"))
      (node (ref "RJ1") (pin "4") (pinfunction "CT1_4") (pintype "bidirectional"))
    )
    (net (code "17") (name "C60") (class "Default")
      (node (ref "C13") (pin "P$1") (pinfunction "1_P$1") (pintype "passive"))
      (node (ref "RJ1") (pin "5") (pinfunction "CT2_5") (pintype "bidirectional"))
    )
    (net (code "18") (name "CRS_DV") (class "Default")
      (node (ref "R12") (pin "P$2") (pinfunction "2_P$2") (pintype "passive"))
      (node (ref "U1") (pin "15") (pinfunction "CRS_DV/PHYAD[1:0]_15") (pintype "bidirectional"))
    )
    (net (code "19") (name "C_A_DIR") (class "Default")
      (node (ref "R135") (pin "1") (pinfunction "1_1") (pintype "passive"))
      (node (ref "U3") (pin "58") (pinfunction "P9_0_58") (pintype "bidirectional"))
    )
    (net (code "20") (name "C_A_ENABLE") (class "Default")
      (node (ref "R136") (pin "1") (pinfunction "1_1") (pintype "passive"))
      (node (ref "U3") (pin "57") (pinfunction "P3_15_57") (pintype "bidirectional"))
    )
    (net (code "21") (name "C_A_HLFB_OUT") (class "Default")
      (node (ref "J29") (pin "5") (pinfunction "5-HLFB-_5") (pintype "passive"))
    )
    (net (code "22") (name "C_A_MI_DIR") (class "Default")
      (node (ref "J29") (pin "7") (pinfunction "7-INPUT_A-_7") (pintype "passive"))
      (node (ref "R137") (pin "1") (pinfunction "1_1") (pintype "passive"))
      (node (ref "U59") (pin "3") (pinfunction "C(3)_3") (pintype "input"))
    )
    (net (code "23") (name "C_A_MI_ENABLE") (class "Default")
      (node (ref "J29") (pin "8") (pinfunction "8-ENABLE-_8") (pintype "passive"))
      (node (ref "R138") (pin "1") (pinfunction "1_1") (pintype "passive"))
      (node (ref "U60") (pin "3") (pinfunction "C(3)_3") (pintype "input"))
    )
    (net (code "24") (name "C_A_MI_STEP") (class "Default")
      (node (ref "J29") (pin "6") (pinfunction "6-INPUT_B-_6") (pintype "passive"))
      (node (ref "R133") (pin "1") (pinfunction "1_1") (pintype "passive"))
      (node (ref "U58") (pin "3") (pinfunction "C(3)_3") (pintype "input"))
    )
    (net (code "25") (name "C_A_STEP") (class "Default")
      (node (ref "R134") (pin "1") (pinfunction "1_1") (pintype "passive"))
      (node (ref "U3") (pin "59") (pinfunction "P9_1_59") (pintype "bidirectional"))
    )
    (net (code "26") (name "C_B_DIR") (class "Default")
      (node (ref "R141") (pin "1") (pinfunction "1_1") (pintype "passive"))
      (node (ref "U3") (pin "70") (pinfunction "P9_8_70") (pintype "bidirectional"))
    )
    (net (code "27") (name "C_B_ENABLE") (class "Default")
      (node (ref "R142") (pin "1") (pinfunction "1_1") (pintype "passive"))
      (node (ref "U3") (pin "68") (pinfunction "P2_1/MD_68") (pintype "bidirectional"))
    )
    (net (code "28") (name "C_B_HLFB_OUT") (class "Default")
      (node (ref "J30") (pin "5") (pinfunction "5-HLFB-_5") (pintype "passive"))
    )
    (net (code "29") (name "C_B_MI_DIR") (class "Default")
      (node (ref "J30") (pin "7") (pinfunction "7-INPUT_A-_7") (pintype "passive"))
      (node (ref "R143") (pin "1") (pinfunction "1_1") (pintype "passive"))
      (node (ref "U62") (pin "3") (pinfunction "C(3)_3") (pintype "input"))
    )
    (net (code "30") (name "C_B_MI_ENABLE") (class "Default")
      (node (ref "J30") (pin "8") (pinfunction "8-ENABLE-_8") (pintype "passive"))
      (node (ref "R144") (pin "1") (pinfunction "1_1") (pintype "passive"))
      (node (ref "U63") (pin "3") (pinfunction "C(3)_3") (pintype "input"))
    )
    (net (code "31") (name "C_B_MI_STEP") (class "Default")
      (node (ref "J30") (pin "6") (pinfunction "6-INPUT_B-_6") (pintype "passive"))
      (node (ref "R139") (pin "1") (pinfunction "1_1") (pintype "passive"))
      (node (ref "U61") (pin "3") (pinfunction "C(3)_3") (pintype "input"))
    )
    (net (code "32") (name "C_B_STEP") (class "Default")
      (node (ref "R140") (pin "1") (pinfunction "1_1") (pintype "passive"))
      (node (ref "U3") (pin "71") (pinfunction "P9_7_71") (pintype "bidirectional"))
    )
    (net (code "33") (name "ESTOP") (class "Default")
      (node (ref "R79") (pin "P$2") (pinfunction "2_P$2") (pintype "passive"))
      (node (ref "R80") (pin "P$2") (pinfunction "2_P$2") (pintype "passive"))
      (node (ref "U21") (pin "2") (pinfunction "E(1)_2") (pintype "output"))
      (node (ref "U3") (pin "69") (pinfunction "P2_0(INPUT_ONLY)_69") (pintype "bidirectional"))
    )
    (net (code "34") (name "ESTOP_RET") (class "Default")
      (node (ref "J9") (pin "P$1") (pinfunction "P$1_P$1") (pintype "bidirectional"))
      (node (ref "R78") (pin "P$1") (pinfunction "1_P$1") (pintype "passive"))
    )
    (net (code "35") (name "ETH") (class "Default")
      (node (ref "U1") (pin "16") (pinfunction "REF_CLK_16") (pintype "bidirectional"))
      (node (ref "U3") (pin "9") (pinfunction "P7_1_9") (pintype "bidirectional"))
    )
    (net (code "36") (name "ETH_CRS_DV") (class "Default")
      (node (ref "R12") (pin "P$1") (pinfunction "1_P$1") (pintype "passive"))
      (node (ref "U3") (pin "13") (pinfunction "P7_5_13") (pintype "bidirectional"))
    )
    (net (code "37") (name "ETH_IRQ14") (class "Default")
      (node (ref "R2") (pin "P$1") (pinfunction "1_P$1") (pintype "passive"))
      (node (ref "U1") (pin "18") (pinfunction "INTRP_18") (pintype "bidirectional"))
      (node (ref "U3") (pin "159") (pinfunction "P0_10/AN103_159") (pintype "bidirectional"))
    )
    (net (code "38") (name "ETH_MDC") (class "Default")
      (node (ref "R4") (pin "P$1") (pinfunction "1_P$1") (pintype "passive"))
      (node (ref "U1") (pin "11") (pinfunction "MDC_11") (pintype "input"))
      (node (ref "U3") (pin "4") (pinfunction "P4_3_4") (pintype "bidirectional"))
    )
    (net (code "39") (name "ETH_MDIO") (class "Default")
      (node (ref "R6") (pin "P$1") (pinfunction "1_P$1") (pintype "passive"))
      (node (ref "U1") (pin "10") (pinfunction "MDIO_10") (pintype "bidirectional"))
      (node (ref "U3") (pin "5") (pinfunction "P4_4_5") (pintype "bidirectional"))
    )
    (net (code "40") (name "ETH_RESET") (class "Default")
      (node (ref "C6") (pin "P$1") (pinfunction "1_P$1") (pintype "passive"))
      (node (ref "R3") (pin "P$1") (pinfunction "1_P$1") (pintype "passive"))
      (node (ref "U1") (pin "24") (pinfunction "~{RST}_24") (pintype "input"))
      (node (ref "U3") (pin "172") (pinfunction "P8_6_172") (pintype "bidirectional"))
    )
    (net (code "41") (name "ETH_RXD0") (class "Default")
      (node (ref "R10") (pin "P$1") (pinfunction "1_P$1") (pintype "passive"))
      (node (ref "U3") (pin "10") (pinfunction "P7_2_10") (pintype "bidirectional"))
    )
    (net (code "42") (name "ETH_RXD1") (class "Default")
      (node (ref "R9") (pin "P$1") (pinfunction "1_P$1") (pintype "passive"))
      (node (ref "U3") (pin "11") (pinfunction "P7_3_11") (pintype "bidirectional"))
    )
    (net (code "43") (name "ETH_RX_ER") (class "Default")
      (node (ref "R11") (pin "P$1") (pinfunction "1_P$1") (pintype "passive"))
      (node (ref "U3") (pin "12") (pinfunction "P7_4_12") (pintype "bidirectional"))
    )
    (net (code "44") (name "ETH_TXD0") (class "Default")
      (node (ref "U1") (pin "20") (pinfunction "TXD0_20") (pintype "input"))
      (node (ref "U3") (pin "8") (pinfunction "P7_0_8") (pintype "bidirectional"))
    )
    (net (code "45") (name "ETH_TXD1") (class "Default")
      (node (ref "U1") (pin "21") (pinfunction "TXD1_21") (pintype "bidirectional"))
      (node (ref "U3") (pin "7") (pinfunction "P4_6_7") (pintype "bidirectional"))
    )
    (net (code "46") (name "ETH_TXD_EN") (class "Default")
      (node (ref "U1") (pin "19") (pinfunction "TXEN_19") (pintype "input"))
      (node (ref "U3") (pin "6") (pinfunction "P4_5_6") (pintype "bidirectional"))
    )
    (net (code "47") (name "GND") (class "Default")
      (node (ref "C1") (pin "P$2") (pinfunction "2_P$2") (pintype "passive"))
      (node (ref "C10") (pin "P$2") (pinfunction "2_P$2") (pintype "passive"))
      (node (ref "C11") (pin "P$2") (pinfunction "2_P$2") (pintype "passive"))
      (node (ref "C12") (pin "P$2") (pinfunction "2_P$2") (pintype "passive"))
      (node (ref "C13") (pin "P$2") (pinfunction "2_P$2") (pintype "passive"))
      (node (ref "C14") (pin "P$2") (pinfunction "2_P$2") (pintype "passive"))
      (node (ref "C15") (pin "P$2") (pinfunction "2_P$2") (pintype "passive"))
      (node (ref "C16") (pin "P$2") (pinfunction "2_P$2") (pintype "passive"))
      (node (ref "C17") (pin "P$2") (pinfunction "2_P$2") (pintype "passive"))
      (node (ref "C18") (pin "P$2") (pinfunction "2_P$2") (pintype "passive"))
      (node (ref "C19") (pin "P$1") (pinfunction "1_P$1") (pintype "passive"))
      (node (ref "C2") (pin "P$2") (pinfunction "2_P$2") (pintype "passive"))
      (node (ref "C20") (pin "P$1") (pinfunction "1_P$1") (pintype "passive"))
      (node (ref "C21") (pin "P$1") (pinfunction "1_P$1") (pintype "passive"))
      (node (ref "C22") (pin "P$1") (pinfunction "1_P$1") (pintype "passive"))
      (node (ref "C23") (pin "P$2") (pinfunction "2_P$2") (pintype "passive"))
      (node (ref "C24") (pin "P$1") (pinfunction "1_P$1") (pintype "passive"))
      (node (ref "C25") (pin "P$1") (pinfunction "1_P$1") (pintype "passive"))
      (node (ref "C26") (pin "P$2") (pinfunction "2_P$2") (pintype "passive"))
      (node (ref "C27") (pin "P$1") (pinfunction "1_P$1") (pintype "passive"))
      (node (ref "C28") (pin "P$2") (pinfunction "2_P$2") (pintype "passive"))
      (node (ref "C29") (pin "P$2") (pinfunction "2_P$2") (pintype "passive"))
      (node (ref "C3") (pin "P$2") (pinfunction "2_P$2") (pintype "passive"))
      (node (ref "C30") (pin "P$1") (pinfunction "1_P$1") (pintype "passive"))
      (node (ref "C31") (pin "2") (pinfunction "2_2") (pintype "passive"))
      (node (ref "C32") (pin "P$2") (pinfunction "2_P$2") (pintype "passive"))
      (node (ref "C33") (pin "P$2") (pinfunction "2_P$2") (pintype "passive"))
      (node (ref "C34") (pin "P$1") (pinfunction "1_P$1") (pintype "passive"))
      (node (ref "C35") (pin "P$1") (pinfunction "1_P$1") (pintype "passive"))
      (node (ref "C36") (pin "P$2") (pinfunction "2_P$2") (pintype "passive"))
      (node (ref "C37") (pin "P$2") (pinfunction "2_P$2") (pintype "passive"))
      (node (ref "C38") (pin "P$1") (pinfunction "1_P$1") (pintype "passive"))
      (node (ref "C39") (pin "P$2") (pinfunction "2_P$2") (pintype "passive"))
      (node (ref "C4") (pin "P$2") (pinfunction "2_P$2") (pintype "passive"))
      (node (ref "C40") (pin "P$2") (pinfunction "2_P$2") (pintype "passive"))
      (node (ref "C41") (pin "P$2") (pinfunction "2_P$2") (pintype "passive"))
      (node (ref "C42") (pin "P$2") (pinfunction "2_P$2") (pintype "passive"))
      (node (ref "C43") (pin "P$1") (pinfunction "1_P$1") (pintype "passive"))
      (node (ref "C5") (pin "P$2") (pinfunction "2_P$2") (pintype "passive"))
      (node (ref "C6") (pin "P$2") (pinfunction "2_P$2") (pintype "passive"))
      (node (ref "C7") (pin "P$2") (pinfunction "2_P$2") (pintype "passive"))
      (node (ref "C8") (pin "P$2") (pinfunction "2_P$2") (pintype "passive"))
      (node (ref "C9") (pin "P$2") (pinfunction "2_P$2") (pintype "passive"))
      (node (ref "J1") (pin "6") (pinfunction "SUPPLY_VOLTAGE_GROUND_6") (pintype "power_in"))
      (node (ref "J2") (pin "P$1") (pinfunction "P$1_P$1") (pintype "bidirectional"))
      (node (ref "J3") (pin "10") (pinfunction "10_10") (pintype "passive"))
      (node (ref "J3") (pin "6") (pinfunction "6_6") (pintype "passive"))
      (node (ref "J3") (pin "8") (pinfunction "8_8") (pintype "passive"))
      (node (ref "J39") (pin "P$1") (pinfunction "P$1_P$1") (pintype "bidirectional"))
      (node (ref "J39") (pin "P$11") (pinfunction "P$11_P$11") (pintype "bidirectional"))
      (node (ref "J39") (pin "P$13") (pinfunction "P$13_P$13") (pintype "bidirectional"))
      (node (ref "J39") (pin "P$15") (pinfunction "P$15_P$15") (pintype "bidirectional"))
      (node (ref "J39") (pin "P$17") (pinfunction "P$17_P$17") (pintype "bidirectional"))
      (node (ref "J39") (pin "P$19") (pinfunction "P$19_P$19") (pintype "bidirectional"))
      (node (ref "J39") (pin "P$3") (pinfunction "P$3_P$3") (pintype "bidirectional"))
      (node (ref "J39") (pin "P$5") (pinfunction "P$5_P$5") (pintype "bidirectional"))
      (node (ref "J39") (pin "P$7") (pinfunction "P$7_P$7") (pintype "bidirectional"))
      (node (ref "J39") (pin "P$9") (pinfunction "P$9_P$9") (pintype "bidirectional"))
      (node (ref "J6") (pin "GND") (pinfunction "GND_GND") (pintype "power_in"))
      (node (ref "J7") (pin "P$5") (pinfunction "GND_P$5") (pintype "bidirectional"))
      (node (ref "LED1") (pin "2") (pinfunction "C_2") (pintype "passive"))
      (node (ref "LED10") (pin "2") (pinfunction "C_2") (pintype "passive"))
      (node (ref "LED11") (pin "2") (pinfunction "C_2") (pintype "passive"))
      (node (ref "LED12") (pin "2") (pinfunction "C_2") (pintype "passive"))
      (node (ref "LED13") (pin "2") (pinfunction "C_2") (pintype "passive"))
      (node (ref "LED14") (pin "2") (pinfunction "C_2") (pintype "passive"))
      (node (ref "LED15") (pin "2") (pinfunction "C_2") (pintype "passive"))
      (node (ref "LED16") (pin "2") (pinfunction "C_2") (pintype "passive"))
      (node (ref "LED3") (pin "2") (pinfunction "C_2") (pintype "passive"))
      (node (ref "LED6") (pin "2") (pinfunction "C_2") (pintype "passive"))
      (node (ref "LED7") (pin "2") (pinfunction "C_2") (pintype "passive"))
      (node (ref "R1") (pin "P$1") (pinfunction "1_P$1") (pintype "passive"))
      (node (ref "R101") (pin "P$1") (pinfunction "1_P$1") (pintype "passive"))
      (node (ref "R21") (pin "P$1") (pinfunction "1_P$1") (pintype "passive"))
      (node (ref "R22") (pin "P$1") (pinfunction "1_P$1") (pintype "passive"))
      (node (ref "R23") (pin "P$1") (pinfunction "1_P$1") (pintype "passive"))
      (node (ref "R24") (pin "P$1") (pinfunction "1_P$1") (pintype "passive"))
      (node (ref "R34") (pin "P$1") (pinfunction "1_P$1") (pintype "passive"))
      (node (ref "R53") (pin "P$1") (pinfunction "1_P$1") (pintype "passive"))
      (node (ref "R56") (pin "P$1") (pinfunction "1_P$1") (pintype "passive"))
      (node (ref "R59") (pin "P$1") (pinfunction "1_P$1") (pintype "passive"))
      (node (ref "R74") (pin "P$1") (pinfunction "1_P$1") (pintype "passive"))
      (node (ref "R77") (pin "P$1") (pinfunction "1_P$1") (pintype "passive"))
      (node (ref "R80") (pin "P$1") (pinfunction "1_P$1") (pintype "passive"))
      (node (ref "R83") (pin "P$1") (pinfunction "1_P$1") (pintype "passive"))
      (node (ref "R98") (pin "P$1") (pinfunction "1_P$1") (pintype "passive"))
      (node (ref "RJ1") (pin "10") (pinfunction "GLO_10") (pintype "bidirectional"))
      (node (ref "RJ1") (pin "8") (pinfunction "P8_8") (pintype "bidirectional"))
      (node (ref "U1") (pin "22") (pinfunction "GND_22") (pintype "power_in"))
      (node (ref "U1") (pin "25") (pinfunction "25_25") (pintype "passive"))
      (node (ref "U10") (pin "2") (pinfunction "E(1)_2") (pintype "output"))
      (node (ref "U11") (pin "2") (pinfunction "E(1)_2") (pintype "output"))
      (node (ref "U12") (pin "2") (pinfunction "E(1)_2") (pintype "output"))
      (node (ref "U13") (pin "2") (pinfunction "E(1)_2") (pintype "output"))
      (node (ref "U14") (pin "2") (pinfunction "E(1)_2") (pintype "output"))
      (node (ref "U15") (pin "2") (pinfunction "E(1)_2") (pintype "output"))
      (node (ref "U16") (pin "2") (pinfunction "E(1)_2") (pintype "output"))
      (node (ref "U17") (pin "2") (pinfunction "E(1)_2") (pintype "output"))
      (node (ref "U2") (pin "2") (pinfunction "GND_2") (pintype "input"))
      (node (ref "U22") (pin "2") (pinfunction "E(1)_2") (pintype "output"))
      (node (ref "U23") (pin "2") (pinfunction "E(1)_2") (pintype "output"))
      (node (ref "U24") (pin "2") (pinfunction "E(1)_2") (pintype "output"))
      (node (ref "U25") (pin "2") (pinfunction "E(1)_2") (pintype "output"))
      (node (ref "U26") (pin "2") (pinfunction "E(1)_2") (pintype "output"))
      (node (ref "U27") (pin "2") (pinfunction "E(1)_2") (pintype "output"))
      (node (ref "U3") (pin "111") (pinfunction "VSS(IO)5_111") (pintype "bidirectional"))
      (node (ref "U3") (pin "124") (pinfunction "VSS(IO)6_124") (pintype "bidirectional"))
      (node (ref "U3") (pin "139") (pinfunction "VSS(IO)7_139") (pintype "bidirectional"))
      (node (ref "U3") (pin "150") (pinfunction "VSS(IO)8_150") (pintype "bidirectional"))
      (node (ref "U3") (pin "153") (pinfunction "VREFL_153") (pintype "bidirectional"))
      (node (ref "U3") (pin "156") (pinfunction "AVSS0_156") (pintype "bidirectional"))
      (node (ref "U3") (pin "157") (pinfunction "VREFL0_157") (pintype "bidirectional"))
      (node (ref "U3") (pin "170") (pinfunction "VSS(IO)9_170") (pintype "bidirectional"))
      (node (ref "U3") (pin "22") (pinfunction "VSS1_22") (pintype "bidirectional"))
      (node (ref "U3") (pin "28") (pinfunction "AVSS_USBHS_28") (pintype "bidirectional"))
      (node (ref "U3") (pin "29") (pinfunction "PVSS_USBHS_29") (pintype "bidirectional"))
      (node (ref "U3") (pin "30") (pinfunction "VSS2_USBHS_30") (pintype "bidirectional"))
      (node (ref "U3") (pin "33") (pinfunction "VSS1_USBHS_33") (pintype "bidirectional"))
      (node (ref "U3") (pin "35") (pinfunction "VSSIO_35") (pintype "bidirectional"))
      (node (ref "U3") (pin "45") (pinfunction "VSS_USB_45") (pintype "bidirectional"))
      (node (ref "U3") (pin "60") (pinfunction "VSS(IO)2_60") (pintype "bidirectional"))
      (node (ref "U3") (pin "63") (pinfunction "VSS(IO/DCDC)_63") (pintype "bidirectional"))
      (node (ref "U3") (pin "66") (pinfunction "VCC_DCDC(IO/DCDC)_66") (pintype "bidirectional"))
      (node (ref "U3") (pin "83") (pinfunction "VSS(IO)3_83") (pintype "bidirectional"))
      (node (ref "U3") (pin "98") (pinfunction "VSS(IO)4_98") (pintype "bidirectional"))
      (node (ref "U34") (pin "2") (pinfunction "E(1)_2") (pintype "output"))
      (node (ref "U35") (pin "2") (pinfunction "E(1)_2") (pintype "output"))
      (node (ref "U36") (pin "2") (pinfunction "E(1)_2") (pintype "output"))
      (node (ref "U37") (pin "2") (pinfunction "E(1)_2") (pintype "output"))
      (node (ref "U38") (pin "2") (pinfunction "E(1)_2") (pintype "output"))
      (node (ref "U39") (pin "2") (pinfunction "E(1)_2") (pintype "output"))
      (node (ref "U46") (pin "2") (pinfunction "E(1)_2") (pintype "output"))
      (node (ref "U47") (pin "2") (pinfunction "E(1)_2") (pintype "output"))
      (node (ref "U48") (pin "2") (pinfunction "E(1)_2") (pintype "output"))
      (node (ref "U49") (pin "2") (pinfunction "E(1)_2") (pintype "output"))
      (node (ref "U50") (pin "2") (pinfunction "E(1)_2") (pintype "output"))
      (node (ref "U51") (pin "2") (pinfunction "E(1)_2") (pintype "output"))
      (node (ref "U58") (pin "2") (pinfunction "E(1)_2") (pintype "output"))
      (node (ref "U59") (pin "2") (pinfunction "E(1)_2") (pintype "output"))
      (node (ref "U6") (pin "2") (pinfunction "E(1)_2") (pintype "output"))
      (node (ref "U60") (pin "2") (pinfunction "E(1)_2") (pintype "output"))
      (node (ref "U61") (pin "2") (pinfunction "E(1)_2") (pintype "output"))
      (node (ref "U62") (pin "2") (pinfunction "E(1)_2") (pintype "output"))
      (node (ref "U63") (pin "2") (pinfunction "E(1)_2") (pintype "output"))
      (node (ref "U7") (pin "2") (pinfunction "E(1)_2") (pintype "output"))
      (node (ref "U70") (pin "2") (pinfunction "E(1)_2") (pintype "output"))
      (node (ref "U71") (pin "2") (pinfunction "E(1)_2") (pintype "output"))
      (node (ref "U72") (pin "2") (pinfunction "E(1)_2") (pintype "output"))
      (node (ref "U73") (pin "2") (pinfunction "E(1)_2") (pintype "output"))
      (node (ref "U74") (pin "2") (pinfunction "E(1)_2") (pintype "output"))
      (node (ref "U75") (pin "2") (pinfunction "E(1)_2") (pintype "output"))
      (node (ref "X1") (pin "2") (pinfunction "2_2") (pintype "bidirectional"))
      (node (ref "X1") (pin "4") (pinfunction "4_4") (pintype "bidirectional"))
      (node (ref "X2") (pin "2") (pinfunction "2_2") (pintype "bidirectional"))
      (node (ref "X2") (pin "4") (pinfunction "4_4") (pintype "bidirectional"))
    )
    (net (code "48") (name "GNDE") (class "Default")
      (node (ref "J1") (pin "S1") (pinfunction "SHIELD_S1") (pintype "passive"))
      (node (ref "J1") (pin "S2") (pinfunction "SHIELD_S2") (pintype "passive"))
      (node (ref "J1") (pin "S3") (pinfunction "SHIELD_S3") (pintype "passive"))
      (node (ref "J1") (pin "S4") (pinfunction "SHIELD_S4") (pintype "passive"))
      (node (ref "J2") (pin "P$4") (pinfunction "P$4_P$4") (pintype "bidirectional"))
      (node (ref "J6") (pin "SHLD1") (pinfunction "SHIELD_1_SHLD1") (pintype "bidirectional"))
      (node (ref "J6") (pin "SHLD2") (pinfunction "SHIELD_2_SHLD2") (pintype "bidirectional"))
      (node (ref "J7") (pin "P$6") (pinfunction "SHIELD1_P$6") (pintype "bidirectional"))
      (node (ref "J7") (pin "P$7") (pinfunction "SHIELD2_P$7") (pintype "bidirectional"))
      (node (ref "J7") (pin "P$8") (pinfunction "SHIELD3_P$8") (pintype "bidirectional"))
      (node (ref "J7") (pin "P$9") (pinfunction "SHIELD4_P$9") (pintype "bidirectional"))
      (node (ref "RJ1") (pin "13") (pinfunction "GNDE0_13") (pintype "bidirectional"))
      (node (ref "RJ1") (pin "14") (pinfunction "GNDE1_14") (pintype "bidirectional"))
    )
    (net (code "49") (name "ID") (class "Default")
      (node (ref "J7") (pin "P$4") (pinfunction "ID_P$4") (pintype "bidirectional"))
    )
    (net (code "50") (name "IIC_1_SCL") (class "Default")
      (node (ref "J8") (pin "P$8") (pinfunction "P$8_P$8") (pintype "bidirectional"))
      (node (ref "R14") (pin "P$2") (pinfunction "2_P$2") (pintype "passive"))
      (node (ref "U3") (pin "132") (pinfunction "P1_0_132") (pintype "bidirectional"))
    )
    (net (code "51") (name "IIC_1_SDA") (class "Default")
      (node (ref "J8") (pin "P$7") (pinfunction "P$7_P$7") (pintype "bidirectional"))
      (node (ref "R15") (pin "P$2") (pinfunction "2_P$2") (pintype "passive"))
      (node (ref "U3") (pin "131") (pinfunction "P1_1_131") (pintype "bidirectional"))
    )
    (net (code "52") (name "LED1{slash}SPEED") (class "Default")
      (node (ref "RJ1") (pin "11") (pinfunction "YLO_11") (pintype "bidirectional"))
      (node (ref "U1") (pin "23") (pinfunction "LED0/ANEN_SPEED_23") (pintype "bidirectional"))
    )
    (net (code "53") (name "LS_01") (class "Default")
      (node (ref "R33") (pin "P$2") (pinfunction "2_P$2") (pintype "passive"))
      (node (ref "R34") (pin "P$2") (pinfunction "2_P$2") (pintype "passive"))
      (node (ref "U3") (pin "50") (pinfunction "P2_6_50") (pintype "bidirectional"))
      (node (ref "U5") (pin "2") (pinfunction "E(1)_2") (pintype "output"))
    )
    (net (code "54") (name "LS_01_RET") (class "Default")
      (node (ref "J11") (pin "P$1") (pinfunction "P$1_P$1") (pintype "bidirectional"))
      (node (ref "R28") (pin "P$1") (pinfunction "1_P$1") (pintype "passive"))
    )
    (net (code "55") (name "LS_02") (class "Default")
      (node (ref "R36") (pin "P$2") (pinfunction "2_P$2") (pintype "passive"))
      (node (ref "R53") (pin "P$2") (pinfunction "2_P$2") (pintype "passive"))
      (node (ref "U3") (pin "51") (pinfunction "P2_5_51") (pintype "bidirectional"))
      (node (ref "U8") (pin "2") (pinfunction "E(1)_2") (pintype "output"))
    )
    (net (code "56") (name "LS_02_RET") (class "Default")
      (node (ref "J12") (pin "P$1") (pinfunction "P$1_P$1") (pintype "bidirectional"))
      (node (ref "R35") (pin "P$1") (pinfunction "1_P$1") (pintype "passive"))
    )
    (net (code "57") (name "LS_03") (class "Default")
      (node (ref "R55") (pin "P$2") (pinfunction "2_P$2") (pintype "passive"))
      (node (ref "R56") (pin "P$2") (pinfunction "2_P$2") (pintype "passive"))
      (node (ref "U3") (pin "53") (pinfunction "P2_3_53") (pintype "bidirectional"))
      (node (ref "U9") (pin "2") (pinfunction "E(1)_2") (pintype "output"))
    )
    (net (code "58") (name "LS_03_RET") (class "Default")
      (node (ref "J19") (pin "P$1") (pinfunction "P$1_P$1") (pintype "bidirectional"))
      (node (ref "R54") (pin "P$1") (pinfunction "1_P$1") (pintype "passive"))
    )
    (net (code "59") (name "LS_04") (class "Default")
      (node (ref "R73") (pin "P$2") (pinfunction "2_P$2") (pintype "passive"))
      (node (ref "R74") (pin "P$2") (pinfunction "2_P$2") (pintype "passive"))
      (node (ref "U19") (pin "2") (pinfunction "E(1)_2") (pintype "output"))
      (node (ref "U3") (pin "54") (pinfunction "P2_2_54") (pintype "bidirectional"))
    )
    (net (code "60") (name "LS_04_RET") (class "Default")
      (node (ref "J20") (pin "P$1") (pinfunction "P$1_P$1") (pintype "bidirectional"))
      (node (ref "R60") (pin "P$1") (pinfunction "1_P$1") (pintype "passive"))
    )
    (net (code "61") (name "LS_05") (class "Default")
      (node (ref "R58") (pin "P$2") (pinfunction "2_P$2") (pintype "passive"))
      (node (ref "R59") (pin "P$2") (pinfunction "2_P$2") (pintype "passive"))
      (node (ref "U18") (pin "2") (pinfunction "E(1)_2") (pintype "output"))
      (node (ref "U3") (pin "81") (pinfunction "P3_5_81") (pintype "bidirectional"))
    )
    (net (code "62") (name "LS_05_RET") (class "Default")
      (node (ref "J27") (pin "P$1") (pinfunction "P$1_P$1") (pintype "bidirectional"))
      (node (ref "R57") (pin "P$1") (pinfunction "1_P$1") (pintype "passive"))
    )
    (net (code "63") (name "LS_06") (class "Default")
      (node (ref "R76") (pin "P$2") (pinfunction "2_P$2") (pintype "passive"))
      (node (ref "R77") (pin "P$2") (pinfunction "2_P$2") (pintype "passive"))
      (node (ref "U20") (pin "2") (pinfunction "E(1)_2") (pintype "output"))
      (node (ref "U3") (pin "82") (pinfunction "P3_4_82") (pintype "bidirectional"))
    )
    (net (code "64") (name "LS_06_RET") (class "Default")
      (node (ref "J28") (pin "P$1") (pinfunction "P$1_P$1") (pintype "bidirectional"))
      (node (ref "R75") (pin "P$1") (pinfunction "1_P$1") (pintype "passive"))
    )
    (net (code "65") (name "LS_07") (class "Default")
      (node (ref "R97") (pin "P$2") (pinfunction "2_P$2") (pintype "passive"))
      (node (ref "R98") (pin "P$2") (pinfunction "2_P$2") (pintype "passive"))
      (node (ref "U29") (pin "2") (pinfunction "E(1)_2") (pintype "output"))
      (node (ref "U3") (pin "86") (pinfunction "P3_2_86") (pintype "bidirectional"))
    )
    (net (code "66") (name "LS_07_RET") (class "Default")
      (node (ref "J31") (pin "P$1") (pinfunction "P$1_P$1") (pintype "bidirectional"))
      (node (ref "R84") (pin "P$1") (pinfunction "1_P$1") (pintype "passive"))
    )
    (net (code "67") (name "LS_08") (class "Default")
      (node (ref "R82") (pin "P$2") (pinfunction "2_P$2") (pintype "passive"))
      (node (ref "R83") (pin "P$2") (pinfunction "2_P$2") (pintype "passive"))
      (node (ref "U28") (pin "2") (pinfunction "E(1)_2") (pintype "output"))
      (node (ref "U3") (pin "87") (pinfunction "P3_1_87") (pintype "bidirectional"))
    )
    (net (code "68") (name "LS_08_RET") (class "Default")
      (node (ref "P1") (pin "P$1") (pinfunction "P$1_P$1") (pintype "bidirectional"))
      (node (ref "R81") (pin "P$1") (pinfunction "1_P$1") (pintype "passive"))
    )
    (net (code "69") (name "LS_09") (class "Default")
      (node (ref "R100") (pin "P$2") (pinfunction "2_P$2") (pintype "passive"))
      (node (ref "R101") (pin "P$2") (pinfunction "2_P$2") (pintype "passive"))
      (node (ref "U3") (pin "92") (pinfunction "P1_11_92") (pintype "bidirectional"))
      (node (ref "U30") (pin "2") (pinfunction "E(1)_2") (pintype "output"))
    )
    (net (code "70") (name "LS_09_RET") (class "Default")
      (node (ref "P3") (pin "P$1") (pinfunction "P$1_P$1") (pintype "bidirectional"))
      (node (ref "R99") (pin "P$1") (pinfunction "1_P$1") (pintype "passive"))
    )
    (net (code "71") (name "N$88") (class "Default")
      (node (ref "J8") (pin "P$20") (pinfunction "P$20_P$20") (pintype "bidirectional"))
    )
    (net (code "72") (name "N$89") (class "Default")
      (node (ref "J8") (pin "P$18") (pinfunction "P$18_P$18") (pintype "bidirectional"))
    )
    (net (code "73") (name "N$90") (class "Default")
      (node (ref "J8") (pin "P$16") (pinfunction "P$16_P$16") (pintype "bidirectional"))
    )
    (net (code "74") (name "N$91") (class "Default")
      (node (ref "J8") (pin "P$14") (pinfunction "P$14_P$14") (pintype "bidirectional"))
    )
    (net (code "75") (name "N$92") (class "Default")
      (node (ref "J8") (pin "P$12") (pinfunction "P$12_P$12") (pintype "bidirectional"))
    )
    (net (code "76") (name "NC") (class "Default")
      (node (ref "J8") (pin "P$6") (pinfunction "P$6_P$6") (pintype "bidirectional"))
      (node (ref "RJ1") (pin "7") (pinfunction "P7_7") (pintype "bidirectional"))
      (node (ref "U3") (pin "79") (pinfunction "P3_7_79") (pintype "bidirectional"))
      (node (ref "U3") (pin "80") (pinfunction "P3_6_80") (pintype "bidirectional"))
      (node (ref "U3") (pin "85") (pinfunction "P3_3_85") (pintype "bidirectional"))
    )
    (net (code "77") (name "Net-(C8-1)") (class "Default")
      (node (ref "C8") (pin "P$1") (pinfunction "1_P$1") (pintype "passive"))
      (node (ref "C9") (pin "P$1") (pinfunction "1_P$1") (pintype "passive"))
      (node (ref "FB1") (pin "2") (pinfunction "P$2_2") (pintype "bidirectional"))
      (node (ref "U1") (pin "2") (pinfunction "VDDA_3.3_2") (pintype "power_in"))
    )
    (net (code "78") (name "Net-(C24-2)") (class "Default")
      (node (ref "C24") (pin "P$2") (pinfunction "2_P$2") (pintype "passive"))
      (node (ref "U3") (pin "148") (pinfunction "VCL2_148") (pintype "bidirectional"))
    )
    (net (code "79") (name "Net-(C28-1)") (class "Default")
      (node (ref "C28") (pin "P$1") (pinfunction "1_P$1") (pintype "passive"))
      (node (ref "J7") (pin "P$1") (pinfunction "VBUS_P$1") (pintype "bidirectional"))
      (node (ref "R16") (pin "P$2") (pinfunction "2_P$2") (pintype "passive"))
      (node (ref "R21") (pin "P$2") (pinfunction "2_P$2") (pintype "passive"))
    )
    (net (code "80") (name "Net-(C33-1)") (class "Default")
      (node (ref "C33") (pin "P$1") (pinfunction "1_P$1") (pintype "passive"))
      (node (ref "U3") (pin "19") (pinfunction "VCLO_19") (pintype "bidirectional"))
    )
    (net (code "81") (name "Net-(C42-1)") (class "Default")
      (node (ref "C42") (pin "P$1") (pinfunction "1_P$1") (pintype "passive"))
      (node (ref "U3") (pin "62") (pinfunction "VCL1_62") (pintype "bidirectional"))
    )
    (net (code "82") (name "Net-(J7-D+)") (class "Default")
      (node (ref "J7") (pin "P$3") (pinfunction "D+_P$3") (pintype "bidirectional"))
      (node (ref "R18") (pin "P$2") (pinfunction "2_P$2") (pintype "passive"))
    )
    (net (code "83") (name "Net-(J7-D-)") (class "Default")
      (node (ref "J7") (pin "P$2") (pinfunction "D-_P$2") (pintype "bidirectional"))
      (node (ref "R17") (pin "P$2") (pinfunction "2_P$2") (pintype "passive"))
    )
    (net (code "84") (name "Net-(LED1-A)") (class "Default")
      (node (ref "LED1") (pin "1") (pinfunction "A_1") (pintype "passive"))
      (node (ref "R5") (pin "P$1") (pinfunction "1_P$1") (pintype "passive"))
    )
    (net (code "85") (name "Net-(LED3-A)") (class "Default")
      (node (ref "LED3") (pin "1") (pinfunction "A_1") (pintype "passive"))
      (node (ref "R33") (pin "P$1") (pinfunction "1_P$1") (pintype "passive"))
    )
    (net (code "86") (name "Net-(LED4-A)") (class "Default")
      (node (ref "LED4") (pin "1") (pinfunction "A_1") (pintype "passive"))
      (node (ref "R32") (pin "P$1") (pinfunction "1_P$1") (pintype "passive"))
    )
    (net (code "87") (name "Net-(LED4-C)") (class "Default")
      (node (ref "LED4") (pin "2") (pinfunction "C_2") (pintype "passive"))
      (node (ref "U$1") (pin "P$1") (pinfunction "VC-_P$1") (pintype "bidirectional"))
      (node (ref "U6") (pin "3") (pinfunction "C(3)_3") (pintype "input"))
    )
    (net (code "88") (name "Net-(LED5-A)") (class "Default")
      (node (ref "LED5") (pin "1") (pinfunction "A_1") (pintype "passive"))
      (node (ref "R31") (pin "P$1") (pinfunction "1_P$1") (pintype "passive"))
    )
    (net (code "89") (name "Net-(LED5-C)") (class "Default")
      (node (ref "LED5") (pin "2") (pinfunction "C_2") (pintype "passive"))
      (node (ref "U$2") (pin "P$1") (pinfunction "VC-_P$1") (pintype "bidirectional"))
      (node (ref "U7") (pin "3") (pinfunction "C(3)_3") (pintype "input"))
    )
    (net (code "90") (name "Net-(LED6-A)") (class "Default")
      (node (ref "LED6") (pin "1") (pinfunction "A_1") (pintype "passive"))
      (node (ref "R36") (pin "P$1") (pinfunction "1_P$1") (pintype "passive"))
    )
    (net (code "91") (name "Net-(LED7-A)") (class "Default")
      (node (ref "LED7") (pin "1") (pinfunction "A_1") (pintype "passive"))
      (node (ref "R55") (pin "P$1") (pinfunction "1_P$1") (pintype "passive"))
    )
    (net (code "92") (name "Net-(LED8-A)") (class "Default")
      (node (ref "LED8") (pin "1") (pinfunction "A_1") (pintype "passive"))
      (node (ref "R52") (pin "P$1") (pinfunction "1_P$1") (pintype "passive"))
    )
    (net (code "93") (name "Net-(LED8-C)") (class "Default")
      (node (ref "LED8") (pin "2") (pinfunction "C_2") (pintype "passive"))
      (node (ref "U$7") (pin "P$1") (pinfunction "VC-_P$1") (pintype "bidirectional"))
      (node (ref "U16") (pin "3") (pinfunction "C(3)_3") (pintype "input"))
    )
    (net (code "94") (name "Net-(LED9-A)") (class "Default")
      (node (ref "LED9") (pin "1") (pinfunction "A_1") (pintype "passive"))
      (node (ref "R51") (pin "P$1") (pinfunction "1_P$1") (pintype "passive"))
    )
    (net (code "95") (name "Net-(LED9-C)") (class "Default")
      (node (ref "LED9") (pin "2") (pinfunction "C_2") (pintype "passive"))
      (node (ref "U$8") (pin "P$1") (pinfunction "VC-_P$1") (pintype "bidirectional"))
      (node (ref "U17") (pin "3") (pinfunction "C(3)_3") (pintype "input"))
    )
    (net (code "96") (name "Net-(LED10-A)") (class "Default")
      (node (ref "LED10") (pin "1") (pinfunction "A_1") (pintype "passive"))
      (node (ref "R58") (pin "P$1") (pinfunction "1_P$1") (pintype "passive"))
    )
    (net (code "97") (name "Net-(LED11-A)") (class "Default")
      (node (ref "LED11") (pin "1") (pinfunction "A_1") (pintype "passive"))
      (node (ref "R73") (pin "P$1") (pinfunction "1_P$1") (pintype "passive"))
    )
    (net (code "98") (name "Net-(LED12-A)") (class "Default")
      (node (ref "LED12") (pin "1") (pinfunction "A_1") (pintype "passive"))
      (node (ref "R76") (pin "P$1") (pinfunction "1_P$1") (pintype "passive"))
    )
    (net (code "99") (name "Net-(LED13-A)") (class "Default")
      (node (ref "LED13") (pin "1") (pinfunction "A_1") (pintype "passive"))
      (node (ref "R79") (pin "P$1") (pinfunction "1_P$1") (pintype "passive"))
    )
    (net (code "100") (name "Net-(LED14-A)") (class "Default")
      (node (ref "LED14") (pin "1") (pinfunction "A_1") (pintype "passive"))
      (node (ref "R82") (pin "P$1") (pinfunction "1_P$1") (pintype "passive"))
    )
    (net (code "101") (name "Net-(LED15-A)") (class "Default")
      (node (ref "LED15") (pin "1") (pinfunction "A_1") (pintype "passive"))
      (node (ref "R97") (pin "P$1") (pinfunction "1_P$1") (pintype "passive"))
    )
    (net (code "102") (name "Net-(LED16-A)") (class "Default")
      (node (ref "LED16") (pin "1") (pinfunction "A_1") (pintype "passive"))
      (node (ref "R100") (pin "P$1") (pinfunction "1_P$1") (pintype "passive"))
    )
    (net (code "103") (name "Net-(R22-2)") (class "Default")
      (node (ref "R22") (pin "P$2") (pinfunction "2_P$2") (pintype "passive"))
      (node (ref "U3") (pin "27") (pinfunction "USBHS_RREF_27") (pintype "bidirectional"))
    )
    (net (code "104") (name "Net-(R23-2)") (class "Default")
      (node (ref "R23") (pin "P$2") (pinfunction "2_P$2") (pintype "passive"))
      (node (ref "U3") (pin "64") (pinfunction "VLO1(DCDC)_64") (pintype "bidirectional"))
    )
    (net (code "105") (name "Net-(R24-2)") (class "Default")
      (node (ref "R24") (pin "P$2") (pinfunction "2_P$2") (pintype "passive"))
      (node (ref "U3") (pin "65") (pinfunction "VLO2(DCDC)_65") (pintype "bidirectional"))
    )
    (net (code "106") (name "Net-(R28-2)") (class "Default")
      (node (ref "R28") (pin "P$2") (pinfunction "2_P$2") (pintype "passive"))
      (node (ref "U5") (pin "1") (pinfunction "B(2)_1") (pintype "input"))
    )
    (net (code "107") (name "Net-(R29-2)") (class "Default")
      (node (ref "R29") (pin "P$2") (pinfunction "2_P$2") (pintype "passive"))
      (node (ref "U6") (pin "1") (pinfunction "B(2)_1") (pintype "input"))
    )
    (net (code "108") (name "Net-(R30-2)") (class "Default")
      (node (ref "R30") (pin "P$2") (pinfunction "2_P$2") (pintype "passive"))
      (node (ref "U7") (pin "1") (pinfunction "B(2)_1") (pintype "input"))
    )
    (net (code "109") (name "Net-(R35-2)") (class "Default")
      (node (ref "R35") (pin "P$2") (pinfunction "2_P$2") (pintype "passive"))
      (node (ref "U8") (pin "1") (pinfunction "B(2)_1") (pintype "input"))
    )
    (net (code "110") (name "Net-(R49-2)") (class "Default")
      (node (ref "R49") (pin "P$2") (pinfunction "2_P$2") (pintype "passive"))
      (node (ref "U16") (pin "1") (pinfunction "B(2)_1") (pintype "input"))
    )
    (net (code "111") (name "Net-(R50-2)") (class "Default")
      (node (ref "R50") (pin "P$2") (pinfunction "2_P$2") (pintype "passive"))
      (node (ref "U17") (pin "1") (pinfunction "B(2)_1") (pintype "input"))
    )
    (net (code "112") (name "Net-(R54-2)") (class "Default")
      (node (ref "R54") (pin "P$2") (pinfunction "2_P$2") (pintype "passive"))
      (node (ref "U9") (pin "1") (pinfunction "B(2)_1") (pintype "input"))
    )
    (net (code "113") (name "Net-(R57-2)") (class "Default")
      (node (ref "R57") (pin "P$2") (pinfunction "2_P$2") (pintype "passive"))
      (node (ref "U18") (pin "1") (pinfunction "B(2)_1") (pintype "input"))
    )
    (net (code "114") (name "Net-(R60-2)") (class "Default")
      (node (ref "R60") (pin "P$2") (pinfunction "2_P$2") (pintype "passive"))
      (node (ref "U19") (pin "1") (pinfunction "B(2)_1") (pintype "input"))
    )
    (net (code "115") (name "Net-(R75-2)") (class "Default")
      (node (ref "R75") (pin "P$2") (pinfunction "2_P$2") (pintype "passive"))
      (node (ref "U20") (pin "1") (pinfunction "B(2)_1") (pintype "input"))
    )
    (net (code "116") (name "Net-(R78-2)") (class "Default")
      (node (ref "R78") (pin "P$2") (pinfunction "2_P$2") (pintype "passive"))
      (node (ref "U21") (pin "1") (pinfunction "B(2)_1") (pintype "input"))
    )
    (net (code "117") (name "Net-(R81-2)") (class "Default")
      (node (ref "R81") (pin "P$2") (pinfunction "2_P$2") (pintype "passive"))
      (node (ref "U28") (pin "1") (pinfunction "B(2)_1") (pintype "input"))
    )
    (net (code "118") (name "Net-(R84-2)") (class "Default")
      (node (ref "R84") (pin "P$2") (pinfunction "2_P$2") (pintype "passive"))
      (node (ref "U29") (pin "1") (pinfunction "B(2)_1") (pintype "input"))
    )
    (net (code "119") (name "Net-(R99-2)") (class "Default")
      (node (ref "R99") (pin "P$2") (pinfunction "2_P$2") (pintype "passive"))
      (node (ref "U30") (pin "1") (pinfunction "B(2)_1") (pintype "input"))
    )
    (net (code "120") (name "Net-(U10-B(2))") (class "Default")
      (node (ref "R38") (pin "2") (pinfunction "2_2") (pintype "passive"))
      (node (ref "U10") (pin "1") (pinfunction "B(2)_1") (pintype "input"))
    )
    (net (code "121") (name "Net-(U11-B(2))") (class "Default")
      (node (ref "R39") (pin "2") (pinfunction "2_2") (pintype "passive"))
      (node (ref "U11") (pin "1") (pinfunction "B(2)_1") (pintype "input"))
    )
    (net (code "122") (name "Net-(U12-B(2))") (class "Default")
      (node (ref "R40") (pin "2") (pinfunction "2_2") (pintype "passive"))
      (node (ref "U12") (pin "1") (pinfunction "B(2)_1") (pintype "input"))
    )
    (net (code "123") (name "Net-(U13-B(2))") (class "Default")
      (node (ref "R44") (pin "2") (pinfunction "2_2") (pintype "passive"))
      (node (ref "U13") (pin "1") (pinfunction "B(2)_1") (pintype "input"))
    )
    (net (code "124") (name "Net-(U14-B(2))") (class "Default")
      (node (ref "R45") (pin "2") (pinfunction "2_2") (pintype "passive"))
      (node (ref "U14") (pin "1") (pinfunction "B(2)_1") (pintype "input"))
    )
    (net (code "125") (name "Net-(U15-B(2))") (class "Default")
      (node (ref "R46") (pin "2") (pinfunction "2_2") (pintype "passive"))
      (node (ref "U15") (pin "1") (pinfunction "B(2)_1") (pintype "input"))
    )
    (net (code "126") (name "Net-(U22-B(2))") (class "Default")
      (node (ref "R62") (pin "2") (pinfunction "2_2") (pintype "passive"))
      (node (ref "U22") (pin "1") (pinfunction "B(2)_1") (pintype "input"))
    )
    (net (code "127") (name "Net-(U23-B(2))") (class "Default")
      (node (ref "R63") (pin "2") (pinfunction "2_2") (pintype "passive"))
      (node (ref "U23") (pin "1") (pinfunction "B(2)_1") (pintype "input"))
    )
    (net (code "128") (name "Net-(U24-B(2))") (class "Default")
      (node (ref "R64") (pin "2") (pinfunction "2_2") (pintype "passive"))
      (node (ref "U24") (pin "1") (pinfunction "B(2)_1") (pintype "input"))
    )
    (net (code "129") (name "Net-(U25-B(2))") (class "Default")
      (node (ref "R68") (pin "2") (pinfunction "2_2") (pintype "passive"))
      (node (ref "U25") (pin "1") (pinfunction "B(2)_1") (pintype "input"))
    )
    (net (code "130") (name "Net-(U26-B(2))") (class "Default")
      (node (ref "R69") (pin "2") (pinfunction "2_2") (pintype "passive"))
      (node (ref "U26") (pin "1") (pinfunction "B(2)_1") (pintype "input"))
    )
    (net (code "131") (name "Net-(U27-B(2))") (class "Default")
      (node (ref "R70") (pin "2") (pinfunction "2_2") (pintype "passive"))
      (node (ref "U27") (pin "1") (pinfunction "B(2)_1") (pintype "input"))
    )
    (net (code "132") (name "Net-(U34-B(2))") (class "Default")
      (node (ref "R86") (pin "2") (pinfunction "2_2") (pintype "passive"))
      (node (ref "U34") (pin "1") (pinfunction "B(2)_1") (pintype "input"))
    )
    (net (code "133") (name "Net-(U35-B(2))") (class "Default")
      (node (ref "R87") (pin "2") (pinfunction "2_2") (pintype "passive"))
      (node (ref "U35") (pin "1") (pinfunction "B(2)_1") (pintype "input"))
    )
    (net (code "134") (name "Net-(U36-B(2))") (class "Default")
      (node (ref "R88") (pin "2") (pinfunction "2_2") (pintype "passive"))
      (node (ref "U36") (pin "1") (pinfunction "B(2)_1") (pintype "input"))
    )
    (net (code "135") (name "Net-(U37-B(2))") (class "Default")
      (node (ref "R92") (pin "2") (pinfunction "2_2") (pintype "passive"))
      (node (ref "U37") (pin "1") (pinfunction "B(2)_1") (pintype "input"))
    )
    (net (code "136") (name "Net-(U38-B(2))") (class "Default")
      (node (ref "R93") (pin "2") (pinfunction "2_2") (pintype "passive"))
      (node (ref "U38") (pin "1") (pinfunction "B(2)_1") (pintype "input"))
    )
    (net (code "137") (name "Net-(U39-B(2))") (class "Default")
      (node (ref "R94") (pin "2") (pinfunction "2_2") (pintype "passive"))
      (node (ref "U39") (pin "1") (pinfunction "B(2)_1") (pintype "input"))
    )
    (net (code "138") (name "Net-(U46-B(2))") (class "Default")
      (node (ref "R110") (pin "2") (pinfunction "2_2") (pintype "passive"))
      (node (ref "U46") (pin "1") (pinfunction "B(2)_1") (pintype "input"))
    )
    (net (code "139") (name "Net-(U47-B(2))") (class "Default")
      (node (ref "R111") (pin "2") (pinfunction "2_2") (pintype "passive"))
      (node (ref "U47") (pin "1") (pinfunction "B(2)_1") (pintype "input"))
    )
    (net (code "140") (name "Net-(U48-B(2))") (class "Default")
      (node (ref "R112") (pin "2") (pinfunction "2_2") (pintype "passive"))
      (node (ref "U48") (pin "1") (pinfunction "B(2)_1") (pintype "input"))
    )
    (net (code "141") (name "Net-(U49-B(2))") (class "Default")
      (node (ref "R116") (pin "2") (pinfunction "2_2") (pintype "passive"))
      (node (ref "U49") (pin "1") (pinfunction "B(2)_1") (pintype "input"))
    )
    (net (code "142") (name "Net-(U50-B(2))") (class "Default")
      (node (ref "R117") (pin "2") (pinfunction "2_2") (pintype "passive"))
      (node (ref "U50") (pin "1") (pinfunction "B(2)_1") (pintype "input"))
    )
    (net (code "143") (name "Net-(U51-B(2))") (class "Default")
      (node (ref "R118") (pin "2") (pinfunction "2_2") (pintype "passive"))
      (node (ref "U51") (pin "1") (pinfunction "B(2)_1") (pintype "input"))
    )
    (net (code "144") (name "Net-(U58-B(2))") (class "Default")
      (node (ref "R134") (pin "2") (pinfunction "2_2") (pintype "passive"))
      (node (ref "U58") (pin "1") (pinfunction "B(2)_1") (pintype "input"))
    )
    (net (code "145") (name "Net-(U59-B(2))") (class "Default")
      (node (ref "R135") (pin "2") (pinfunction "2_2") (pintype "passive"))
      (node (ref "U59") (pin "1") (pinfunction "B(2)_1") (pintype "input"))
    )
    (net (code "146") (name "Net-(U60-B(2))") (class "Default")
      (node (ref "R136") (pin "2") (pinfunction "2_2") (pintype "passive"))
      (node (ref "U60") (pin "1") (pinfunction "B(2)_1") (pintype "input"))
    )
    (net (code "147") (name "Net-(U61-B(2))") (class "Default")
      (node (ref "R140") (pin "2") (pinfunction "2_2") (pintype "passive"))
      (node (ref "U61") (pin "1") (pinfunction "B(2)_1") (pintype "input"))
    )
    (net (code "148") (name "Net-(U62-B(2))") (class "Default")
      (node (ref "R141") (pin "2") (pinfunction "2_2") (pintype "passive"))
      (node (ref "U62") (pin "1") (pinfunction "B(2)_1") (pintype "input"))
    )
    (net (code "149") (name "Net-(U63-B(2))") (class "Default")
      (node (ref "R142") (pin "2") (pinfunction "2_2") (pintype "passive"))
      (node (ref "U63") (pin "1") (pinfunction "B(2)_1") (pintype "input"))
    )
    (net (code "150") (name "Net-(U70-B(2))") (class "Default")
      (node (ref "R158") (pin "2") (pinfunction "2_2") (pintype "passive"))
      (node (ref "U70") (pin "1") (pinfunction "B(2)_1") (pintype "input"))
    )
    (net (code "151") (name "Net-(U71-B(2))") (class "Default")
      (node (ref "R159") (pin "2") (pinfunction "2_2") (pintype "passive"))
      (node (ref "U71") (pin "1") (pinfunction "B(2)_1") (pintype "input"))
    )
    (net (code "152") (name "Net-(U72-B(2))") (class "Default")
      (node (ref "R160") (pin "2") (pinfunction "2_2") (pintype "passive"))
      (node (ref "U72") (pin "1") (pinfunction "B(2)_1") (pintype "input"))
    )
    (net (code "153") (name "Net-(U73-B(2))") (class "Default")
      (node (ref "R164") (pin "2") (pinfunction "2_2") (pintype "passive"))
      (node (ref "U73") (pin "1") (pinfunction "B(2)_1") (pintype "input"))
    )
    (net (code "154") (name "Net-(U74-B(2))") (class "Default")
      (node (ref "R165") (pin "2") (pinfunction "2_2") (pintype "passive"))
      (node (ref "U74") (pin "1") (pinfunction "B(2)_1") (pintype "input"))
    )
    (net (code "155") (name "Net-(U75-B(2))") (class "Default")
      (node (ref "R166") (pin "2") (pinfunction "2_2") (pintype "passive"))
      (node (ref "U75") (pin "1") (pinfunction "B(2)_1") (pintype "input"))
    )
    (net (code "156") (name "P0_00") (class "Default")
      (node (ref "J4") (pin "P$2") (pinfunction "P$2_P$2") (pintype "bidirectional"))
      (node (ref "U3") (pin "169") (pinfunction "P0_0/AN0\\00_169") (pintype "bidirectional"))
    )
    (net (code "157") (name "P0_01") (class "Default")
      (node (ref "J4") (pin "P$1") (pinfunction "P$1_P$1") (pintype "bidirectional"))
      (node (ref "U3") (pin "168") (pinfunction "P0_1/AN001_168") (pintype "bidirectional"))
    )
    (net (code "158") (name "P0_02") (class "Default")
      (node (ref "J39") (pin "P$20") (pinfunction "P$20_P$20") (pintype "bidirectional"))
      (node (ref "R25") (pin "P$1") (pinfunction "1_P$1") (pintype "passive"))
      (node (ref "U3") (pin "167") (pinfunction "P0_2/AN002_167") (pintype "bidirectional"))
    )
    (net (code "159") (name "P0_03") (class "Default")
      (node (ref "J39") (pin "P$18") (pinfunction "P$18_P$18") (pintype "bidirectional"))
      (node (ref "R26") (pin "P$1") (pinfunction "1_P$1") (pintype "passive"))
      (node (ref "U3") (pin "166") (pinfunction "P0_3/PGAVSS000_166") (pintype "bidirectional"))
    )
    (net (code "160") (name "P0_04") (class "Default")
      (node (ref "J39") (pin "P$16") (pinfunction "P$16_P$16") (pintype "bidirectional"))
      (node (ref "R27") (pin "P$1") (pinfunction "1_P$1") (pintype "passive"))
      (node (ref "U3") (pin "165") (pinfunction "P0_4/AN100_165") (pintype "bidirectional"))
    )
    (net (code "161") (name "P0_05") (class "Default")
      (node (ref "J39") (pin "P$14") (pinfunction "P$14_P$14") (pintype "bidirectional"))
      (node (ref "R102") (pin "P$1") (pinfunction "1_P$1") (pintype "passive"))
      (node (ref "U3") (pin "164") (pinfunction "P0_5/AN101_164") (pintype "bidirectional"))
    )
    (net (code "162") (name "P0_06") (class "Default")
      (node (ref "J39") (pin "P$12") (pinfunction "P$12_P$12") (pintype "bidirectional"))
      (node (ref "R103") (pin "P$1") (pinfunction "1_P$1") (pintype "passive"))
      (node (ref "U3") (pin "163") (pinfunction "P0_6/AN102_163") (pintype "bidirectional"))
    )
    (net (code "163") (name "P0_07") (class "Default")
      (node (ref "J39") (pin "P$10") (pinfunction "P$10_P$10") (pintype "bidirectional"))
      (node (ref "R104") (pin "P$1") (pinfunction "1_P$1") (pintype "passive"))
      (node (ref "U3") (pin "162") (pinfunction "P0_7/PGVSS100_162") (pintype "bidirectional"))
    )
    (net (code "164") (name "P0_08") (class "Default")
      (node (ref "J39") (pin "P$8") (pinfunction "P$8_P$8") (pintype "bidirectional"))
      (node (ref "R105") (pin "P$1") (pinfunction "1_P$1") (pintype "passive"))
      (node (ref "U3") (pin "161") (pinfunction "P0_8/AN003_161") (pintype "bidirectional"))
    )
    (net (code "165") (name "P0_09") (class "Default")
      (node (ref "J39") (pin "P$6") (pinfunction "P$6_P$6") (pintype "bidirectional"))
      (node (ref "R106") (pin "P$1") (pinfunction "1_P$1") (pintype "passive"))
      (node (ref "U3") (pin "160") (pinfunction "P0_9/AN004_160") (pintype "bidirectional"))
    )
    (net (code "166") (name "P0_14") (class "Default")
      (node (ref "J39") (pin "P$4") (pinfunction "P$4_P$4") (pintype "bidirectional"))
      (node (ref "R107") (pin "P$1") (pinfunction "1_P$1") (pintype "passive"))
      (node (ref "U3") (pin "152") (pinfunction "P0_14/DA0/AN005/AN105_152") (pintype "bidirectional"))
    )
    (net (code "167") (name "P0_15") (class "Default")
      (node (ref "J39") (pin "P$2") (pinfunction "P$2_P$2") (pintype "bidirectional"))
      (node (ref "R108") (pin "P$1") (pinfunction "1_P$1") (pintype "passive"))
      (node (ref "U3") (pin "151") (pinfunction "P0_15/DA1/AN006/AN106_151") (pintype "bidirectional"))
    )
    (net (code "168") (name "P1_02") (class "Default")
      (node (ref "J8") (pin "P$10") (pinfunction "P$10_P$10") (pintype "bidirectional"))
      (node (ref "U3") (pin "130") (pinfunction "P1_2_130") (pintype "bidirectional"))
    )
    (net (code "169") (name "P1_03") (class "Default")
      (node (ref "J8") (pin "P$9") (pinfunction "P$9_P$9") (pintype "bidirectional"))
      (node (ref "U3") (pin "129") (pinfunction "P1_3_129") (pintype "bidirectional"))
    )
    (net (code "170") (name "P1_04") (class "Default")
      (node (ref "J8") (pin "P$11") (pinfunction "P$11_P$11") (pintype "bidirectional"))
      (node (ref "U3") (pin "128") (pinfunction "P1_4_128") (pintype "bidirectional"))
    )
    (net (code "171") (name "P1_05") (class "Default")
      (node (ref "J8") (pin "P$13") (pinfunction "P$13_P$13") (pintype "bidirectional"))
      (node (ref "U3") (pin "127") (pinfunction "P1_5_127") (pintype "bidirectional"))
    )
    (net (code "172") (name "P1_06") (class "Default")
      (node (ref "J8") (pin "P$15") (pinfunction "P$15_P$15") (pintype "bidirectional"))
      (node (ref "U3") (pin "126") (pinfunction "P1_6_126") (pintype "bidirectional"))
    )
    (net (code "173") (name "P1_07") (class "Default")
      (node (ref "J8") (pin "P$17") (pinfunction "P$17_P$17") (pintype "bidirectional"))
      (node (ref "U3") (pin "125") (pinfunction "P1_7_125") (pintype "bidirectional"))
    )
    (net (code "174") (name "P4_00") (class "Default")
      (node (ref "J4") (pin "P$7") (pinfunction "P$7_P$7") (pintype "bidirectional"))
      (node (ref "U3") (pin "1") (pinfunction "P4_0_1") (pintype "bidirectional"))
    )
    (net (code "175") (name "P4_01") (class "Default")
      (node (ref "J4") (pin "P$8") (pinfunction "P$8_P$8") (pintype "bidirectional"))
      (node (ref "U3") (pin "2") (pinfunction "P4_1_2") (pintype "bidirectional"))
    )
    (net (code "176") (name "P4_02") (class "Default")
      (node (ref "J4") (pin "P$9") (pinfunction "P$9_P$9") (pintype "bidirectional"))
      (node (ref "U3") (pin "3") (pinfunction "P4_2_3") (pintype "bidirectional"))
    )
    (net (code "177") (name "P4_08") (class "Default")
      (node (ref "J4") (pin "P$20") (pinfunction "P$20_P$20") (pintype "bidirectional"))
      (node (ref "U3") (pin "43") (pinfunction "P4_8_43") (pintype "bidirectional"))
    )
    (net (code "178") (name "P4_09") (class "Default")
      (node (ref "J4") (pin "P$19") (pinfunction "P$19_P$19") (pintype "bidirectional"))
      (node (ref "U3") (pin "42") (pinfunction "P4_9_42") (pintype "bidirectional"))
    )
    (net (code "179") (name "P4_10") (class "Default")
      (node (ref "J4") (pin "P$18") (pinfunction "P$18_P$18") (pintype "bidirectional"))
      (node (ref "U3") (pin "41") (pinfunction "P4_10_41") (pintype "bidirectional"))
    )
    (net (code "180") (name "P4_11") (class "Default")
      (node (ref "J4") (pin "P$17") (pinfunction "P$17_P$17") (pintype "bidirectional"))
      (node (ref "U3") (pin "40") (pinfunction "P4_11_40") (pintype "bidirectional"))
    )
    (net (code "181") (name "P4_12") (class "Default")
      (node (ref "J4") (pin "P$16") (pinfunction "P$16_P$16") (pintype "bidirectional"))
      (node (ref "U3") (pin "39") (pinfunction "P4_12_39") (pintype "bidirectional"))
    )
    (net (code "182") (name "P4_13") (class "Default")
      (node (ref "J4") (pin "P$15") (pinfunction "P$15_P$15") (pintype "bidirectional"))
      (node (ref "U3") (pin "38") (pinfunction "P4_13_38") (pintype "bidirectional"))
    )
    (net (code "183") (name "P4_14") (class "Default")
      (node (ref "J4") (pin "P$14") (pinfunction "P$14_P$14") (pintype "bidirectional"))
      (node (ref "U3") (pin "37") (pinfunction "P4_14_37") (pintype "bidirectional"))
    )
    (net (code "184") (name "P4_15") (class "Default")
      (node (ref "J4") (pin "P$13") (pinfunction "P$13_P$13") (pintype "bidirectional"))
      (node (ref "U3") (pin "36") (pinfunction "P4_15_36") (pintype "bidirectional"))
    )
    (net (code "185") (name "P5_11") (class "Default")
      (node (ref "J4") (pin "P$6") (pinfunction "P$6_P$6") (pintype "bidirectional"))
      (node (ref "U3") (pin "176") (pinfunction "P5_11_176") (pintype "bidirectional"))
    )
    (net (code "186") (name "P5_12") (class "Default")
      (node (ref "J4") (pin "P$5") (pinfunction "P$5_P$5") (pintype "bidirectional"))
      (node (ref "U3") (pin "175") (pinfunction "P5_12_175") (pintype "bidirectional"))
    )
    (net (code "187") (name "P5_13") (class "Default")
      (node (ref "J4") (pin "P$4") (pinfunction "P$4_P$4") (pintype "bidirectional"))
      (node (ref "U3") (pin "174") (pinfunction "P5_13_174") (pintype "bidirectional"))
    )
    (net (code "188") (name "P6_00") (class "Default")
      (node (ref "J8") (pin "P$19") (pinfunction "P$19_P$19") (pintype "bidirectional"))
      (node (ref "U3") (pin "122") (pinfunction "P6_0_122") (pintype "bidirectional"))
    )
    (net (code "189") (name "P7_06") (class "Default")
      (node (ref "J4") (pin "P$10") (pinfunction "P$10_P$10") (pintype "bidirectional"))
      (node (ref "U3") (pin "14") (pinfunction "P7_6_14") (pintype "bidirectional"))
    )
    (net (code "190") (name "P7_07") (class "Default")
      (node (ref "J4") (pin "P$11") (pinfunction "P$11_P$11") (pintype "bidirectional"))
      (node (ref "U3") (pin "15") (pinfunction "P7_7_15") (pintype "bidirectional"))
    )
    (net (code "191") (name "P8_00") (class "Default")
      (node (ref "J8") (pin "P$5") (pinfunction "P$5_P$5") (pintype "bidirectional"))
      (node (ref "U3") (pin "133") (pinfunction "P8_0_133") (pintype "bidirectional"))
    )
    (net (code "192") (name "P8_01") (class "Default")
      (node (ref "J8") (pin "P$3") (pinfunction "P$3_P$3") (pintype "bidirectional"))
      (node (ref "U3") (pin "134") (pinfunction "P8_1_134") (pintype "bidirectional"))
    )
    (net (code "193") (name "P8_02") (class "Default")
      (node (ref "J8") (pin "P$4") (pinfunction "P$4_P$4") (pintype "bidirectional"))
      (node (ref "U3") (pin "135") (pinfunction "P8_2_135") (pintype "bidirectional"))
    )
    (net (code "194") (name "P8_03") (class "Default")
      (node (ref "J8") (pin "P$1") (pinfunction "P$1_P$1") (pintype "bidirectional"))
      (node (ref "U3") (pin "136") (pinfunction "P8_3_136") (pintype "bidirectional"))
    )
    (net (code "195") (name "P8_04") (class "Default")
      (node (ref "J8") (pin "P$2") (pinfunction "P$2_P$2") (pintype "bidirectional"))
      (node (ref "U3") (pin "137") (pinfunction "P8_4_137") (pintype "bidirectional"))
    )
    (net (code "196") (name "P8_05") (class "Default")
      (node (ref "J4") (pin "P$3") (pinfunction "P$3_P$3") (pintype "bidirectional"))
      (node (ref "U3") (pin "173") (pinfunction "P8_5_173") (pintype "bidirectional"))
    )
    (net (code "197") (name "PB_00") (class "Default")
      (node (ref "J4") (pin "P$12") (pinfunction "P$12_P$12") (pintype "bidirectional"))
      (node (ref "U3") (pin "16") (pinfunction "PB_0_16") (pintype "bidirectional"))
    )
    (net (code "198") (name "R51") (class "Default")
      (node (ref "R7") (pin "P$1") (pinfunction "1_P$1") (pintype "passive"))
      (node (ref "RJ1") (pin "12") (pinfunction "YHI_12") (pintype "bidirectional"))
    )
    (net (code "199") (name "R52") (class "Default")
      (node (ref "R8") (pin "P$1") (pinfunction "1_P$1") (pintype "passive"))
      (node (ref "RJ1") (pin "9") (pinfunction "GHI_9") (pintype "bidirectional"))
    )
    (net (code "200") (name "RELAY_1") (class "Default")
      (node (ref "R29") (pin "P$1") (pinfunction "1_P$1") (pintype "passive"))
      (node (ref "U3") (pin "56") (pinfunction "P3_14_56") (pintype "bidirectional"))
    )
    (net (code "201") (name "RELAY_2") (class "Default")
      (node (ref "R30") (pin "P$1") (pinfunction "1_P$1") (pintype "passive"))
      (node (ref "U3") (pin "55") (pinfunction "P3_13_55") (pintype "bidirectional"))
    )
    (net (code "202") (name "RELAY_3") (class "Default")
      (node (ref "R49") (pin "P$1") (pinfunction "1_P$1") (pintype "passive"))
      (node (ref "U3") (pin "52") (pinfunction "P2_4_52") (pintype "bidirectional"))
    )
    (net (code "203") (name "RELAY_4") (class "Default")
      (node (ref "R50") (pin "P$1") (pinfunction "1_P$1") (pintype "passive"))
      (node (ref "U3") (pin "49") (pinfunction "P2_7_49") (pintype "bidirectional"))
    )
    (net (code "204") (name "RESET") (class "Default")
      (node (ref "C16") (pin "P$1") (pinfunction "1_P$1") (pintype "passive"))
      (node (ref "J3") (pin "9") (pinfunction "9_9") (pintype "passive"))
      (node (ref "R13") (pin "P$1") (pinfunction "1_P$1") (pintype "passive"))
      (node (ref "U3") (pin "67") (pinfunction "RES#_67") (pintype "bidirectional"))
    )
    (net (code "205") (name "REXT") (class "Default")
      (node (ref "C3") (pin "P$1") (pinfunction "1_P$1") (pintype "passive"))
      (node (ref "R1") (pin "P$2") (pinfunction "2_P$2") (pintype "passive"))
      (node (ref "U1") (pin "9") (pinfunction "REXT_9") (pintype "input"))
    )
    (net (code "206") (name "RO_NEG_1") (class "Default")
      (node (ref "J15") (pin "P$2") (pinfunction "P$2_P$2") (pintype "bidirectional"))
      (node (ref "U$1") (pin "P$3") (pinfunction "VO-_P$3") (pintype "bidirectional"))
    )
    (net (code "207") (name "RO_NEG_2") (class "Default")
      (node (ref "J16") (pin "P$2") (pinfunction "P$2_P$2") (pintype "bidirectional"))
      (node (ref "U$2") (pin "P$3") (pinfunction "VO-_P$3") (pintype "bidirectional"))
    )
    (net (code "208") (name "RO_NEG_3") (class "Default")
      (node (ref "J23") (pin "P$2") (pinfunction "P$2_P$2") (pintype "bidirectional"))
      (node (ref "U$7") (pin "P$3") (pinfunction "VO-_P$3") (pintype "bidirectional"))
    )
    (net (code "209") (name "RO_NEG_4") (class "Default")
      (node (ref "J24") (pin "P$2") (pinfunction "P$2_P$2") (pintype "bidirectional"))
      (node (ref "U$8") (pin "P$3") (pinfunction "VO-_P$3") (pintype "bidirectional"))
    )
    (net (code "210") (name "RO_POS_1") (class "Default")
      (node (ref "J15") (pin "P$1") (pinfunction "P$1_P$1") (pintype "bidirectional"))
      (node (ref "U$1") (pin "P$4") (pinfunction "VO+_P$4") (pintype "bidirectional"))
    )
    (net (code "211") (name "RO_POS_2") (class "Default")
      (node (ref "J16") (pin "P$1") (pinfunction "P$1_P$1") (pintype "bidirectional"))
      (node (ref "U$2") (pin "P$4") (pinfunction "VO+_P$4") (pintype "bidirectional"))
    )
    (net (code "212") (name "RO_POS_3") (class "Default")
      (node (ref "J23") (pin "P$1") (pinfunction "P$1_P$1") (pintype "bidirectional"))
      (node (ref "U$7") (pin "P$4") (pinfunction "VO+_P$4") (pintype "bidirectional"))
    )
    (net (code "213") (name "RO_POS_4") (class "Default")
      (node (ref "J24") (pin "P$1") (pinfunction "P$1_P$1") (pintype "bidirectional"))
      (node (ref "U$8") (pin "P$4") (pinfunction "VO+_P$4") (pintype "bidirectional"))
    )
    (net (code "214") (name "RXD0") (class "Default")
      (node (ref "R10") (pin "P$2") (pinfunction "2_P$2") (pintype "passive"))
      (node (ref "U1") (pin "13") (pinfunction "RXD0_13") (pintype "bidirectional"))
    )
    (net (code "215") (name "RXD1") (class "Default")
      (node (ref "R9") (pin "P$2") (pinfunction "2_P$2") (pintype "passive"))
      (node (ref "U1") (pin "12") (pinfunction "RXD1_12") (pintype "bidirectional"))
    )
    (net (code "216") (name "RXER") (class "Default")
      (node (ref "R11") (pin "P$2") (pinfunction "2_P$2") (pintype "passive"))
      (node (ref "U1") (pin "17") (pinfunction "RXER_17") (pintype "bidirectional"))
    )
    (net (code "217") (name "RXM") (class "Default")
      (node (ref "RJ1") (pin "6") (pinfunction "RD-_6") (pintype "bidirectional"))
      (node (ref "U1") (pin "3") (pinfunction "RXM_3") (pintype "bidirectional"))
    )
    (net (code "218") (name "RXP") (class "Default")
      (node (ref "RJ1") (pin "3") (pinfunction "RD+_3") (pintype "bidirectional"))
      (node (ref "U1") (pin "4") (pinfunction "RXP_4") (pintype "bidirectional"))
    )
    (net (code "219") (name "SD1_CD") (class "Default")
      (node (ref "J1") (pin "10") (pinfunction "CD_SWITCH2_10") (pintype "bidirectional"))
      (node (ref "U3") (pin "146") (pinfunction "P5_6/AN019_146") (pintype "bidirectional"))
    )
    (net (code "220") (name "SD1_CLK") (class "Default")
      (node (ref "J1") (pin "5") (pinfunction "CLOCK_5") (pintype "bidirectional"))
      (node (ref "U3") (pin "140") (pinfunction "P5_0/AN016_140") (pintype "bidirectional"))
    )
    (net (code "221") (name "SD1_CMD") (class "Default")
      (node (ref "J1") (pin "3") (pinfunction "COMMAND/RESPONSE_3") (pintype "bidirectional"))
      (node (ref "U3") (pin "141") (pinfunction "P5_1/AN116_141") (pintype "bidirectional"))
    )
    (net (code "222") (name "SD1_DAT0") (class "Default")
      (node (ref "J1") (pin "7") (pinfunction "DATA_LINE[BIT_0]_7") (pintype "bidirectional"))
      (node (ref "U3") (pin "142") (pinfunction "P5_2/AN017_142") (pintype "bidirectional"))
    )
    (net (code "223") (name "SD1_DAT1") (class "Default")
      (node (ref "J1") (pin "8") (pinfunction "DATA_LINE[BIT_1]_8") (pintype "bidirectional"))
      (node (ref "U3") (pin "143") (pinfunction "P5_3/AN117_143") (pintype "bidirectional"))
    )
    (net (code "224") (name "SD1_DAT2") (class "Default")
      (node (ref "J1") (pin "1") (pinfunction "DATA_LINE[BIT_2]_1") (pintype "bidirectional"))
      (node (ref "U3") (pin "144") (pinfunction "P5_4/AN018_144") (pintype "bidirectional"))
    )
    (net (code "225") (name "SD1_DAT3") (class "Default")
      (node (ref "J1") (pin "2") (pinfunction "CARD_DETECT/DATA_LINE[BIT_3]_2") (pintype "bidirectional"))
      (node (ref "U3") (pin "145") (pinfunction "P5_5/AN118_145") (pintype "bidirectional"))
    )
    (net (code "226") (name "SD1_WP") (class "Default")
      (node (ref "J1") (pin "9") (pinfunction "CD_SWITCH1_9") (pintype "bidirectional"))
      (node (ref "U3") (pin "147") (pinfunction "P5_7/AN119_147") (pintype "bidirectional"))
    )
    (net (code "227") (name "TCK") (class "Default")
      (node (ref "J3") (pin "7") (pinfunction "7_7") (pintype "passive"))
      (node (ref "U3") (pin "88") (pinfunction "P3_0_88") (pintype "bidirectional"))
    )
    (net (code "228") (name "TDI") (class "Default")
      (node (ref "J3") (pin "1") (pinfunction "1_1") (pintype "passive"))
      (node (ref "U3") (pin "91") (pinfunction "P1_10_91") (pintype "bidirectional"))
    )
    (net (code "229") (name "TDO") (class "Default")
      (node (ref "J3") (pin "3") (pinfunction "3_3") (pintype "passive"))
      (node (ref "U3") (pin "90") (pinfunction "P1_9_90") (pintype "bidirectional"))
    )
    (net (code "230") (name "TMS") (class "Default")
      (node (ref "J3") (pin "5") (pinfunction "5_5") (pintype "passive"))
      (node (ref "U3") (pin "89") (pinfunction "P1_8_89") (pintype "bidirectional"))
    )
    (net (code "231") (name "TXM") (class "Default")
      (node (ref "RJ1") (pin "2") (pinfunction "TD-_2") (pintype "bidirectional"))
      (node (ref "U1") (pin "5") (pinfunction "TXM_5") (pintype "bidirectional"))
    )
    (net (code "232") (name "TXP") (class "Default")
      (node (ref "RJ1") (pin "1") (pinfunction "TD+_1") (pintype "bidirectional"))
      (node (ref "U1") (pin "6") (pinfunction "TXP_6") (pintype "bidirectional"))
    )
    (net (code "233") (name "USBHS_FAULT") (class "Default")
      (node (ref "R19") (pin "P$1") (pinfunction "1_P$1") (pintype "passive"))
      (node (ref "U2") (pin "3") (pinfunction "FLG_3") (pintype "input"))
      (node (ref "U3") (pin "78") (pinfunction "P3_8_78") (pintype "bidirectional"))
    )
    (net (code "234") (name "USBHS_N") (class "Default")
      (node (ref "J6") (pin "D-") (pinfunction "D-_D-") (pintype "bidirectional"))
      (node (ref "U3") (pin "31") (pinfunction "USBHS_DM_31") (pintype "bidirectional"))
    )
    (net (code "235") (name "USBHS_P") (class "Default")
      (node (ref "J6") (pin "D+") (pinfunction "D+_D+") (pintype "bidirectional"))
      (node (ref "U3") (pin "32") (pinfunction "USBHS_DP_32") (pintype "bidirectional"))
    )
    (net (code "236") (name "USBHS_VBUS") (class "Default")
      (node (ref "C29") (pin "P$1") (pinfunction "1_P$1") (pintype "passive"))
      (node (ref "C31") (pin "1") (pinfunction "1_1") (pintype "passive"))
      (node (ref "J6") (pin "VBUS") (pinfunction "VBUS_VBUS") (pintype "power_in"))
      (node (ref "U2") (pin "5") (pinfunction "OUT_5") (pintype "input"))
      (node (ref "U3") (pin "17") (pinfunction "PB_1_17") (pintype "bidirectional"))
    )
    (net (code "237") (name "USBHS_VBUSEN") (class "Default")
      (node (ref "R20") (pin "P$1") (pinfunction "1_P$1") (pintype "passive"))
      (node (ref "U2") (pin "1") (pinfunction "EN_1") (pintype "input"))
    )
    (net (code "238") (name "USB_N") (class "Default")
      (node (ref "R17") (pin "P$1") (pinfunction "1_P$1") (pintype "passive"))
      (node (ref "U3") (pin "46") (pinfunction "USB_DM_46") (pintype "bidirectional"))
    )
    (net (code "239") (name "USB_P") (class "Default")
      (node (ref "R18") (pin "P$1") (pinfunction "1_P$1") (pintype "passive"))
      (node (ref "U3") (pin "47") (pinfunction "USB_DP_47") (pintype "bidirectional"))
    )
    (net (code "240") (name "USB_VBUS_B") (class "Default")
      (node (ref "R16") (pin "P$1") (pinfunction "1_P$1") (pintype "passive"))
      (node (ref "U3") (pin "44") (pinfunction "P4_7_44") (pintype "bidirectional"))
    )
    (net (code "241") (name "VCL_F(FLASH)") (class "Default")
      (node (ref "C34") (pin "P$2") (pinfunction "2_P$2") (pintype "passive"))
      (node (ref "U3") (pin "112") (pinfunction "VCL_F(FLASH)_112") (pintype "bidirectional"))
    )
    (net (code "242") (name "VDD") (class "Default")
      (node (ref "C14") (pin "P$1") (pinfunction "1_P$1") (pintype "passive"))
      (node (ref "C15") (pin "P$1") (pinfunction "1_P$1") (pintype "passive"))
      (node (ref "C19") (pin "P$2") (pinfunction "2_P$2") (pintype "passive"))
      (node (ref "C20") (pin "P$2") (pinfunction "2_P$2") (pintype "passive"))
      (node (ref "C21") (pin "P$2") (pinfunction "2_P$2") (pintype "passive"))
      (node (ref "C22") (pin "P$2") (pinfunction "2_P$2") (pintype "passive"))
      (node (ref "C25") (pin "P$2") (pinfunction "2_P$2") (pintype "passive"))
      (node (ref "C27") (pin "P$2") (pinfunction "2_P$2") (pintype "passive"))
      (node (ref "C30") (pin "P$2") (pinfunction "2_P$2") (pintype "passive"))
      (node (ref "C35") (pin "P$2") (pinfunction "2_P$2") (pintype "passive"))
      (node (ref "C36") (pin "P$1") (pinfunction "1_P$1") (pintype "passive"))
      (node (ref "C38") (pin "P$2") (pinfunction "2_P$2") (pintype "passive"))
      (node (ref "C39") (pin "P$1") (pinfunction "1_P$1") (pintype "passive"))
      (node (ref "C4") (pin "P$1") (pinfunction "1_P$1") (pintype "passive"))
      (node (ref "C40") (pin "P$1") (pinfunction "1_P$1") (pintype "passive"))
      (node (ref "C41") (pin "P$1") (pinfunction "1_P$1") (pintype "passive"))
      (node (ref "C43") (pin "P$2") (pinfunction "2_P$2") (pintype "passive"))
      (node (ref "C5") (pin "P$1") (pinfunction "1_P$1") (pintype "passive"))
      (node (ref "C7") (pin "P$1") (pinfunction "1_P$1") (pintype "passive"))
      (node (ref "FB1") (pin "1") (pinfunction "P$1_1") (pintype "bidirectional"))
      (node (ref "J1") (pin "4") (pinfunction "SUPPLY_VOLTAGE_4") (pintype "power_in"))
      (node (ref "J3") (pin "2") (pinfunction "2_2") (pintype "passive"))
      (node (ref "J3") (pin "4") (pinfunction "4_4") (pintype "passive"))
      (node (ref "L1") (pin "2") (pinfunction "P$2_2") (pintype "bidirectional"))
      (node (ref "R102") (pin "P$2") (pinfunction "2_P$2") (pintype "passive"))
      (node (ref "R103") (pin "P$2") (pinfunction "2_P$2") (pintype "passive"))
      (node (ref "R104") (pin "P$2") (pinfunction "2_P$2") (pintype "passive"))
      (node (ref "R105") (pin "P$2") (pinfunction "2_P$2") (pintype "passive"))
      (node (ref "R106") (pin "P$2") (pinfunction "2_P$2") (pintype "passive"))
      (node (ref "R107") (pin "P$2") (pinfunction "2_P$2") (pintype "passive"))
      (node (ref "R108") (pin "P$2") (pinfunction "2_P$2") (pintype "passive"))
      (node (ref "R13") (pin "P$2") (pinfunction "2_P$2") (pintype "passive"))
      (node (ref "R14") (pin "P$1") (pinfunction "1_P$1") (pintype "passive"))
      (node (ref "R15") (pin "P$1") (pinfunction "1_P$1") (pintype "passive"))
      (node (ref "R2") (pin "P$2") (pinfunction "2_P$2") (pintype "passive"))
      (node (ref "R25") (pin "P$2") (pinfunction "2_P$2") (pintype "passive"))
      (node (ref "R26") (pin "P$2") (pinfunction "2_P$2") (pintype "passive"))
      (node (ref "R27") (pin "P$2") (pinfunction "2_P$2") (pintype "passive"))
      (node (ref "R3") (pin "P$2") (pinfunction "2_P$2") (pintype "passive"))
      (node (ref "R4") (pin "P$2") (pinfunction "2_P$2") (pintype "passive"))
      (node (ref "R5") (pin "P$2") (pinfunction "2_P$2") (pintype "passive"))
      (node (ref "R6") (pin "P$2") (pinfunction "2_P$2") (pintype "passive"))
      (node (ref "R7") (pin "P$2") (pinfunction "2_P$2") (pintype "passive"))
      (node (ref "R8") (pin "P$2") (pinfunction "2_P$2") (pintype "passive"))
      (node (ref "U1") (pin "14") (pinfunction "VDDIO_14") (pintype "power_in"))
      (node (ref "U3") (pin "110") (pinfunction "VCC(IO)5_110") (pintype "bidirectional"))
      (node (ref "U3") (pin "123") (pinfunction "VCC(IO)6_123") (pintype "bidirectional"))
      (node (ref "U3") (pin "138") (pinfunction "VCC(IO)7_138") (pintype "bidirectional"))
      (node (ref "U3") (pin "149") (pinfunction "VCC(IO)8_149") (pintype "bidirectional"))
      (node (ref "U3") (pin "154") (pinfunction "VREFH_154") (pintype "bidirectional"))
      (node (ref "U3") (pin "155") (pinfunction "AVCC0_155") (pintype "bidirectional"))
      (node (ref "U3") (pin "158") (pinfunction "VREFH0_158") (pintype "bidirectional"))
      (node (ref "U3") (pin "171") (pinfunction "VCC(IO)9_171") (pintype "bidirectional"))
      (node (ref "U3") (pin "25") (pinfunction "VCC1_25") (pintype "bidirectional"))
      (node (ref "U3") (pin "26") (pinfunction "AVCC_SUBHS_26") (pintype "bidirectional"))
      (node (ref "U3") (pin "34") (pinfunction "VCC_USBHS_34") (pintype "bidirectional"))
      (node (ref "U3") (pin "48") (pinfunction "VCC_USB_48") (pintype "bidirectional"))
      (node (ref "U3") (pin "61") (pinfunction "VCC(IO)2_61") (pintype "bidirectional"))
      (node (ref "U3") (pin "84") (pinfunction "VCC(IO)3_84") (pintype "bidirectional"))
      (node (ref "U3") (pin "97") (pinfunction "VCC(IO)4_97") (pintype "bidirectional"))
    )
    (net (code "243") (name "VDD5") (class "Default")
      (node (ref "C23") (pin "P$1") (pinfunction "1_P$1") (pintype "passive"))
      (node (ref "C26") (pin "P$1") (pinfunction "1_P$1") (pintype "passive"))
      (node (ref "J2") (pin "P$3") (pinfunction "P$3_P$3") (pintype "bidirectional"))
      (node (ref "R19") (pin "P$2") (pinfunction "2_P$2") (pintype "passive"))
      (node (ref "R20") (pin "P$2") (pinfunction "2_P$2") (pintype "passive"))
      (node (ref "R31") (pin "P$2") (pinfunction "2_P$2") (pintype "passive"))
      (node (ref "R32") (pin "P$2") (pinfunction "2_P$2") (pintype "passive"))
      (node (ref "R51") (pin "P$2") (pinfunction "2_P$2") (pintype "passive"))
      (node (ref "R52") (pin "P$2") (pinfunction "2_P$2") (pintype "passive"))
      (node (ref "U$1") (pin "P$2") (pinfunction "VC+_P$2") (pintype "bidirectional"))
      (node (ref "U$2") (pin "P$2") (pinfunction "VC+_P$2") (pintype "bidirectional"))
      (node (ref "U$7") (pin "P$2") (pinfunction "VC+_P$2") (pintype "bidirectional"))
      (node (ref "U$8") (pin "P$2") (pinfunction "VC+_P$2") (pintype "bidirectional"))
      (node (ref "U18") (pin "3") (pinfunction "C(3)_3") (pintype "input"))
      (node (ref "U19") (pin "3") (pinfunction "C(3)_3") (pintype "input"))
      (node (ref "U2") (pin "4") (pinfunction "VIN_4") (pintype "input"))
      (node (ref "U20") (pin "3") (pinfunction "C(3)_3") (pintype "input"))
      (node (ref "U21") (pin "3") (pinfunction "C(3)_3") (pintype "input"))
      (node (ref "U28") (pin "3") (pinfunction "C(3)_3") (pintype "input"))
      (node (ref "U29") (pin "3") (pinfunction "C(3)_3") (pintype "input"))
      (node (ref "U30") (pin "3") (pinfunction "C(3)_3") (pintype "input"))
      (node (ref "U5") (pin "3") (pinfunction "C(3)_3") (pintype "input"))
      (node (ref "U8") (pin "3") (pinfunction "C(3)_3") (pintype "input"))
      (node (ref "U9") (pin "3") (pinfunction "C(3)_3") (pintype "input"))
    )
    (net (code "244") (name "VDD12") (class "Default")
      (node (ref "J10") (pin "P$1") (pinfunction "P$1_P$1") (pintype "bidirectional"))
      (node (ref "J10") (pin "P$2") (pinfunction "P$2_P$2") (pintype "bidirectional"))
      (node (ref "J11") (pin "P$2") (pinfunction "P$2_P$2") (pintype "bidirectional"))
      (node (ref "J12") (pin "P$2") (pinfunction "P$2_P$2") (pintype "bidirectional"))
      (node (ref "J13") (pin "1") (pinfunction "1-HLFB+_1") (pintype "passive"))
      (node (ref "J13") (pin "2") (pinfunction "2-INPUT_B+_2") (pintype "passive"))
      (node (ref "J13") (pin "3") (pinfunction "3-INPUT_A+_3") (pintype "passive"))
      (node (ref "J13") (pin "4") (pinfunction "4-ENABLE+_4") (pintype "passive"))
      (node (ref "J14") (pin "1") (pinfunction "1-HLFB+_1") (pintype "passive"))
      (node (ref "J14") (pin "2") (pinfunction "2-INPUT_B+_2") (pintype "passive"))
      (node (ref "J14") (pin "3") (pinfunction "3-INPUT_A+_3") (pintype "passive"))
      (node (ref "J14") (pin "4") (pinfunction "4-ENABLE+_4") (pintype "passive"))
      (node (ref "J17") (pin "1") (pinfunction "1-HLFB+_1") (pintype "passive"))
      (node (ref "J17") (pin "2") (pinfunction "2-INPUT_B+_2") (pintype "passive"))
      (node (ref "J17") (pin "3") (pinfunction "3-INPUT_A+_3") (pintype "passive"))
      (node (ref "J17") (pin "4") (pinfunction "4-ENABLE+_4") (pintype "passive"))
      (node (ref "J18") (pin "1") (pinfunction "1-HLFB+_1") (pintype "passive"))
      (node (ref "J18") (pin "2") (pinfunction "2-INPUT_B+_2") (pintype "passive"))
      (node (ref "J18") (pin "3") (pinfunction "3-INPUT_A+_3") (pintype "passive"))
      (node (ref "J18") (pin "4") (pinfunction "4-ENABLE+_4") (pintype "passive"))
      (node (ref "J19") (pin "P$2") (pinfunction "P$2_P$2") (pintype "bidirectional"))
      (node (ref "J20") (pin "P$2") (pinfunction "P$2_P$2") (pintype "bidirectional"))
      (node (ref "J21") (pin "1") (pinfunction "1-HLFB+_1") (pintype "passive"))
      (node (ref "J21") (pin "2") (pinfunction "2-INPUT_B+_2") (pintype "passive"))
      (node (ref "J21") (pin "3") (pinfunction "3-INPUT_A+_3") (pintype "passive"))
      (node (ref "J21") (pin "4") (pinfunction "4-ENABLE+_4") (pintype "passive"))
      (node (ref "J22") (pin "1") (pinfunction "1-HLFB+_1") (pintype "passive"))
      (node (ref "J22") (pin "2") (pinfunction "2-INPUT_B+_2") (pintype "passive"))
      (node (ref "J22") (pin "3") (pinfunction "3-INPUT_A+_3") (pintype "passive"))
      (node (ref "J22") (pin "4") (pinfunction "4-ENABLE+_4") (pintype "passive"))
      (node (ref "J25") (pin "1") (pinfunction "1-HLFB+_1") (pintype "passive"))
      (node (ref "J25") (pin "2") (pinfunction "2-INPUT_B+_2") (pintype "passive"))
      (node (ref "J25") (pin "3") (pinfunction "3-INPUT_A+_3") (pintype "passive"))
      (node (ref "J25") (pin "4") (pinfunction "4-ENABLE+_4") (pintype "passive"))
      (node (ref "J26") (pin "1") (pinfunction "1-HLFB+_1") (pintype "passive"))
      (node (ref "J26") (pin "2") (pinfunction "2-INPUT_B+_2") (pintype "passive"))
      (node (ref "J26") (pin "3") (pinfunction "3-INPUT_A+_3") (pintype "passive"))
      (node (ref "J26") (pin "4") (pinfunction "4-ENABLE+_4") (pintype "passive"))
      (node (ref "J27") (pin "P$2") (pinfunction "P$2_P$2") (pintype "bidirectional"))
      (node (ref "J28") (pin "P$2") (pinfunction "P$2_P$2") (pintype "bidirectional"))
      (node (ref "J29") (pin "1") (pinfunction "1-HLFB+_1") (pintype "passive"))
      (node (ref "J29") (pin "2") (pinfunction "2-INPUT_B+_2") (pintype "passive"))
      (node (ref "J29") (pin "3") (pinfunction "3-INPUT_A+_3") (pintype "passive"))
      (node (ref "J29") (pin "4") (pinfunction "4-ENABLE+_4") (pintype "passive"))
      (node (ref "J30") (pin "1") (pinfunction "1-HLFB+_1") (pintype "passive"))
      (node (ref "J30") (pin "2") (pinfunction "2-INPUT_B+_2") (pintype "passive"))
      (node (ref "J30") (pin "3") (pinfunction "3-INPUT_A+_3") (pintype "passive"))
      (node (ref "J30") (pin "4") (pinfunction "4-ENABLE+_4") (pintype "passive"))
      (node (ref "J31") (pin "P$2") (pinfunction "P$2_P$2") (pintype "bidirectional"))
      (node (ref "J33") (pin "1") (pinfunction "1-HLFB+_1") (pintype "passive"))
      (node (ref "J33") (pin "2") (pinfunction "2-INPUT_B+_2") (pintype "passive"))
      (node (ref "J33") (pin "3") (pinfunction "3-INPUT_A+_3") (pintype "passive"))
      (node (ref "J33") (pin "4") (pinfunction "4-ENABLE+_4") (pintype "passive"))
      (node (ref "J34") (pin "1") (pinfunction "1-HLFB+_1") (pintype "passive"))
      (node (ref "J34") (pin "2") (pinfunction "2-INPUT_B+_2") (pintype "passive"))
      (node (ref "J34") (pin "3") (pinfunction "3-INPUT_A+_3") (pintype "passive"))
      (node (ref "J34") (pin "4") (pinfunction "4-ENABLE+_4") (pintype "passive"))
      (node (ref "J9") (pin "P$2") (pinfunction "P$2_P$2") (pintype "bidirectional"))
      (node (ref "P2") (pin "P$1") (pinfunction "P$1_P$1") (pintype "bidirectional"))
      (node (ref "P4") (pin "P$1") (pinfunction "P$1_P$1") (pintype "bidirectional"))
      (node (ref "R109") (pin "2") (pinfunction "2_2") (pintype "passive"))
      (node (ref "R113") (pin "2") (pinfunction "2_2") (pintype "passive"))
      (node (ref "R114") (pin "2") (pinfunction "2_2") (pintype "passive"))
      (node (ref "R115") (pin "2") (pinfunction "2_2") (pintype "passive"))
      (node (ref "R119") (pin "2") (pinfunction "2_2") (pintype "passive"))
      (node (ref "R120") (pin "2") (pinfunction "2_2") (pintype "passive"))
      (node (ref "R133") (pin "2") (pinfunction "2_2") (pintype "passive"))
      (node (ref "R137") (pin "2") (pinfunction "2_2") (pintype "passive"))
      (node (ref "R138") (pin "2") (pinfunction "2_2") (pintype "passive"))
      (node (ref "R139") (pin "2") (pinfunction "2_2") (pintype "passive"))
      (node (ref "R143") (pin "2") (pinfunction "2_2") (pintype "passive"))
      (node (ref "R144") (pin "2") (pinfunction "2_2") (pintype "passive"))
      (node (ref "R157") (pin "2") (pinfunction "2_2") (pintype "passive"))
      (node (ref "R161") (pin "2") (pinfunction "2_2") (pintype "passive"))
      (node (ref "R162") (pin "2") (pinfunction "2_2") (pintype "passive"))
      (node (ref "R163") (pin "2") (pinfunction "2_2") (pintype "passive"))
      (node (ref "R167") (pin "2") (pinfunction "2_2") (pintype "passive"))
      (node (ref "R168") (pin "2") (pinfunction "2_2") (pintype "passive"))
      (node (ref "R37") (pin "2") (pinfunction "2_2") (pintype "passive"))
      (node (ref "R41") (pin "2") (pinfunction "2_2") (pintype "passive"))
      (node (ref "R42") (pin "2") (pinfunction "2_2") (pintype "passive"))
      (node (ref "R43") (pin "2") (pinfunction "2_2") (pintype "passive"))
      (node (ref "R47") (pin "2") (pinfunction "2_2") (pintype "passive"))
      (node (ref "R48") (pin "2") (pinfunction "2_2") (pintype "passive"))
      (node (ref "R61") (pin "2") (pinfunction "2_2") (pintype "passive"))
      (node (ref "R65") (pin "2") (pinfunction "2_2") (pintype "passive"))
      (node (ref "R66") (pin "2") (pinfunction "2_2") (pintype "passive"))
      (node (ref "R67") (pin "2") (pinfunction "2_2") (pintype "passive"))
      (node (ref "R71") (pin "2") (pinfunction "2_2") (pintype "passive"))
      (node (ref "R72") (pin "2") (pinfunction "2_2") (pintype "passive"))
      (node (ref "R85") (pin "2") (pinfunction "2_2") (pintype "passive"))
      (node (ref "R89") (pin "2") (pinfunction "2_2") (pintype "passive"))
      (node (ref "R90") (pin "2") (pinfunction "2_2") (pintype "passive"))
      (node (ref "R91") (pin "2") (pinfunction "2_2") (pintype "passive"))
      (node (ref "R95") (pin "2") (pinfunction "2_2") (pintype "passive"))
      (node (ref "R96") (pin "2") (pinfunction "2_2") (pintype "passive"))
    )
    (net (code "245") (name "VDDIN") (class "Default")
      (node (ref "J2") (pin "P$2") (pinfunction "P$2_P$2") (pintype "bidirectional"))
      (node (ref "L1") (pin "1") (pinfunction "P$1_1") (pintype "bidirectional"))
    )
    (net (code "246") (name "VDD_1.2") (class "Default")
      (node (ref "C10") (pin "P$1") (pinfunction "1_P$1") (pintype "passive"))
      (node (ref "C11") (pin "P$1") (pinfunction "1_P$1") (pintype "passive"))
      (node (ref "U1") (pin "1") (pinfunction "VDD_1.2_1") (pintype "power_in"))
    )
    (net (code "247") (name "WF_A_DIR") (class "Default")
      (node (ref "R159") (pin "1") (pinfunction "1_1") (pintype "passive"))
      (node (ref "U3") (pin "99") (pinfunction "P6_8_99") (pintype "bidirectional"))
    )
    (net (code "248") (name "WF_A_ENABLE") (class "Default")
      (node (ref "R160") (pin "1") (pinfunction "1_1") (pintype "passive"))
      (node (ref "U3") (pin "96") (pinfunction "P1_15_96") (pintype "bidirectional"))
    )
    (net (code "249") (name "WF_A_HLFB_OUT") (class "Default")
      (node (ref "J33") (pin "5") (pinfunction "5-HLFB-_5") (pintype "passive"))
    )
    (net (code "250") (name "WF_A_MI_DIR") (class "Default")
      (node (ref "J33") (pin "7") (pinfunction "7-INPUT_A-_7") (pintype "passive"))
      (node (ref "R161") (pin "1") (pinfunction "1_1") (pintype "passive"))
      (node (ref "U71") (pin "3") (pinfunction "C(3)_3") (pintype "input"))
    )
    (net (code "251") (name "WF_A_MI_ENABLE") (class "Default")
      (node (ref "J33") (pin "8") (pinfunction "8-ENABLE-_8") (pintype "passive"))
      (node (ref "R162") (pin "1") (pinfunction "1_1") (pintype "passive"))
      (node (ref "U72") (pin "3") (pinfunction "C(3)_3") (pintype "input"))
    )
    (net (code "252") (name "WF_A_MI_STEP") (class "Default")
      (node (ref "J33") (pin "6") (pinfunction "6-INPUT_B-_6") (pintype "passive"))
      (node (ref "R157") (pin "1") (pinfunction "1_1") (pintype "passive"))
      (node (ref "U70") (pin "3") (pinfunction "C(3)_3") (pintype "input"))
    )
    (net (code "253") (name "WF_A_STEP") (class "Default")
      (node (ref "R158") (pin "1") (pinfunction "1_1") (pintype "passive"))
      (node (ref "U3") (pin "100") (pinfunction "P6_9_100") (pintype "bidirectional"))
    )
    (net (code "254") (name "WF_B_DIR") (class "Default")
      (node (ref "R165") (pin "1") (pinfunction "1_1") (pintype "passive"))
      (node (ref "U3") (pin "94") (pinfunction "P1_13_94") (pintype "bidirectional"))
    )
    (net (code "255") (name "WF_B_ENABLE") (class "Default")
      (node (ref "R166") (pin "1") (pinfunction "1_1") (pintype "passive"))
      (node (ref "U3") (pin "93") (pinfunction "P1_12_93") (pintype "bidirectional"))
    )
    (net (code "256") (name "WF_B_HLFB_OUT") (class "Default")
      (node (ref "J34") (pin "5") (pinfunction "5-HLFB-_5") (pintype "passive"))
    )
    (net (code "257") (name "WF_B_MI_ENABLE") (class "Default")
      (node (ref "J34") (pin "8") (pinfunction "8-ENABLE-_8") (pintype "passive"))
      (node (ref "R168") (pin "1") (pinfunction "1_1") (pintype "passive"))
      (node (ref "U75") (pin "3") (pinfunction "C(3)_3") (pintype "input"))
    )
    (net (code "258") (name "WF_B_MI_STEP") (class "Default")
      (node (ref "J34") (pin "6") (pinfunction "6-INPUT_B-_6") (pintype "passive"))
      (node (ref "R163") (pin "1") (pinfunction "1_1") (pintype "passive"))
      (node (ref "U73") (pin "3") (pinfunction "C(3)_3") (pintype "input"))
    )
    (net (code "259") (name "WF_B_STEP") (class "Default")
      (node (ref "R164") (pin "1") (pinfunction "1_1") (pintype "passive"))
      (node (ref "U3") (pin "95") (pinfunction "P1_14_95") (pintype "bidirectional"))
    )
    (net (code "260") (name "XCIN") (class "Default")
      (node (ref "C32") (pin "P$1") (pinfunction "1_P$1") (pintype "passive"))
      (node (ref "U3") (pin "20") (pinfunction "XCIN_20") (pintype "bidirectional"))
      (node (ref "X3") (pin "P$1") (pinfunction "P$1_P$1") (pintype "bidirectional"))
    )
    (net (code "261") (name "XCOUT") (class "Default")
      (node (ref "C37") (pin "P$1") (pinfunction "1_P$1") (pintype "passive"))
      (node (ref "U3") (pin "21") (pinfunction "XCOUT_21") (pintype "bidirectional"))
      (node (ref "X3") (pin "P$2") (pinfunction "P$2_P$2") (pintype "bidirectional"))
    )
    (net (code "262") (name "XII") (class "Default")
      (node (ref "C1") (pin "P$1") (pinfunction "1_P$1") (pintype "passive"))
      (node (ref "U1") (pin "8") (pinfunction "XI_8") (pintype "input"))
      (node (ref "X1") (pin "1") (pinfunction "1_1") (pintype "bidirectional"))
    )
    (net (code "263") (name "XOO") (class "Default")
      (node (ref "C2") (pin "P$1") (pinfunction "1_P$1") (pintype "passive"))
      (node (ref "U1") (pin "7") (pinfunction "XO_7") (pintype "output"))
      (node (ref "X1") (pin "3") (pinfunction "3_3") (pintype "bidirectional"))
    )
    (net (code "264") (name "XTAL1") (class "Default")
      (node (ref "C17") (pin "P$1") (pinfunction "1_P$1") (pintype "passive"))
      (node (ref "U3") (pin "23") (pinfunction "P2_13/XTAL_23") (pintype "bidirectional"))
      (node (ref "X2") (pin "1") (pinfunction "1_1") (pintype "bidirectional"))
    )
    (net (code "265") (name "XTAL2") (class "Default")
      (node (ref "C18") (pin "P$1") (pinfunction "1_P$1") (pintype "passive"))
      (node (ref "U3") (pin "24") (pinfunction "P2_12/EXTAL_24") (pintype "bidirectional"))
      (node (ref "X2") (pin "3") (pinfunction "3_3") (pintype "bidirectional"))
    )
    (net (code "266") (name "X_A_DIR") (class "Default")
      (node (ref "R39") (pin "1") (pinfunction "1_1") (pintype "passive"))
      (node (ref "U3") (pin "117") (pinfunction "P6_5_117") (pintype "bidirectional"))
    )
    (net (code "267") (name "X_A_ENABLE") (class "Default")
      (node (ref "R40") (pin "1") (pinfunction "1_1") (pintype "passive"))
      (node (ref "U3") (pin "116") (pinfunction "P6_6_116") (pintype "bidirectional"))
    )
    (net (code "268") (name "X_A_HLFB_OUT") (class "Default")
      (node (ref "J13") (pin "5") (pinfunction "5-HLFB-_5") (pintype "passive"))
    )
    (net (code "269") (name "X_A_MI_DIR") (class "Default")
      (node (ref "J13") (pin "7") (pinfunction "7-INPUT_A-_7") (pintype "passive"))
      (node (ref "R41") (pin "1") (pinfunction "1_1") (pintype "passive"))
      (node (ref "U11") (pin "3") (pinfunction "C(3)_3") (pintype "input"))
    )
    (net (code "270") (name "X_A_MI_ENABLE") (class "Default")
      (node (ref "J13") (pin "8") (pinfunction "8-ENABLE-_8") (pintype "passive"))
      (node (ref "R42") (pin "1") (pinfunction "1_1") (pintype "passive"))
      (node (ref "U12") (pin "3") (pinfunction "C(3)_3") (pintype "input"))
    )
    (net (code "271") (name "X_A_MI_STEP") (class "Default")
      (node (ref "J13") (pin "6") (pinfunction "6-INPUT_B-_6") (pintype "passive"))
      (node (ref "R37") (pin "1") (pinfunction "1_1") (pintype "passive"))
      (node (ref "U10") (pin "3") (pinfunction "C(3)_3") (pintype "input"))
    )
    (net (code "272") (name "X_A_STEP") (class "Default")
      (node (ref "R38") (pin "1") (pinfunction "1_1") (pintype "passive"))
      (node (ref "U3") (pin "118") (pinfunction "P6_4_118") (pintype "bidirectional"))
    )
    (net (code "273") (name "X_B_DIR") (class "Default")
      (node (ref "R45") (pin "1") (pinfunction "1_1") (pintype "passive"))
      (node (ref "U3") (pin "120") (pinfunction "P6_2_120") (pintype "bidirectional"))
    )
    (net (code "274") (name "X_B_ENABLE") (class "Default")
      (node (ref "R46") (pin "1") (pinfunction "1_1") (pintype "passive"))
      (node (ref "U3") (pin "119") (pinfunction "P6_3_119") (pintype "bidirectional"))
    )
    (net (code "275") (name "X_B_HLFB_OUT") (class "Default")
      (node (ref "J14") (pin "5") (pinfunction "5-HLFB-_5") (pintype "passive"))
    )
    (net (code "276") (name "X_B_MI_DIR") (class "Default")
      (node (ref "J14") (pin "7") (pinfunction "7-INPUT_A-_7") (pintype "passive"))
      (node (ref "R47") (pin "1") (pinfunction "1_1") (pintype "passive"))
      (node (ref "U14") (pin "3") (pinfunction "C(3)_3") (pintype "input"))
    )
    (net (code "277") (name "X_B_MI_ENABLE") (class "Default")
      (node (ref "J14") (pin "8") (pinfunction "8-ENABLE-_8") (pintype "passive"))
      (node (ref "R48") (pin "1") (pinfunction "1_1") (pintype "passive"))
      (node (ref "U15") (pin "3") (pinfunction "C(3)_3") (pintype "input"))
    )
    (net (code "278") (name "X_B_MI_STEP") (class "Default")
      (node (ref "J14") (pin "6") (pinfunction "6-INPUT_B-_6") (pintype "passive"))
      (node (ref "R43") (pin "1") (pinfunction "1_1") (pintype "passive"))
      (node (ref "U13") (pin "3") (pinfunction "C(3)_3") (pintype "input"))
    )
    (net (code "279") (name "X_B_STEP") (class "Default")
      (node (ref "R44") (pin "1") (pinfunction "1_1") (pintype "passive"))
      (node (ref "U3") (pin "121") (pinfunction "P6_1_121") (pintype "bidirectional"))
    )
    (net (code "280") (name "Y_A_DIR") (class "Default")
      (node (ref "R63") (pin "1") (pinfunction "1_1") (pintype "passive"))
      (node (ref "U3") (pin "114") (pinfunction "PA_0_114") (pintype "bidirectional"))
    )
    (net (code "281") (name "Y_A_ENABLE") (class "Default")
      (node (ref "R64") (pin "1") (pinfunction "1_1") (pintype "passive"))
      (node (ref "U3") (pin "113") (pinfunction "PA_1_113") (pintype "bidirectional"))
    )
    (net (code "282") (name "Y_A_HLFB_OUT") (class "Default")
      (node (ref "J17") (pin "5") (pinfunction "5-HLFB-_5") (pintype "passive"))
    )
    (net (code "283") (name "Y_A_MI_DIR") (class "Default")
      (node (ref "J17") (pin "7") (pinfunction "7-INPUT_A-_7") (pintype "passive"))
      (node (ref "R65") (pin "1") (pinfunction "1_1") (pintype "passive"))
      (node (ref "U23") (pin "3") (pinfunction "C(3)_3") (pintype "input"))
    )
    (net (code "284") (name "Y_A_MI_ENABLE") (class "Default")
      (node (ref "J17") (pin "8") (pinfunction "8-ENABLE-_8") (pintype "passive"))
      (node (ref "R66") (pin "1") (pinfunction "1_1") (pintype "passive"))
      (node (ref "U24") (pin "3") (pinfunction "C(3)_3") (pintype "input"))
    )
    (net (code "285") (name "Y_A_MI_STEP") (class "Default")
      (node (ref "J17") (pin "6") (pinfunction "6-INPUT_B-_6") (pintype "passive"))
      (node (ref "R61") (pin "1") (pinfunction "1_1") (pintype "passive"))
      (node (ref "U22") (pin "3") (pinfunction "C(3)_3") (pintype "input"))
    )
    (net (code "286") (name "Y_A_STEP") (class "Default")
      (node (ref "R62") (pin "1") (pinfunction "1_1") (pintype "passive"))
      (node (ref "U3") (pin "115") (pinfunction "P6_7_115") (pintype "bidirectional"))
    )
    (net (code "287") (name "Y_B_DIR") (class "Default")
      (node (ref "R69") (pin "1") (pinfunction "1_1") (pintype "passive"))
      (node (ref "U3") (pin "108") (pinfunction "PA_9_108") (pintype "bidirectional"))
    )
    (net (code "288") (name "Y_B_ENABLE") (class "Default")
      (node (ref "R70") (pin "1") (pinfunction "1_1") (pintype "passive"))
      (node (ref "U3") (pin "107") (pinfunction "PA_8_107") (pintype "bidirectional"))
    )
    (net (code "289") (name "Y_B_HLFB_OUT") (class "Default")
      (node (ref "J18") (pin "5") (pinfunction "5-HLFB-_5") (pintype "passive"))
    )
    (net (code "290") (name "Y_B_MI_DIR") (class "Default")
      (node (ref "J18") (pin "7") (pinfunction "7-INPUT_A-_7") (pintype "passive"))
      (node (ref "R71") (pin "1") (pinfunction "1_1") (pintype "passive"))
      (node (ref "U26") (pin "3") (pinfunction "C(3)_3") (pintype "input"))
    )
    (net (code "291") (name "Y_B_MI_ENABLE") (class "Default")
      (node (ref "J18") (pin "8") (pinfunction "8-ENABLE-_8") (pintype "passive"))
      (node (ref "R72") (pin "1") (pinfunction "1_1") (pintype "passive"))
      (node (ref "U27") (pin "3") (pinfunction "C(3)_3") (pintype "input"))
    )
    (net (code "292") (name "Y_B_MI_STEP") (class "Default")
      (node (ref "J18") (pin "6") (pinfunction "6-INPUT_B-_6") (pintype "passive"))
      (node (ref "R67") (pin "1") (pinfunction "1_1") (pintype "passive"))
      (node (ref "U25") (pin "3") (pinfunction "C(3)_3") (pintype "input"))
    )
    (net (code "293") (name "Y_B_STEP") (class "Default")
      (node (ref "R68") (pin "1") (pinfunction "1_1") (pintype "passive"))
      (node (ref "U3") (pin "109") (pinfunction "PA_10_109") (pintype "bidirectional"))
    )
    (net (code "294") (name "Z_A_DIR") (class "Default")
      (node (ref "R87") (pin "1") (pinfunction "1_1") (pintype "passive"))
      (node (ref "U3") (pin "105") (pinfunction "P6_14_105") (pintype "bidirectional"))
    )
    (net (code "295") (name "Z_A_ENABLE") (class "Default")
      (node (ref "R88") (pin "1") (pinfunction "1_1") (pintype "passive"))
      (node (ref "U3") (pin "104") (pinfunction "P6_13_104") (pintype "bidirectional"))
    )
    (net (code "296") (name "Z_A_HLFB_OUT") (class "Default")
      (node (ref "J21") (pin "5") (pinfunction "5-HLFB-_5") (pintype "passive"))
    )
    (net (code "297") (name "Z_A_MI_DIR") (class "Default")
      (node (ref "J21") (pin "7") (pinfunction "7-INPUT_A-_7") (pintype "passive"))
      (node (ref "R89") (pin "1") (pinfunction "1_1") (pintype "passive"))
      (node (ref "U35") (pin "3") (pinfunction "C(3)_3") (pintype "input"))
    )
    (net (code "298") (name "Z_A_MI_ENABLE") (class "Default")
      (node (ref "J21") (pin "8") (pinfunction "8-ENABLE-_8") (pintype "passive"))
      (node (ref "R90") (pin "1") (pinfunction "1_1") (pintype "passive"))
      (node (ref "U36") (pin "3") (pinfunction "C(3)_3") (pintype "input"))
    )
    (net (code "299") (name "Z_A_MI_STEP") (class "Default")
      (node (ref "J21") (pin "6") (pinfunction "6-INPUT_B-_6") (pintype "passive"))
      (node (ref "R85") (pin "1") (pinfunction "1_1") (pintype "passive"))
      (node (ref "U34") (pin "3") (pinfunction "C(3)_3") (pintype "input"))
    )
    (net (code "300") (name "Z_A_STEP") (class "Default")
      (node (ref "R86") (pin "1") (pinfunction "1_1") (pintype "passive"))
      (node (ref "U3") (pin "106") (pinfunction "P6_15_106") (pintype "bidirectional"))
    )
    (net (code "301") (name "Z_B_DIR") (class "Default")
      (node (ref "R93") (pin "1") (pinfunction "1_1") (pintype "passive"))
      (node (ref "U3") (pin "102") (pinfunction "P6_11_102") (pintype "bidirectional"))
    )
    (net (code "302") (name "Z_B_ENABLE") (class "Default")
      (node (ref "R94") (pin "1") (pinfunction "1_1") (pintype "passive"))
      (node (ref "U3") (pin "101") (pinfunction "P6_10_101") (pintype "bidirectional"))
    )
    (net (code "303") (name "Z_B_HLFB_OUT") (class "Default")
      (node (ref "J22") (pin "5") (pinfunction "5-HLFB-_5") (pintype "passive"))
    )
    (net (code "304") (name "Z_B_MI_DIR") (class "Default")
      (node (ref "J22") (pin "7") (pinfunction "7-INPUT_A-_7") (pintype "passive"))
      (node (ref "R95") (pin "1") (pinfunction "1_1") (pintype "passive"))
      (node (ref "U38") (pin "3") (pinfunction "C(3)_3") (pintype "input"))
    )
    (net (code "305") (name "Z_B_MI_ENABLE") (class "Default")
      (node (ref "J22") (pin "8") (pinfunction "8-ENABLE-_8") (pintype "passive"))
      (node (ref "R96") (pin "1") (pinfunction "1_1") (pintype "passive"))
      (node (ref "U39") (pin "3") (pinfunction "C(3)_3") (pintype "input"))
    )
    (net (code "306") (name "Z_B_MI_STEP") (class "Default")
      (node (ref "J22") (pin "6") (pinfunction "6-INPUT_B-_6") (pintype "passive"))
      (node (ref "R91") (pin "1") (pinfunction "1_1") (pintype "passive"))
      (node (ref "U37") (pin "3") (pinfunction "C(3)_3") (pintype "input"))
    )
    (net (code "307") (name "Z_B_STEP") (class "Default")
      (node (ref "R92") (pin "1") (pinfunction "1_1") (pintype "passive"))
      (node (ref "U3") (pin "103") (pinfunction "P6_12_103") (pintype "bidirectional"))
    )
    (net (code "308") (name "unconnected-(U3-VBAT-Pad18)") (class "Default")
      (node (ref "U3") (pin "18") (pinfunction "VBAT_18") (pintype "bidirectional"))
    )
  )
)
